# Cubesat-rev1.net
KiCad netlist of a schematic drawn in EAGLE
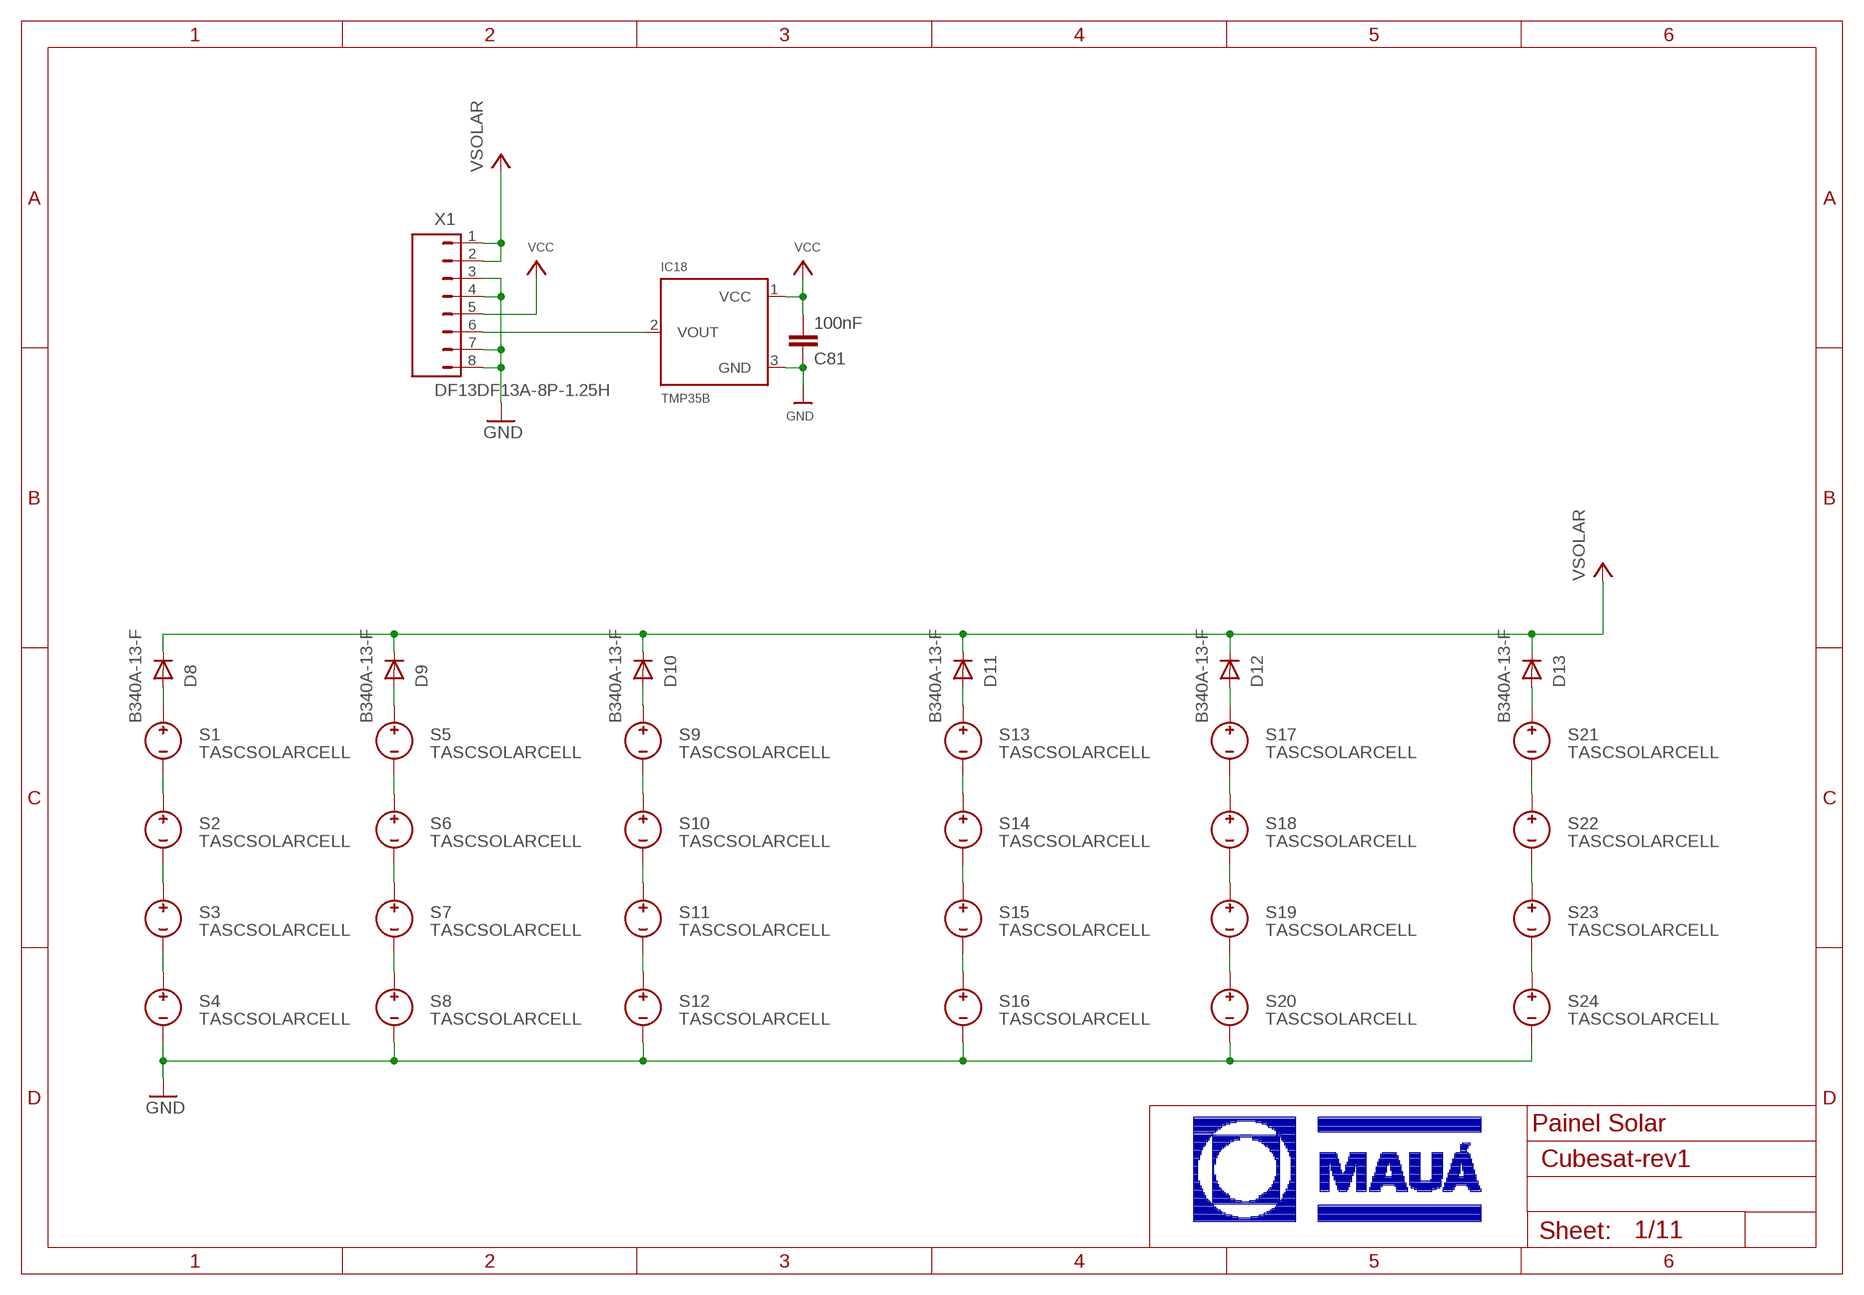
[diagram p0: schematic, sheet 1]
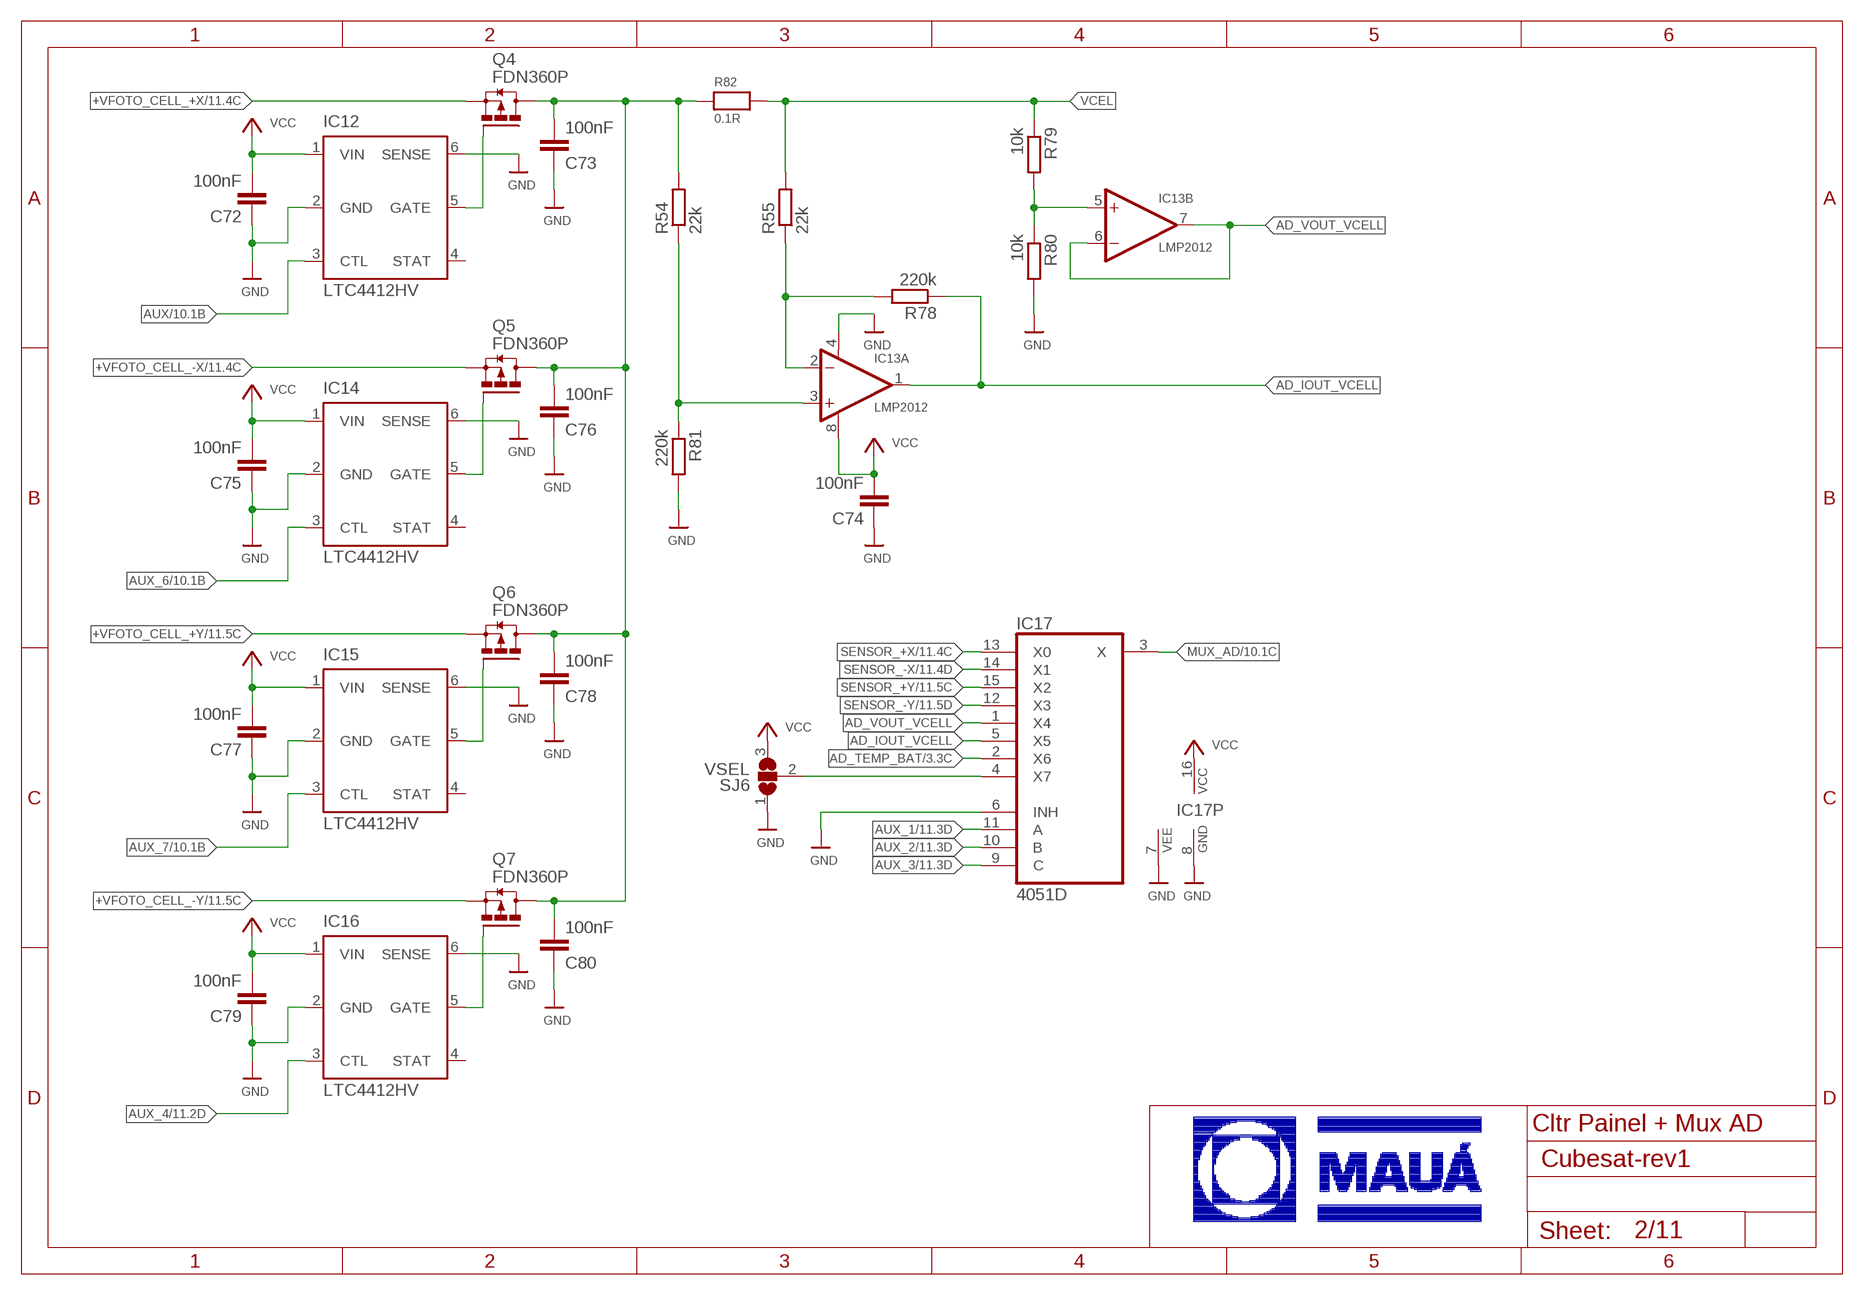
[diagram p1: schematic, sheet 2]
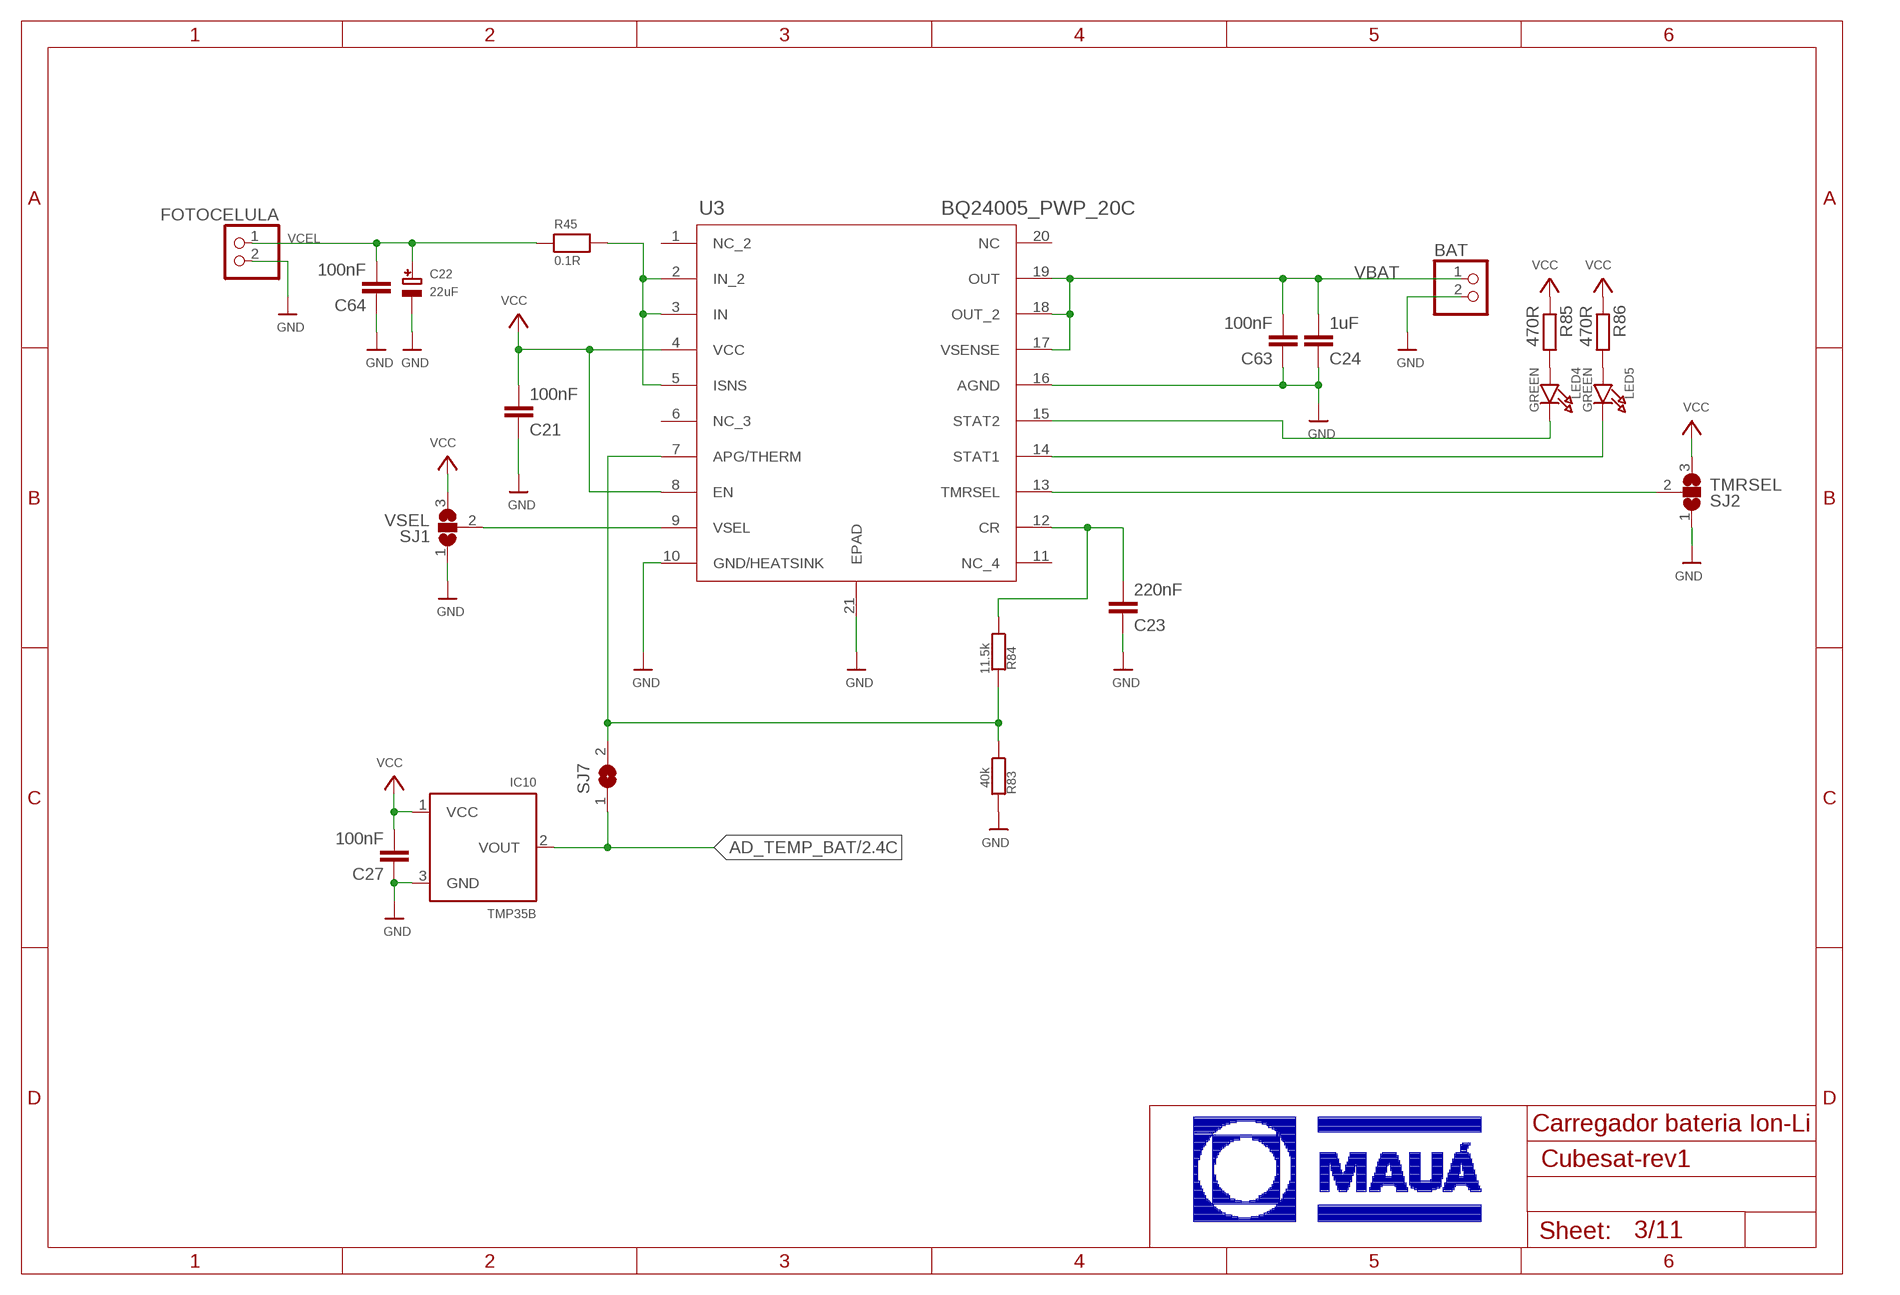
[diagram p2: schematic, sheet 3]
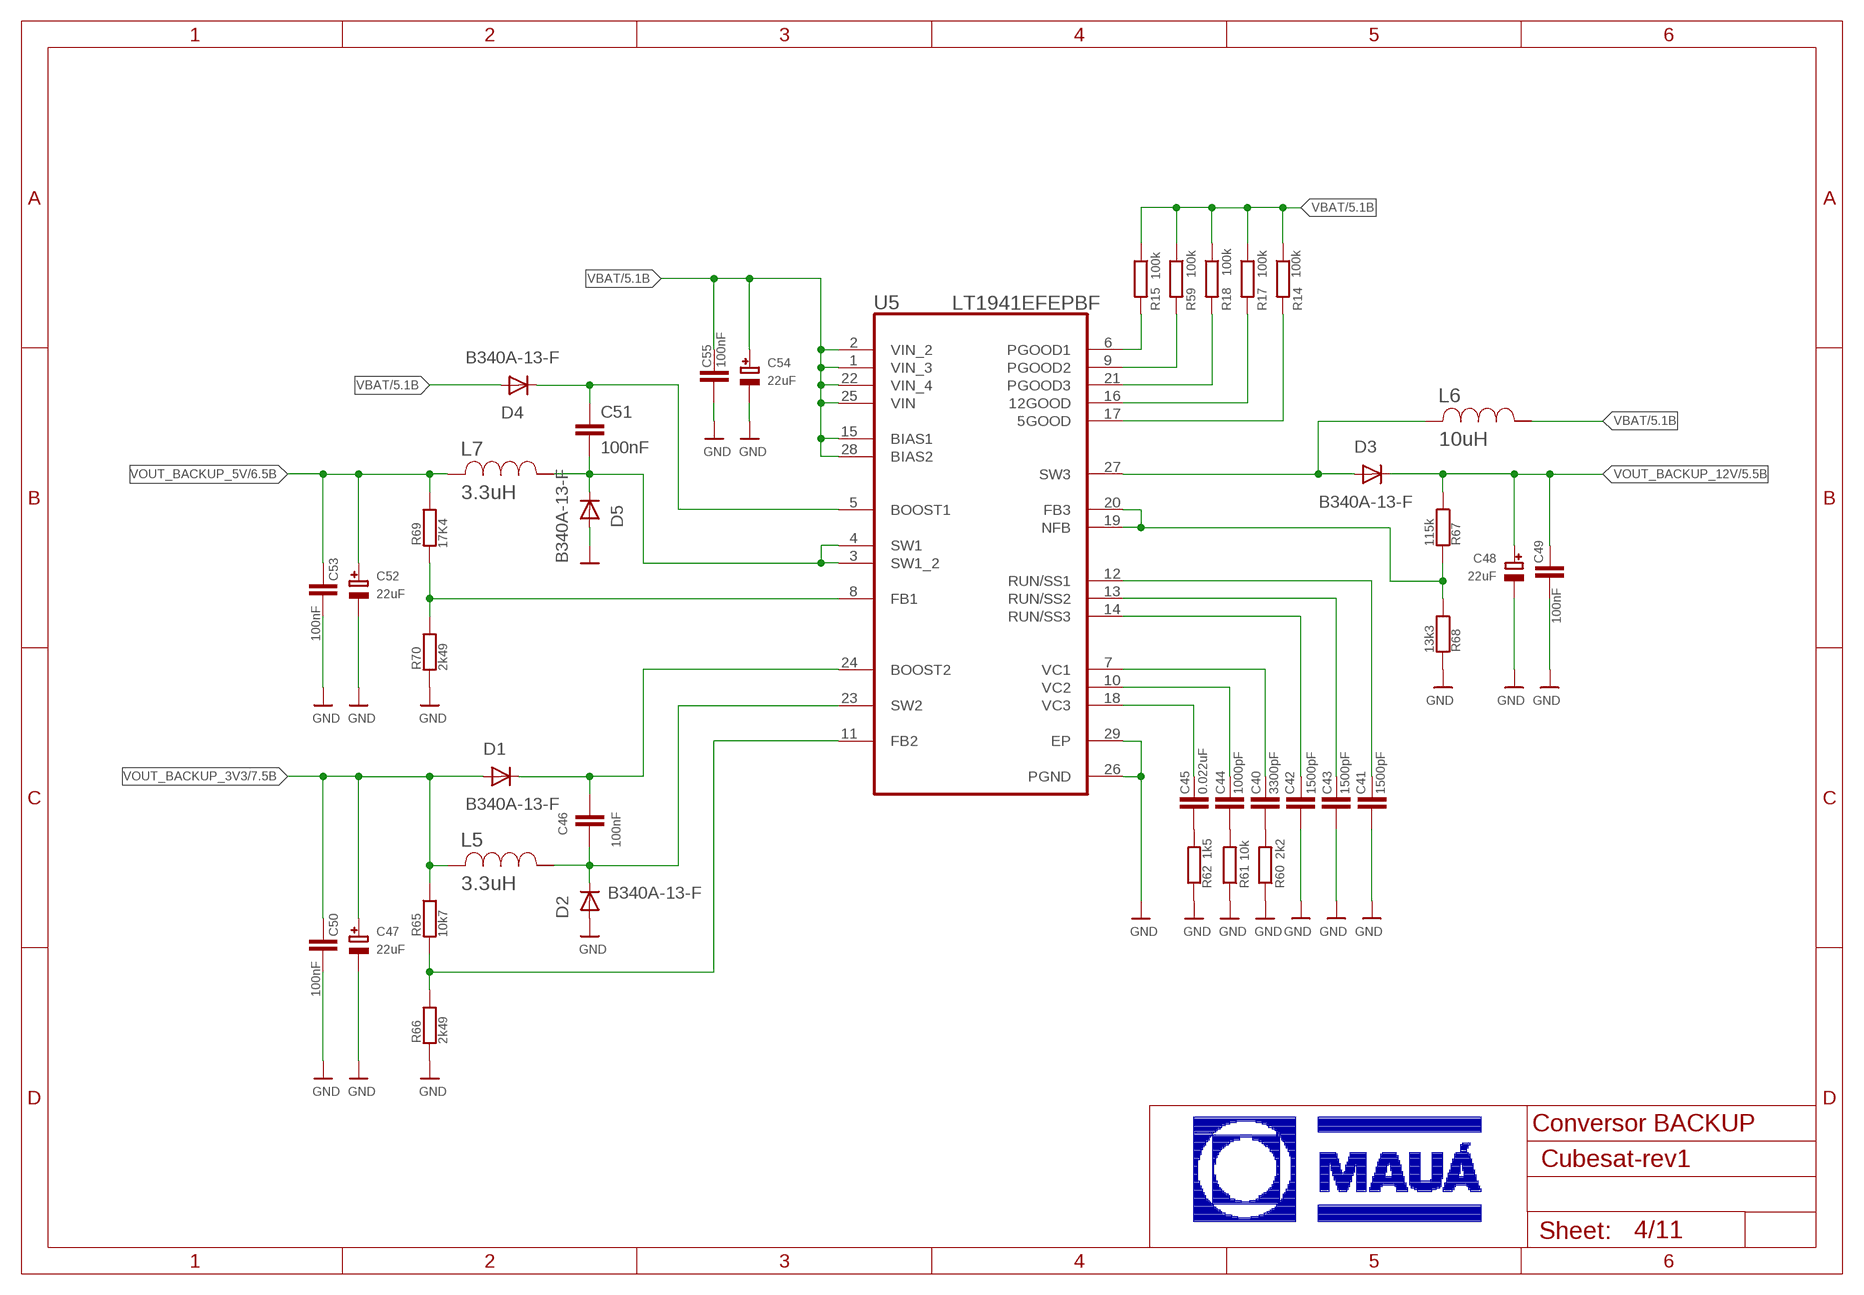
[diagram p3: schematic, sheet 4]
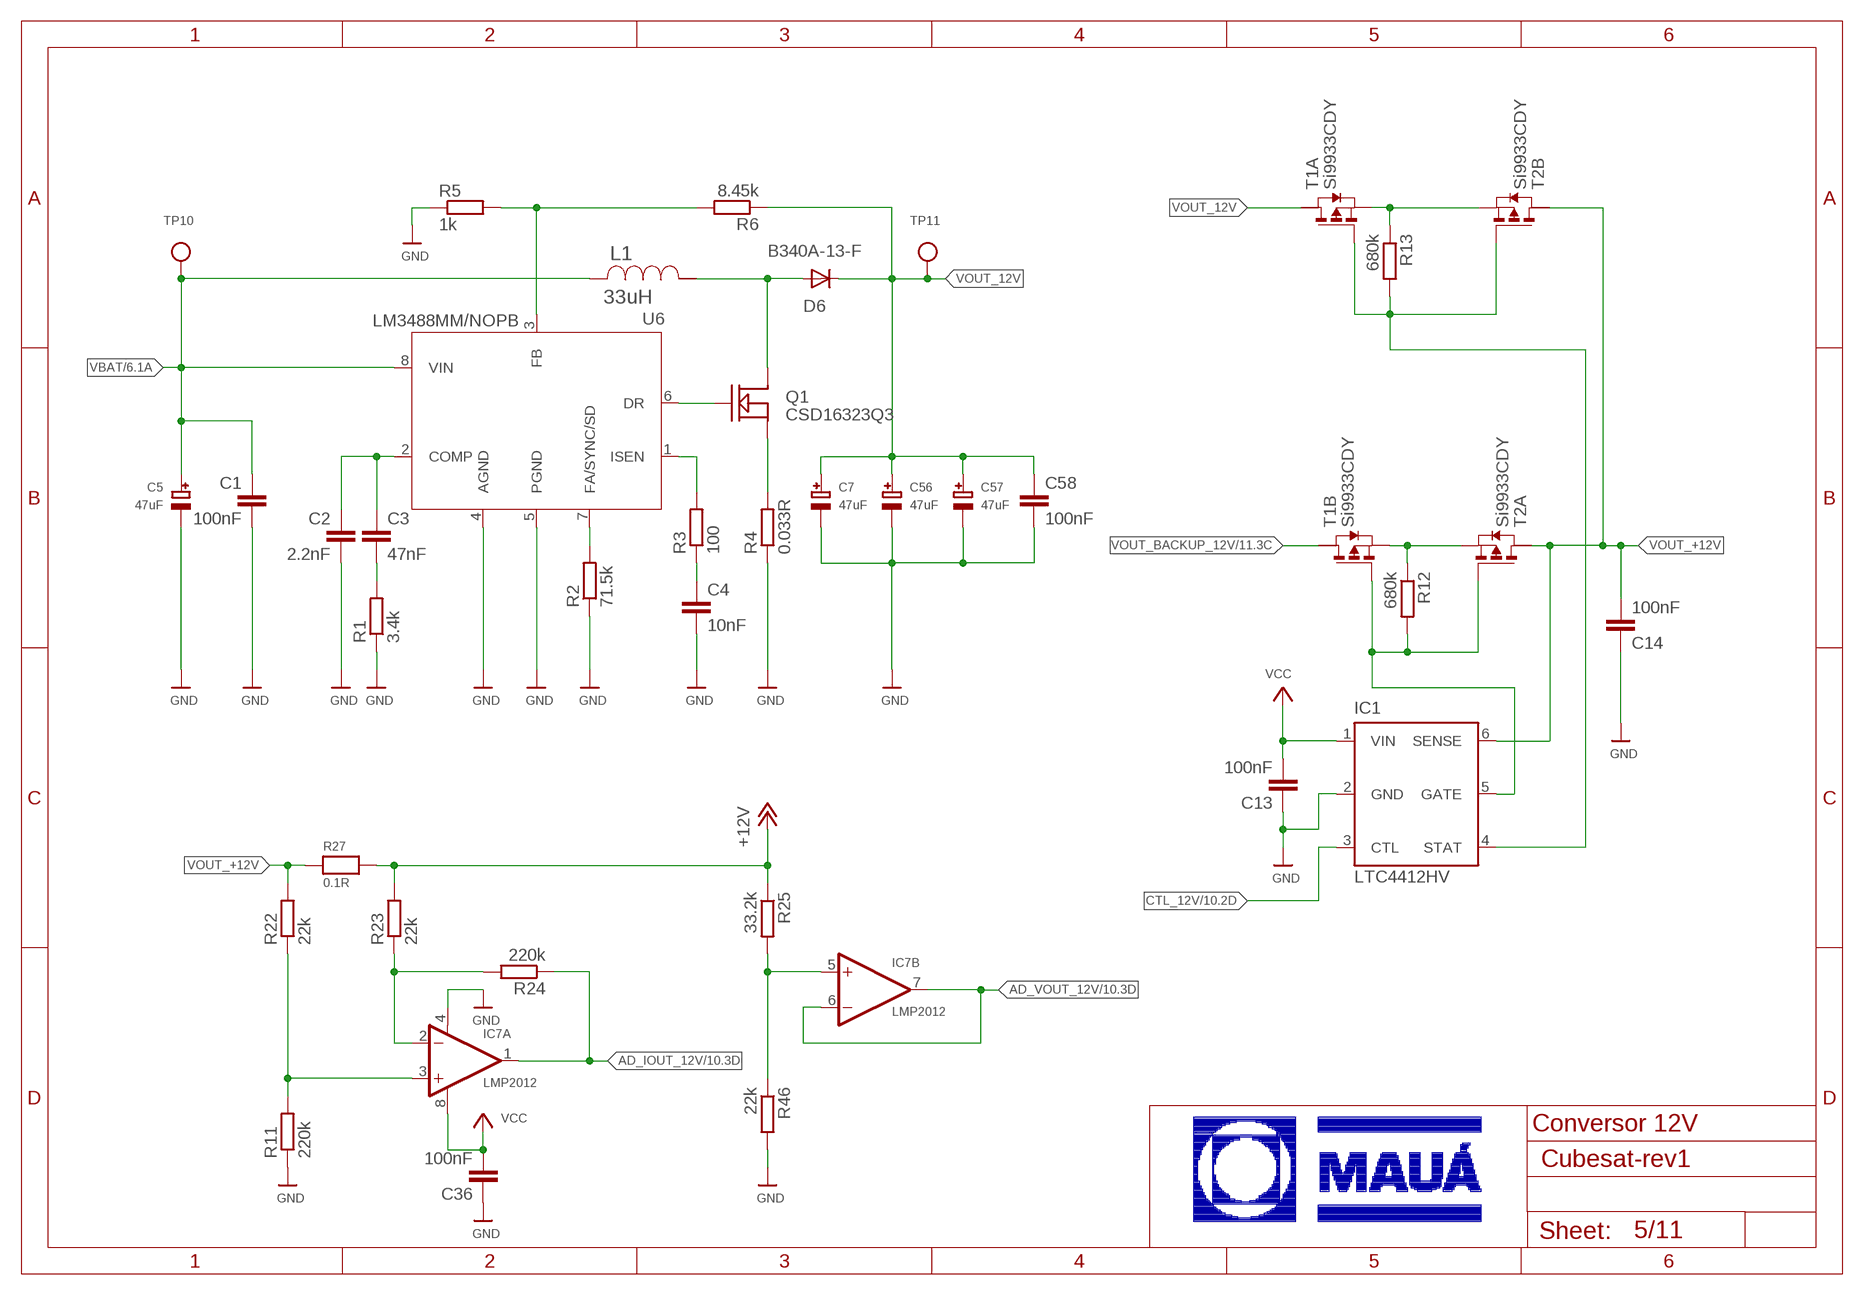
[diagram p4: schematic, sheet 5]
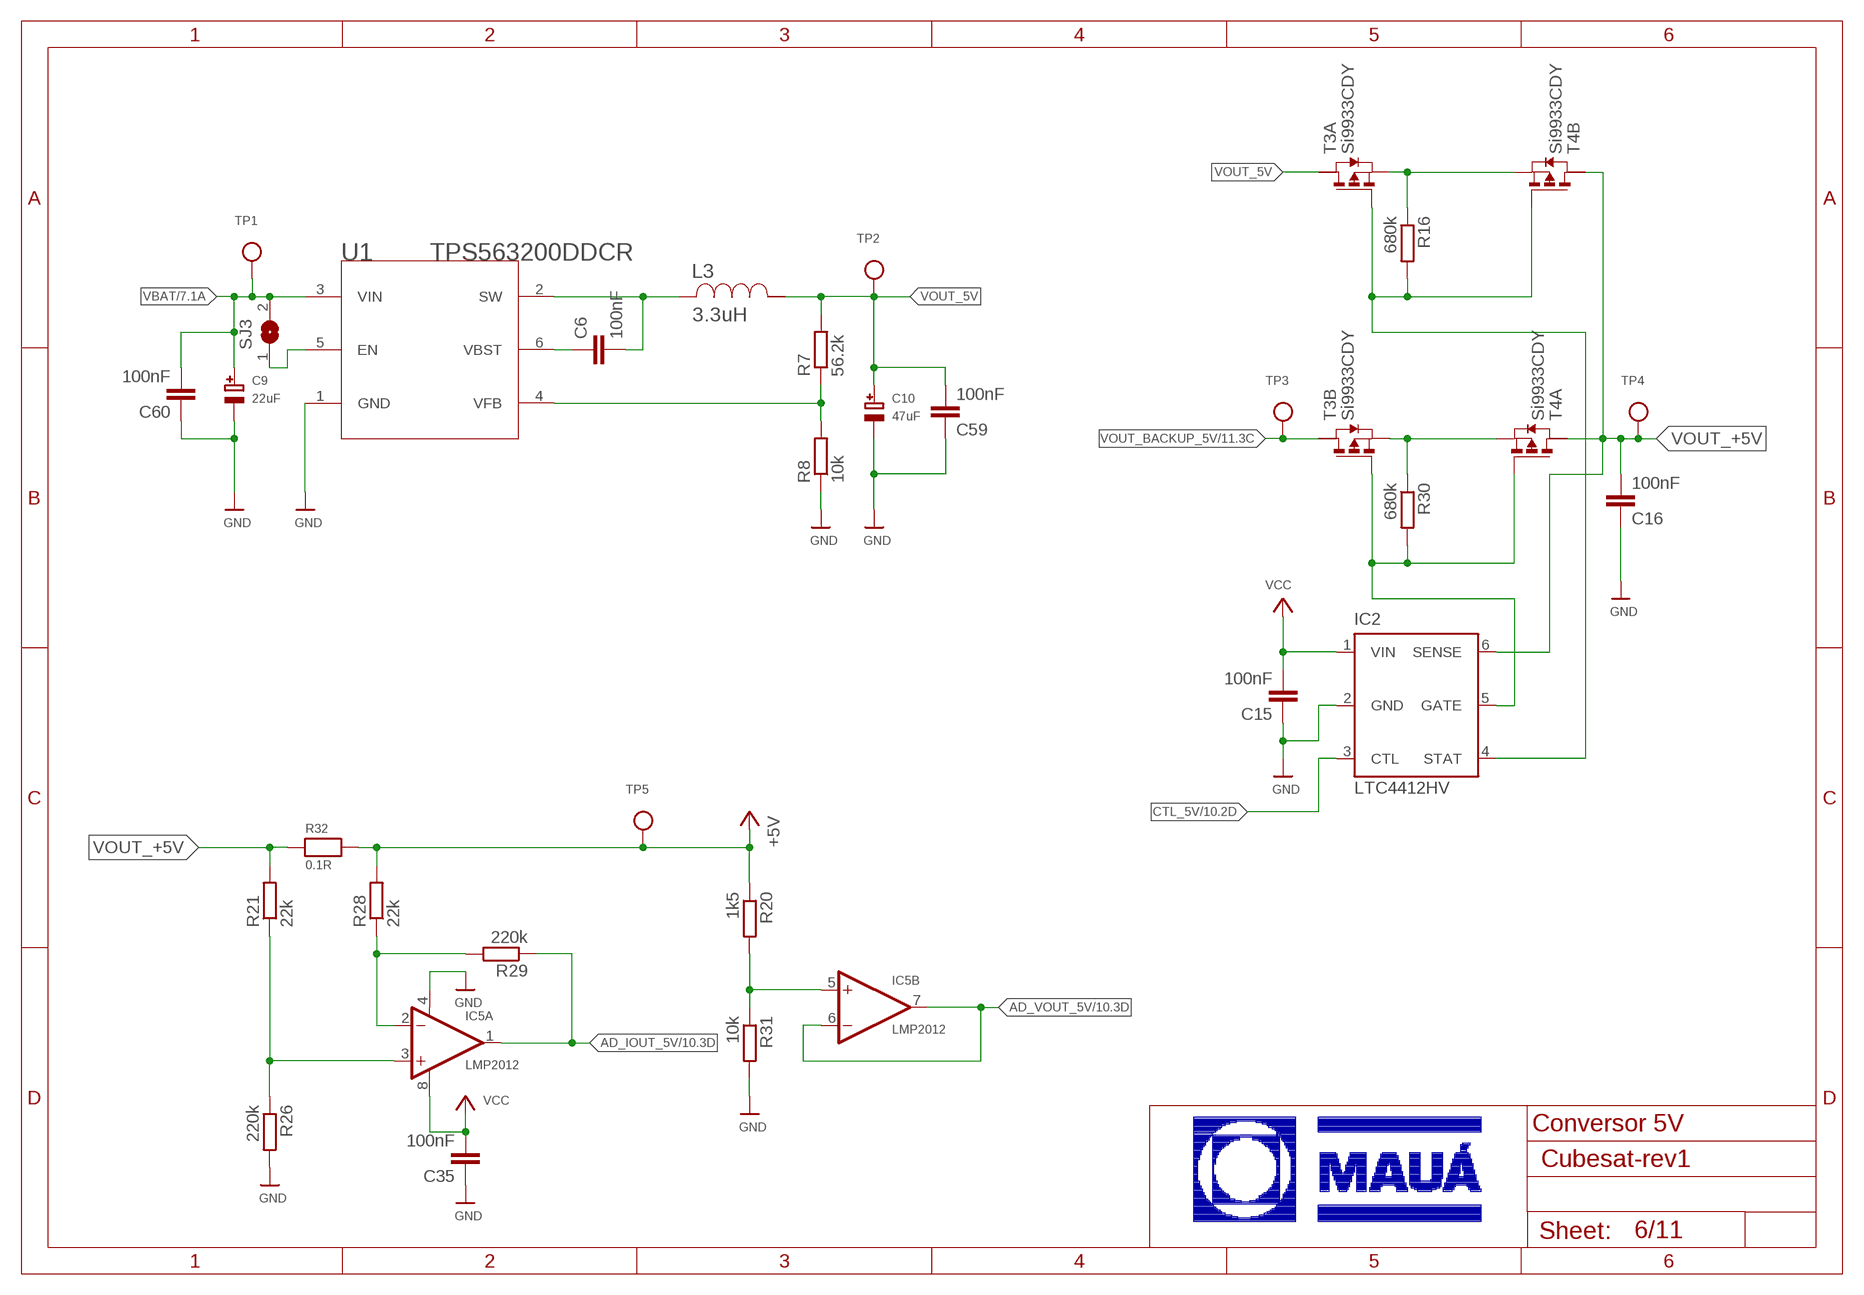
[diagram p5: schematic, sheet 6]
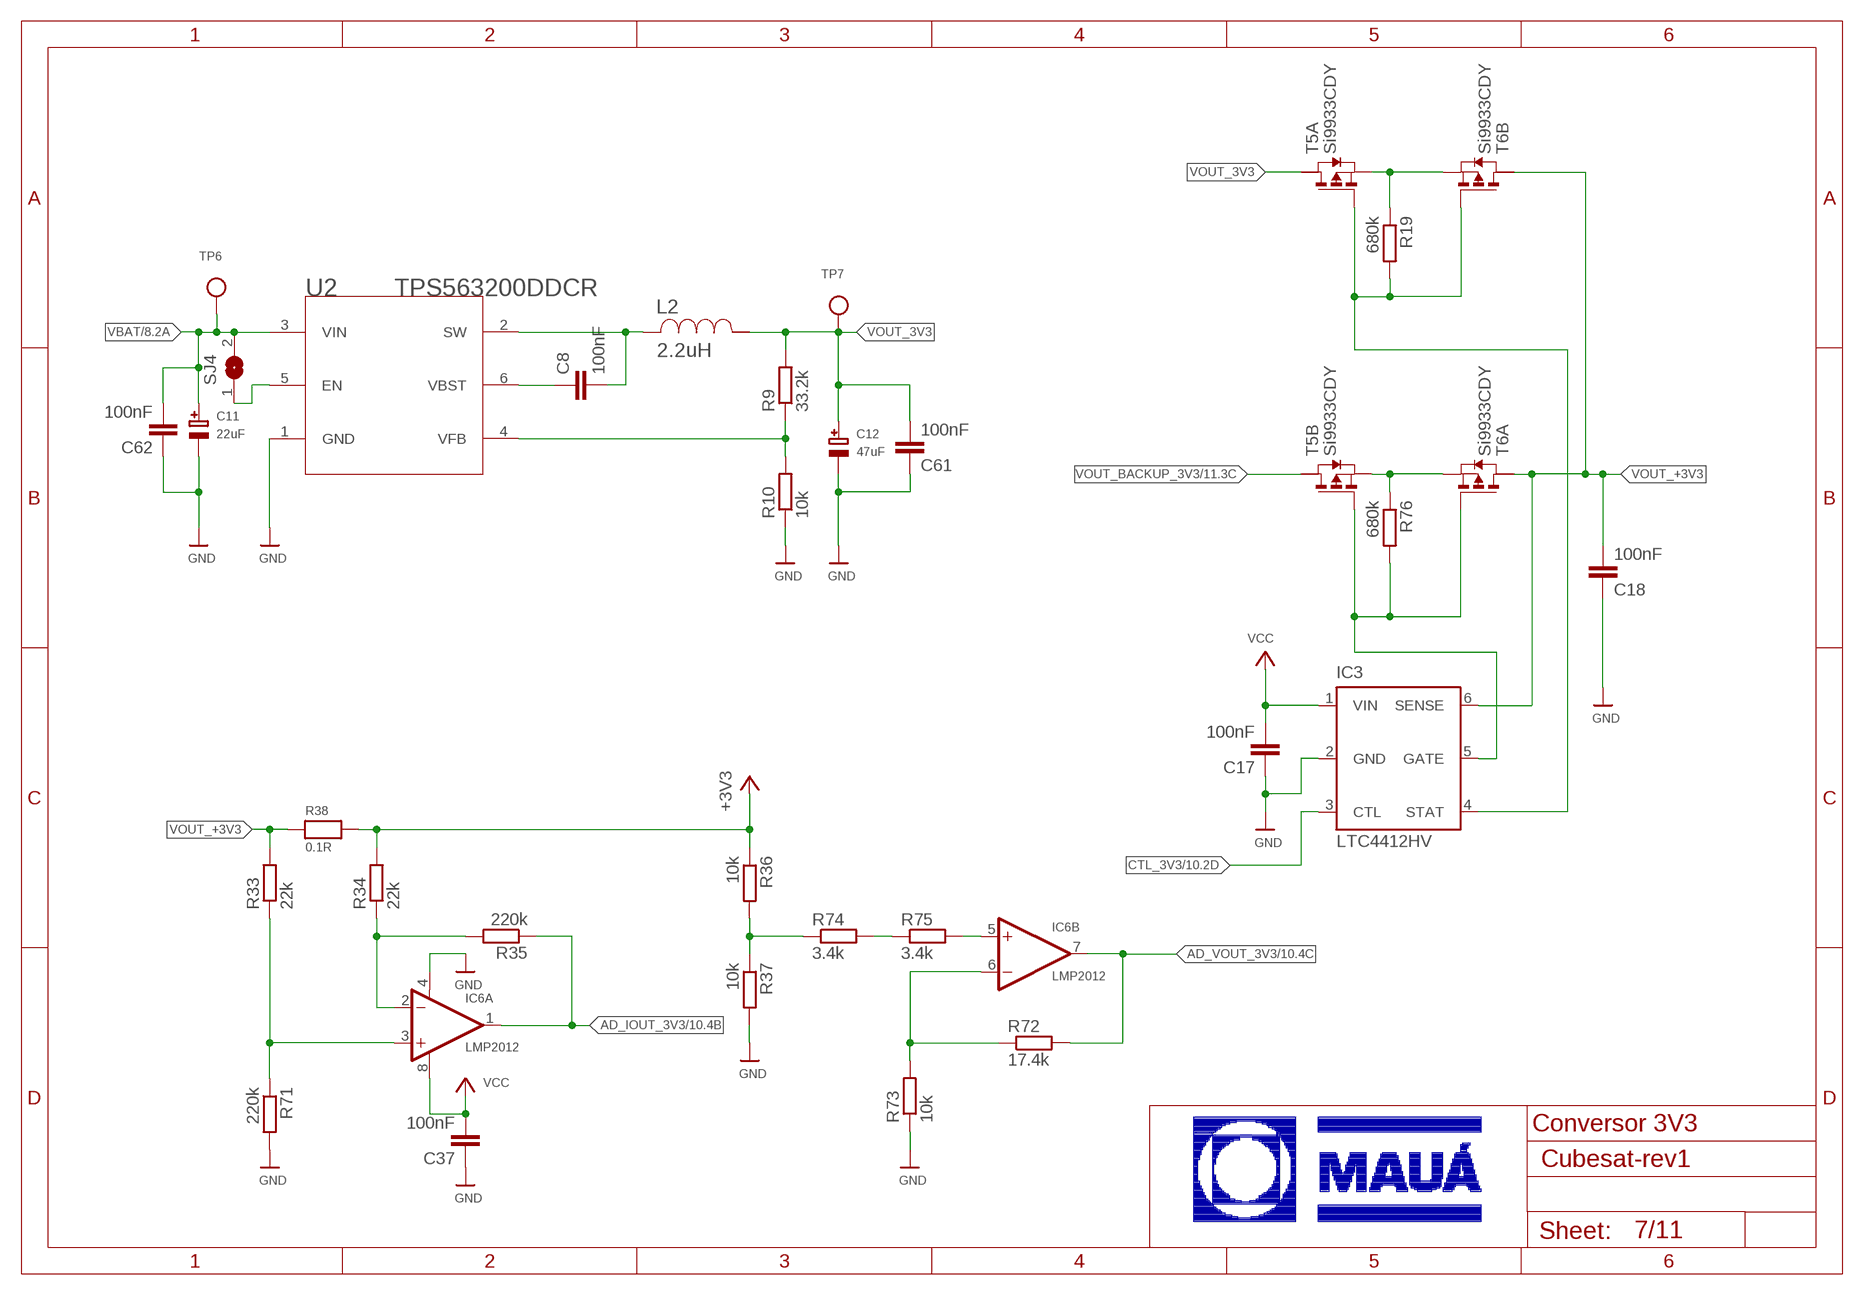
[diagram p6: schematic, sheet 7]
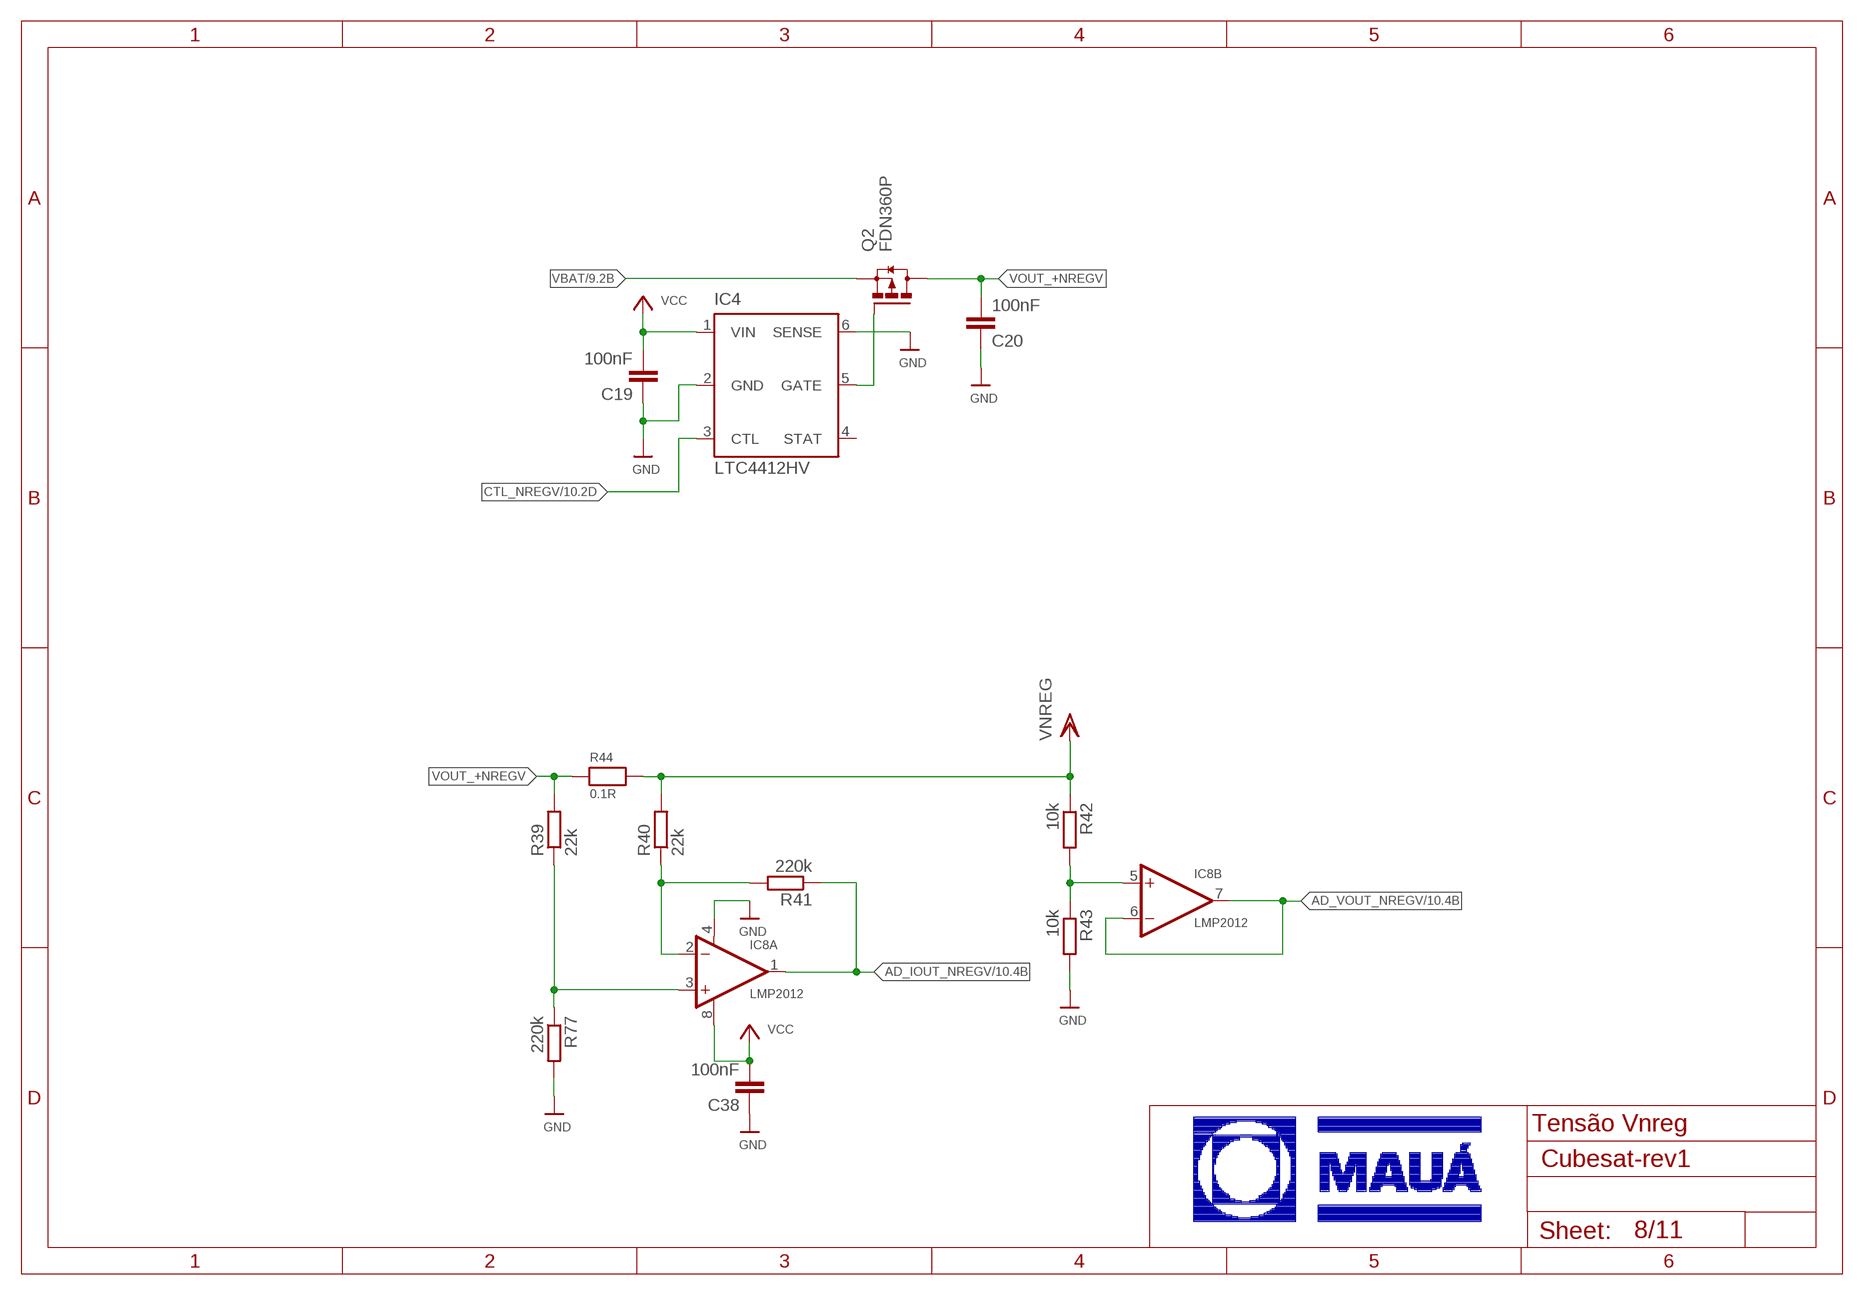
[diagram p7: schematic, sheet 8]
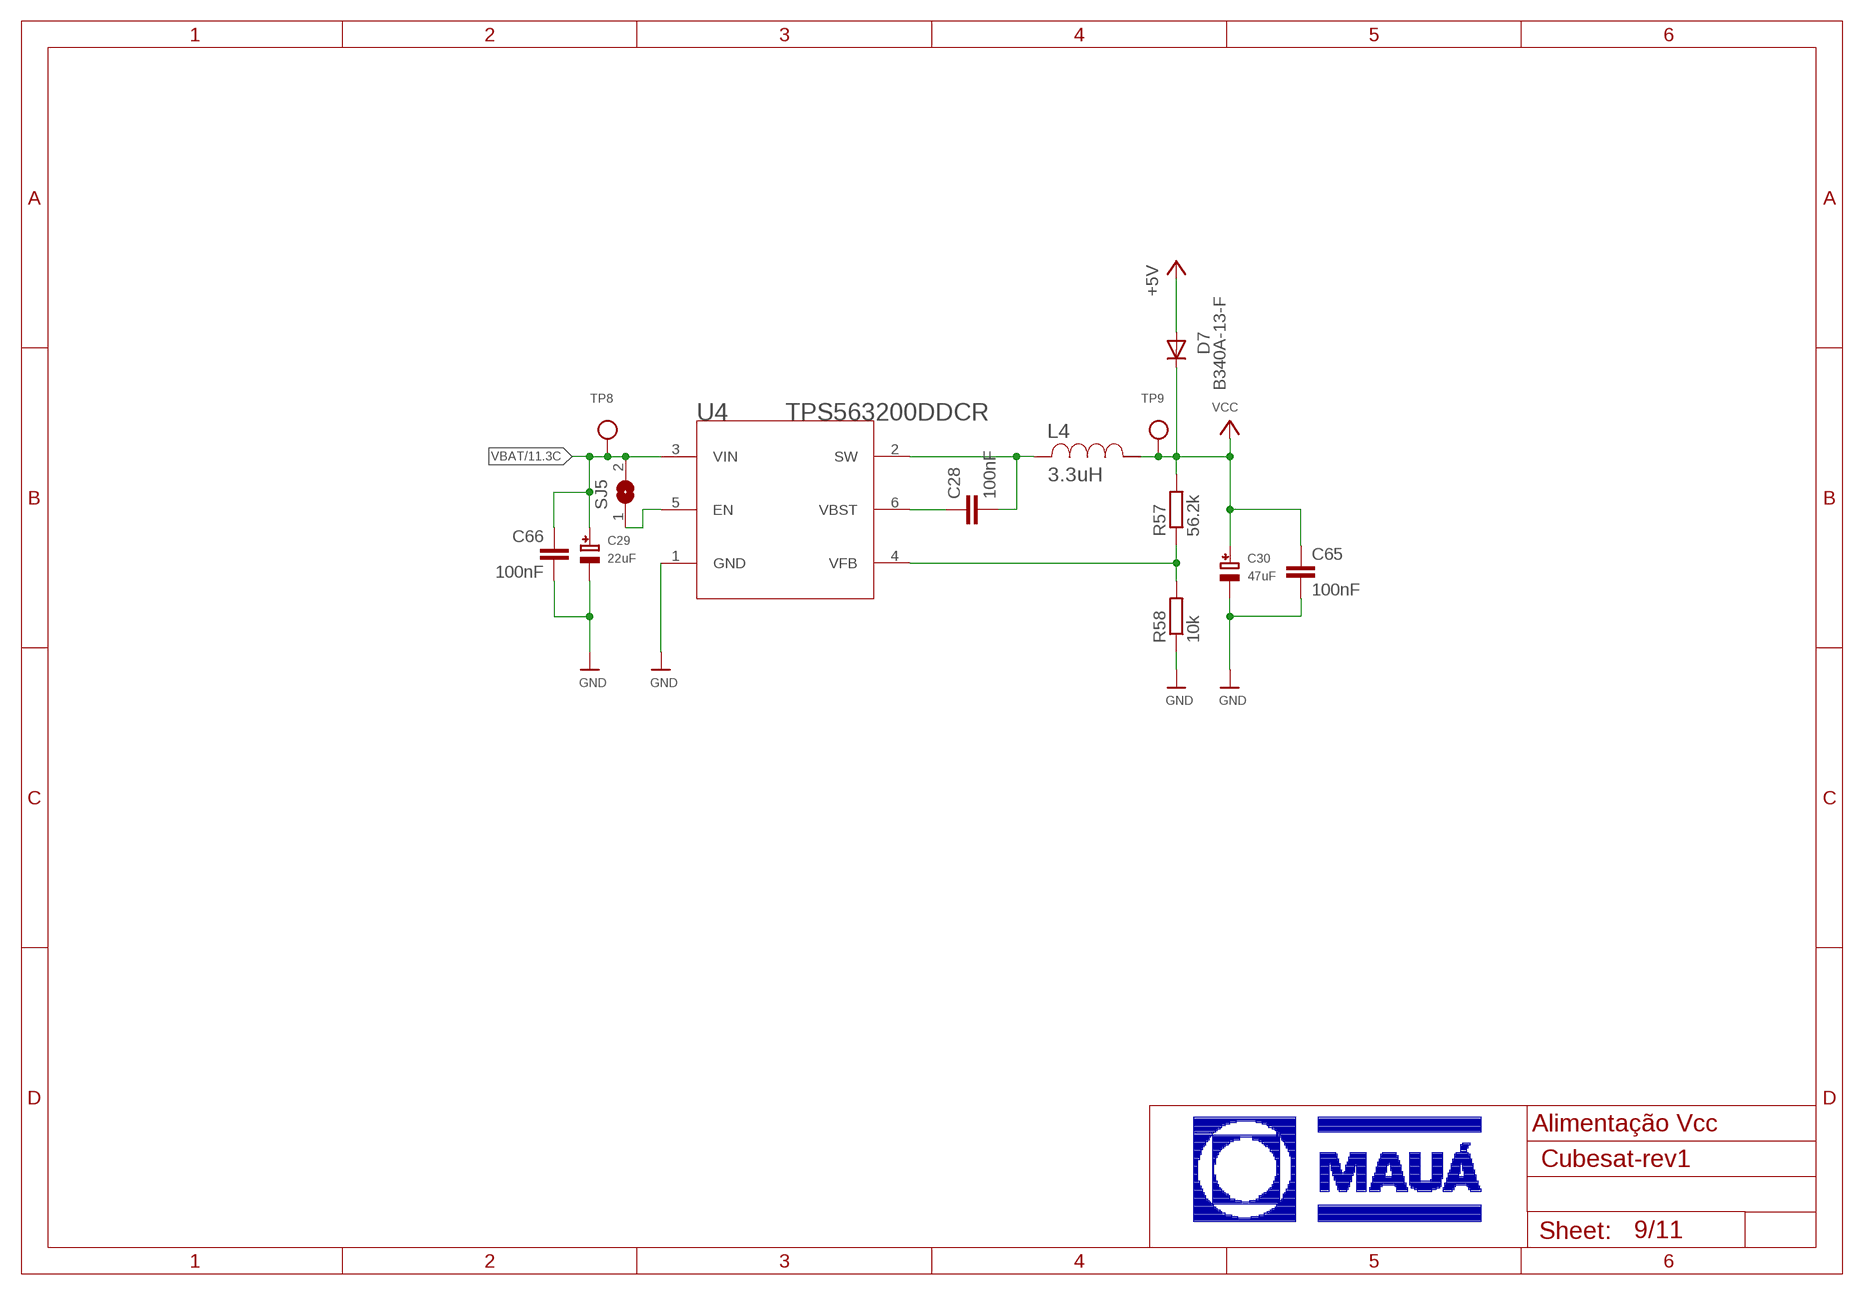
[diagram p8: schematic, sheet 9]
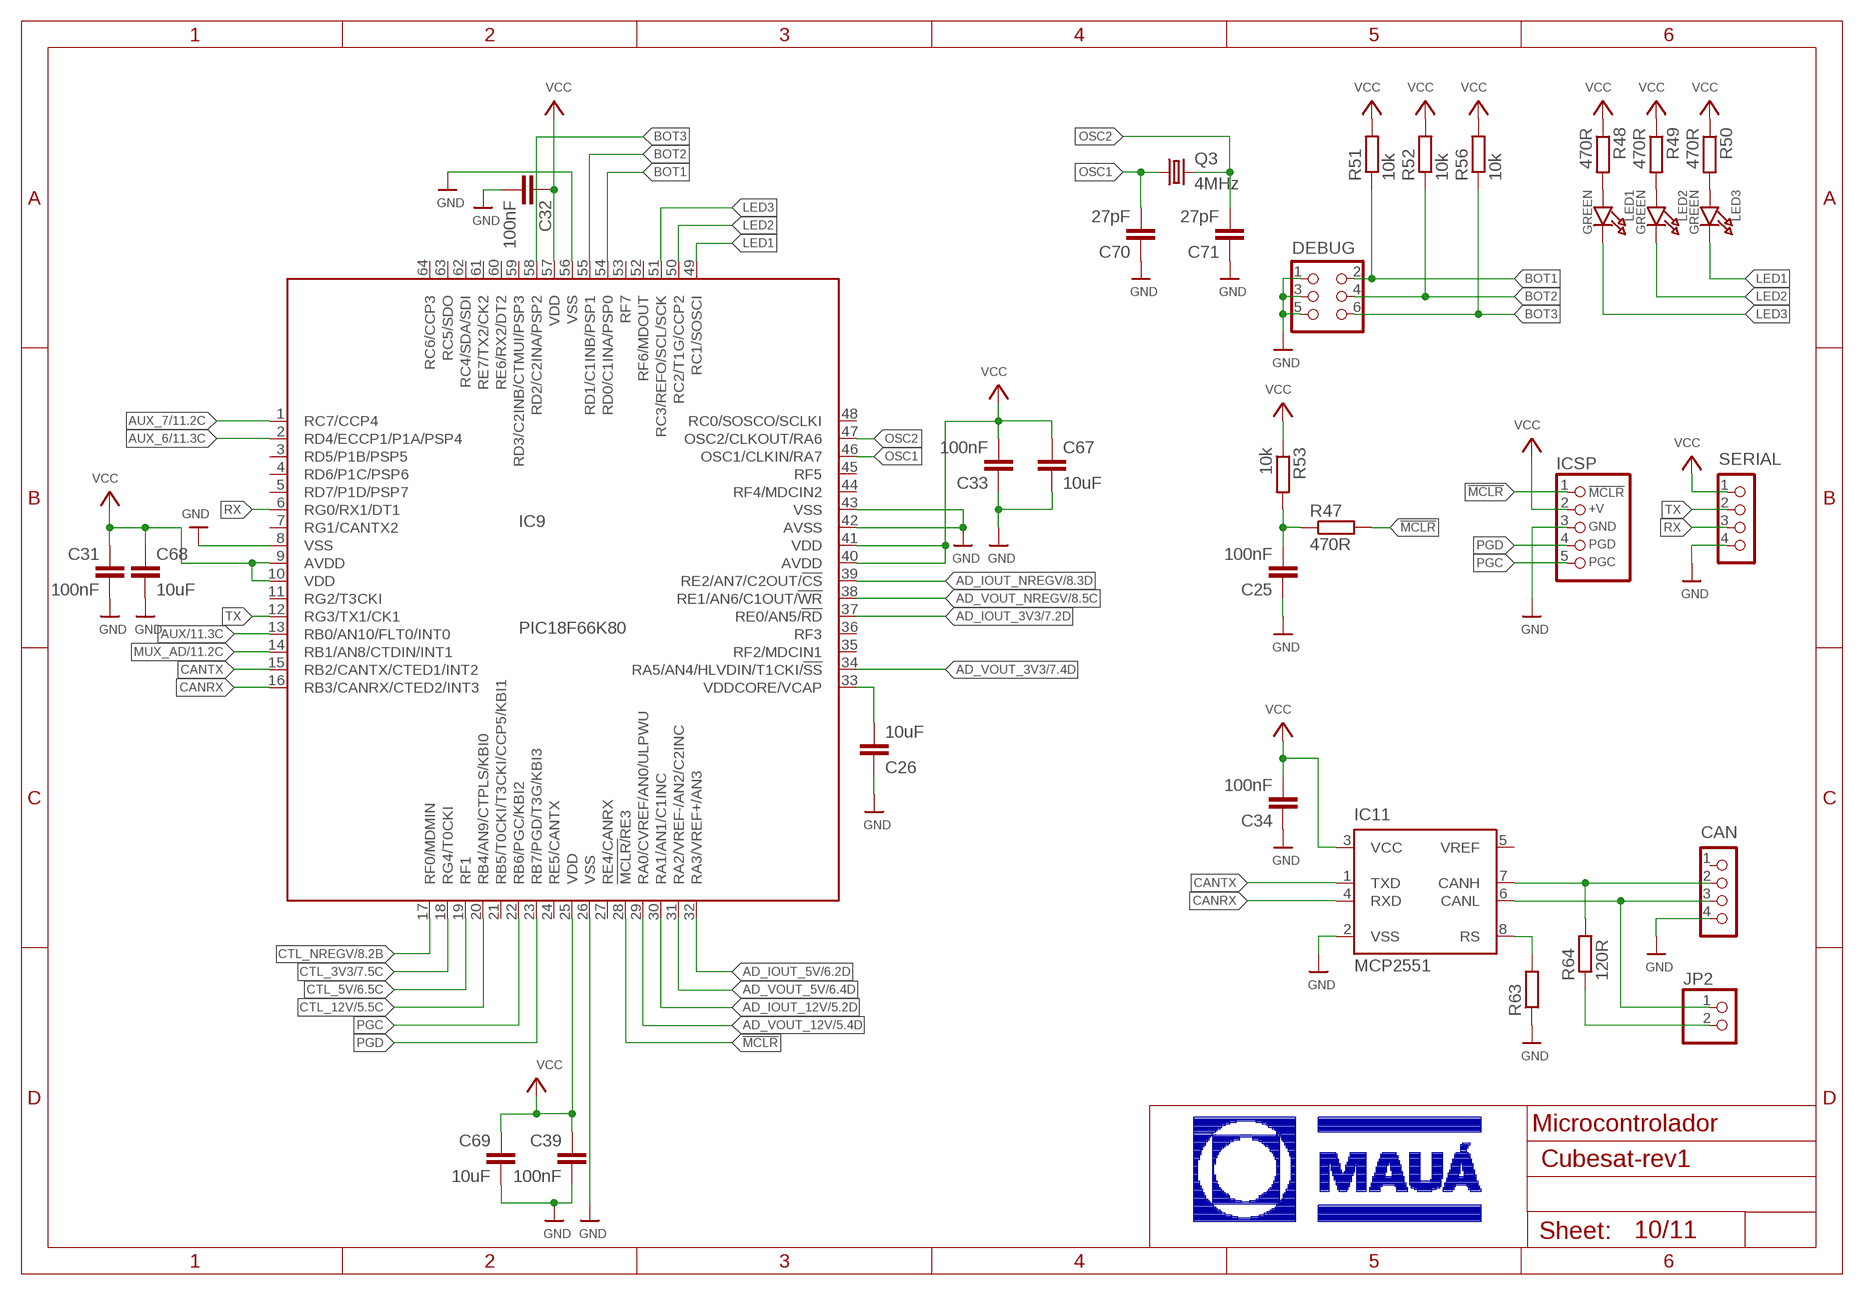
[diagram p9: schematic, sheet 10]
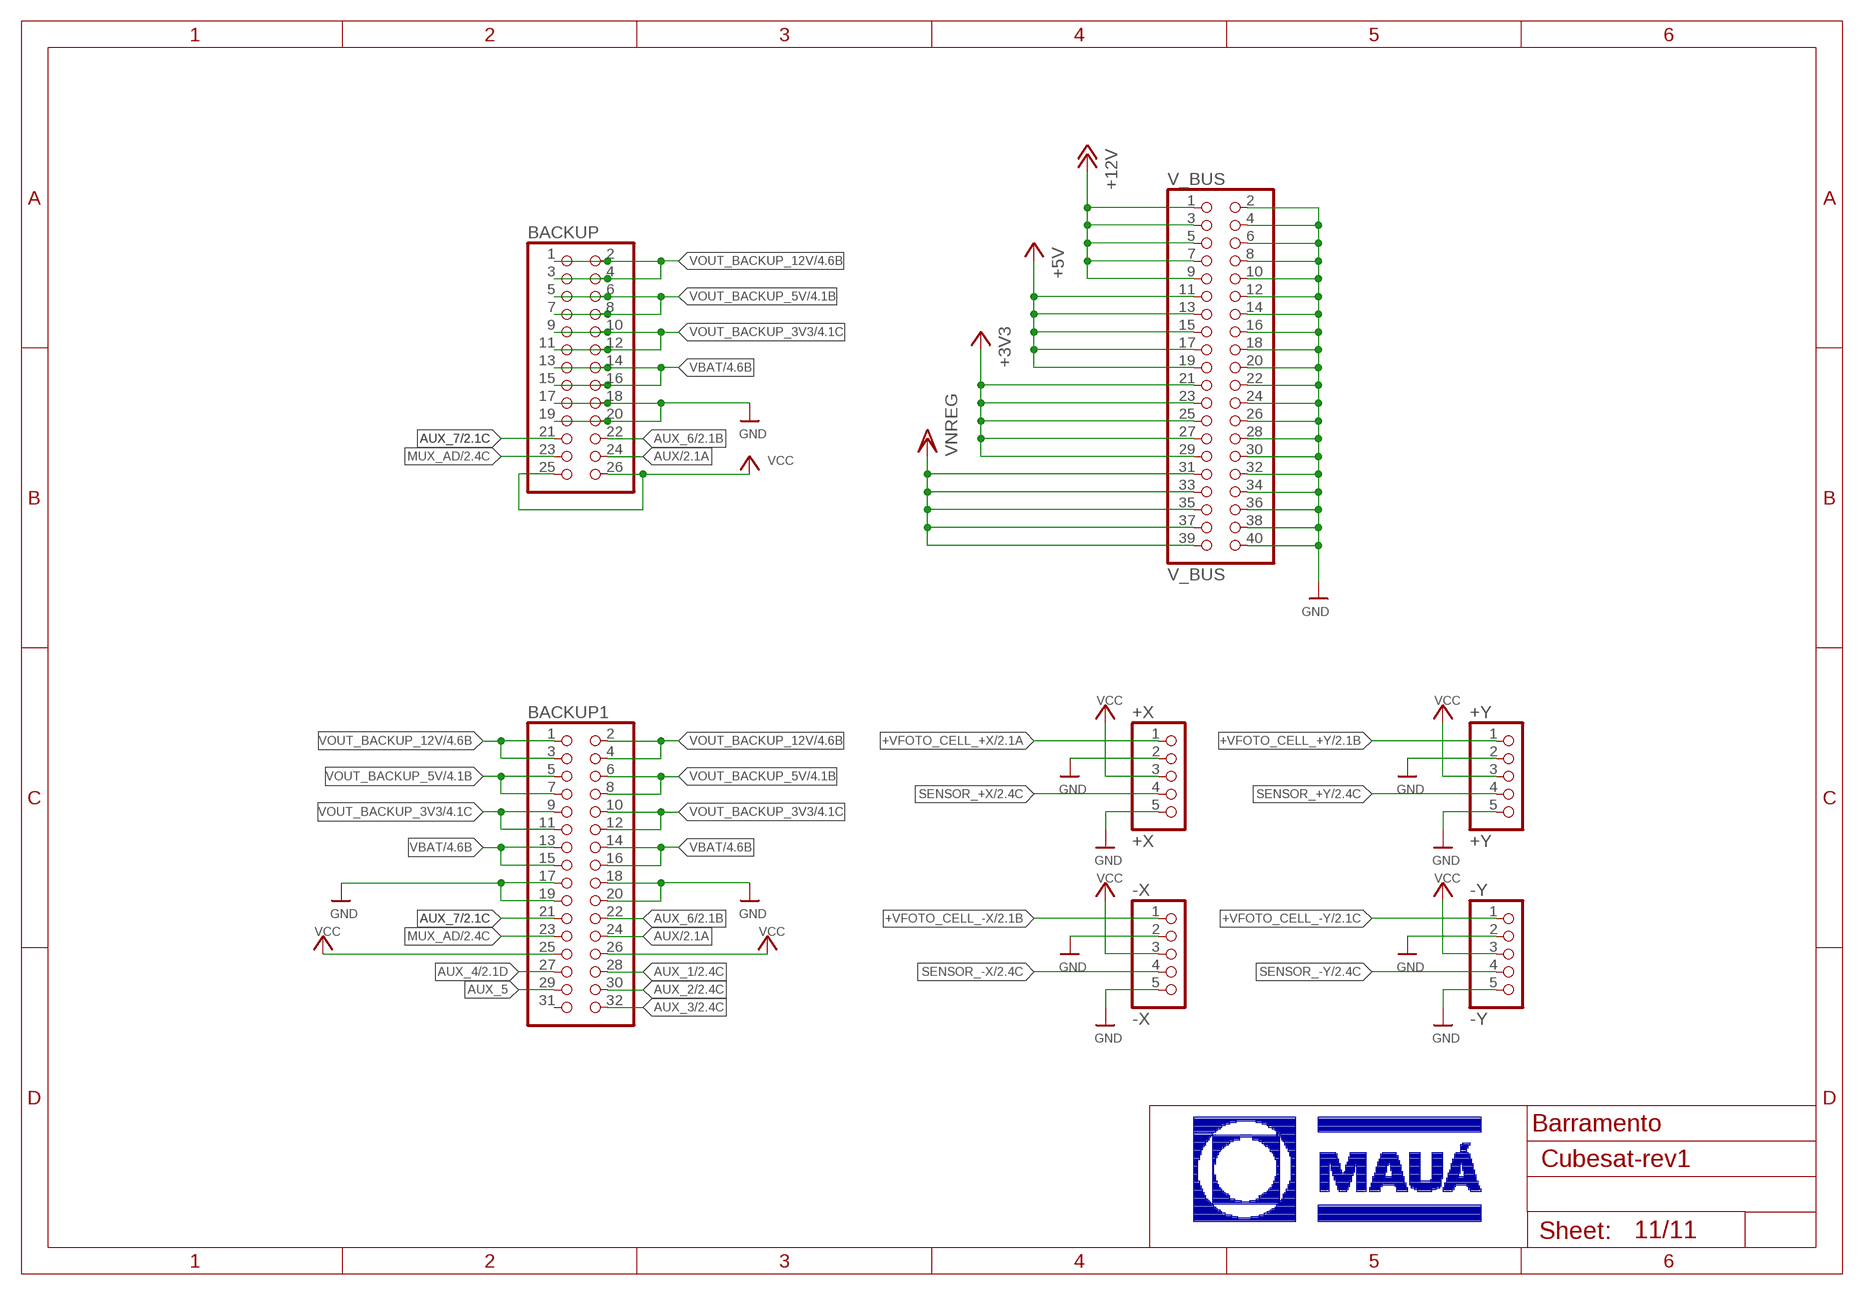
[diagram p10: schematic, sheet 11]

(export (version "E")
  (design (tool "Eeschema 10.0.6"))
  (components
    (comp (ref "C28")
      (value "100nF")
      (footprint "eagle-import:C0805")
      (libsource (lib "eagle-import") (part "C-EUC0805"))
    )
    (comp (ref "C29")
      (value "22uF")
      (footprint "eagle-import:EIA6032-28_C-R")
      (libsource (lib "eagle-import") (part "CAP_TANTALUMC/6032_REFLOW"))
    )
    (comp (ref "C30")
      (value "47uF")
      (footprint "eagle-import:EIA6032-28_C-R")
      (libsource (lib "eagle-import") (part "CAP_TANTALUMC/6032_REFLOW"))
    )
    (comp (ref "C65")
      (value "100nF")
      (footprint "eagle-import:C0805")
      (libsource (lib "eagle-import") (part "C-EUC0805"))
    )
    (comp (ref "C66")
      (value "100nF")
      (footprint "eagle-import:C0805")
      (libsource (lib "eagle-import") (part "C-EUC0805"))
    )
    (comp (ref "D7")
      (value "B340A-13-F")
      (footprint "eagle-import:DO214AC")
      (libsource (lib "eagle-import") (part "DIODE-DO214AC"))
    )
    (comp (ref "L4")
      (value "3.3uH")
      (footprint "eagle-import:SRR6038")
      (fields (field (name "MANUFACTURER_PART_NUMBER") "SRR6038-3R3Y"))
      (libsource (lib "eagle-import") (part "SRR6038-3R3Y"))
    )
    (comp (ref "R57")
      (value "56.2k")
      (footprint "eagle-import:M0805")
      (libsource (lib "eagle-import") (part "R-EU_M0805"))
    )
    (comp (ref "R58")
      (value "10k")
      (footprint "eagle-import:M0805")
      (libsource (lib "eagle-import") (part "R-EU_M0805"))
    )
    (comp (ref "SJ5")
      (value "SOLDERJUMPER")
      (footprint "eagle-import:SOLDERJUMPER_ARROW_NOPASTE")
      (libsource (lib "eagle-import") (part "SOLDERJUMPER"))
    )
    (comp (ref "TP8")
      (value "TESTPOINT0.1\"")
      (footprint "eagle-import:1X01_ROUND")
      (libsource (lib "eagle-import") (part "TESTPOINT0.1{dblquote}"))
    )
    (comp (ref "TP9")
      (value "TESTPOINT0.1\"")
      (footprint "eagle-import:1X01_ROUND")
      (fields (field (name "BOM") "EXCLUDE"))
      (libsource (lib "eagle-import") (part "TESTPOINT0.1{dblquote}"))
    )
    (comp (ref "U4")
      (value "TPS563200DDCR")
      (footprint "eagle-import:DDC0006A")
      (fields
        (field (name "MANUFACTURER") "Texas Instruments")
        (field (name "PARTNUMBER") "TPS563200DDC")
        (field (name "APPROVEDBY") "Not shown in title block")
        (field (name "AUTHOR") "Not shown in title block")
        (field (name "CHECKEDBY") "Not shown in title block")
        (field (name "ENGINEER") "Not shown in title block")
        (field (name "MODIFIEDDATE") "Not shown in title block")
        (field (name "PUBLISHER") "Texas Instruments")
        (field (name "SYMBOLCREATOR") "a0411947")
      )
      (libsource (lib "eagle-import") (part "TPS563200DDCR"))
    )
    (comp (ref "C81")
      (value "100nF")
      (footprint "eagle-import:C0805")
      (libsource (lib "eagle-import") (part "C-EUC0805"))
    )
    (comp (ref "D8")
      (value "B340A-13-F")
      (footprint "eagle-import:DO214AC")
      (libsource (lib "eagle-import") (part "DIODE-DO214AC"))
    )
    (comp (ref "D9")
      (value "B340A-13-F")
      (footprint "eagle-import:DO214AC")
      (libsource (lib "eagle-import") (part "DIODE-DO214AC"))
    )
    (comp (ref "D10")
      (value "B340A-13-F")
      (footprint "eagle-import:DO214AC")
      (libsource (lib "eagle-import") (part "DIODE-DO214AC"))
    )
    (comp (ref "D11")
      (value "B340A-13-F")
      (footprint "eagle-import:DO214AC")
      (libsource (lib "eagle-import") (part "DIODE-DO214AC"))
    )
    (comp (ref "D12")
      (value "B340A-13-F")
      (footprint "eagle-import:DO214AC")
      (libsource (lib "eagle-import") (part "DIODE-DO214AC"))
    )
    (comp (ref "D13")
      (value "B340A-13-F")
      (footprint "eagle-import:DO214AC")
      (libsource (lib "eagle-import") (part "DIODE-DO214AC"))
    )
    (comp (ref "IC18")
      (value "TMP35B")
      (footprint "eagle-import:TO92-LINE")
      (libsource (lib "eagle-import") (part "TMP35B"))
    )
    (comp (ref "S1")
      (value "TASCSOLARCELL")
      (footprint "eagle-import:TASCSOLARCELL")
      (libsource (lib "eagle-import") (part "TASCSOLARCELL"))
    )
    (comp (ref "S2")
      (value "TASCSOLARCELL")
      (footprint "eagle-import:TASCSOLARCELL")
      (libsource (lib "eagle-import") (part "TASCSOLARCELL"))
    )
    (comp (ref "S3")
      (value "TASCSOLARCELL")
      (footprint "eagle-import:TASCSOLARCELL")
      (libsource (lib "eagle-import") (part "TASCSOLARCELL"))
    )
    (comp (ref "S4")
      (value "TASCSOLARCELL")
      (footprint "eagle-import:TASCSOLARCELL")
      (libsource (lib "eagle-import") (part "TASCSOLARCELL"))
    )
    (comp (ref "S5")
      (value "TASCSOLARCELL")
      (footprint "eagle-import:TASCSOLARCELL")
      (libsource (lib "eagle-import") (part "TASCSOLARCELL"))
    )
    (comp (ref "S6")
      (value "TASCSOLARCELL")
      (footprint "eagle-import:TASCSOLARCELL")
      (libsource (lib "eagle-import") (part "TASCSOLARCELL"))
    )
    (comp (ref "S7")
      (value "TASCSOLARCELL")
      (footprint "eagle-import:TASCSOLARCELL")
      (libsource (lib "eagle-import") (part "TASCSOLARCELL"))
    )
    (comp (ref "S8")
      (value "TASCSOLARCELL")
      (footprint "eagle-import:TASCSOLARCELL")
      (libsource (lib "eagle-import") (part "TASCSOLARCELL"))
    )
    (comp (ref "S9")
      (value "TASCSOLARCELL")
      (footprint "eagle-import:TASCSOLARCELL")
      (libsource (lib "eagle-import") (part "TASCSOLARCELL"))
    )
    (comp (ref "S10")
      (value "TASCSOLARCELL")
      (footprint "eagle-import:TASCSOLARCELL")
      (libsource (lib "eagle-import") (part "TASCSOLARCELL"))
    )
    (comp (ref "S11")
      (value "TASCSOLARCELL")
      (footprint "eagle-import:TASCSOLARCELL")
      (libsource (lib "eagle-import") (part "TASCSOLARCELL"))
    )
    (comp (ref "S12")
      (value "TASCSOLARCELL")
      (footprint "eagle-import:TASCSOLARCELL")
      (libsource (lib "eagle-import") (part "TASCSOLARCELL"))
    )
    (comp (ref "S13")
      (value "TASCSOLARCELL")
      (footprint "eagle-import:TASCSOLARCELL")
      (libsource (lib "eagle-import") (part "TASCSOLARCELL"))
    )
    (comp (ref "S14")
      (value "TASCSOLARCELL")
      (footprint "eagle-import:TASCSOLARCELL")
      (libsource (lib "eagle-import") (part "TASCSOLARCELL"))
    )
    (comp (ref "S15")
      (value "TASCSOLARCELL")
      (footprint "eagle-import:TASCSOLARCELL")
      (libsource (lib "eagle-import") (part "TASCSOLARCELL"))
    )
    (comp (ref "S16")
      (value "TASCSOLARCELL")
      (footprint "eagle-import:TASCSOLARCELL")
      (libsource (lib "eagle-import") (part "TASCSOLARCELL"))
    )
    (comp (ref "S17")
      (value "TASCSOLARCELL")
      (footprint "eagle-import:TASCSOLARCELL")
      (libsource (lib "eagle-import") (part "TASCSOLARCELL"))
    )
    (comp (ref "S18")
      (value "TASCSOLARCELL")
      (footprint "eagle-import:TASCSOLARCELL")
      (libsource (lib "eagle-import") (part "TASCSOLARCELL"))
    )
    (comp (ref "S19")
      (value "TASCSOLARCELL")
      (footprint "eagle-import:TASCSOLARCELL")
      (libsource (lib "eagle-import") (part "TASCSOLARCELL"))
    )
    (comp (ref "S20")
      (value "TASCSOLARCELL")
      (footprint "eagle-import:TASCSOLARCELL")
      (libsource (lib "eagle-import") (part "TASCSOLARCELL"))
    )
    (comp (ref "S21")
      (value "TASCSOLARCELL")
      (footprint "eagle-import:TASCSOLARCELL")
      (libsource (lib "eagle-import") (part "TASCSOLARCELL"))
    )
    (comp (ref "S22")
      (value "TASCSOLARCELL")
      (footprint "eagle-import:TASCSOLARCELL")
      (libsource (lib "eagle-import") (part "TASCSOLARCELL"))
    )
    (comp (ref "S23")
      (value "TASCSOLARCELL")
      (footprint "eagle-import:TASCSOLARCELL")
      (libsource (lib "eagle-import") (part "TASCSOLARCELL"))
    )
    (comp (ref "S24")
      (value "TASCSOLARCELL")
      (footprint "eagle-import:TASCSOLARCELL")
      (libsource (lib "eagle-import") (part "TASCSOLARCELL"))
    )
    (comp (ref "X1")
      (value "DF13DF13A-8P-1.25H")
      (footprint "eagle-import:DF13A-8P")
      (libsource (lib "eagle-import") (part "DF13DF13A-8P-1.25H"))
    )
    (comp (ref "C72")
      (value "100nF")
      (footprint "eagle-import:C0805")
      (libsource (lib "eagle-import") (part "C-EUC0805"))
    )
    (comp (ref "C73")
      (value "100nF")
      (footprint "eagle-import:C0805")
      (libsource (lib "eagle-import") (part "C-EUC0805"))
    )
    (comp (ref "C74")
      (value "100nF")
      (footprint "eagle-import:C0805")
      (libsource (lib "eagle-import") (part "C-EUC0805"))
    )
    (comp (ref "C75")
      (value "100nF")
      (footprint "eagle-import:C0805")
      (libsource (lib "eagle-import") (part "C-EUC0805"))
    )
    (comp (ref "C76")
      (value "100nF")
      (footprint "eagle-import:C0805")
      (libsource (lib "eagle-import") (part "C-EUC0805"))
    )
    (comp (ref "C77")
      (value "100nF")
      (footprint "eagle-import:C0805")
      (libsource (lib "eagle-import") (part "C-EUC0805"))
    )
    (comp (ref "C78")
      (value "100nF")
      (footprint "eagle-import:C0805")
      (libsource (lib "eagle-import") (part "C-EUC0805"))
    )
    (comp (ref "C79")
      (value "100nF")
      (footprint "eagle-import:C0805")
      (libsource (lib "eagle-import") (part "C-EUC0805"))
    )
    (comp (ref "C80")
      (value "100nF")
      (footprint "eagle-import:C0805")
      (libsource (lib "eagle-import") (part "C-EUC0805"))
    )
    (comp (ref "IC12")
      (value "LTC4412HV")
      (footprint "eagle-import:TSOT23-6")
      (libsource (lib "eagle-import") (part "LTC4412HV"))
    )
    (comp (ref "IC13")
      (value "LMP2012")
      (footprint "eagle-import:MSOP08")
      (fields
        (field (name "MF") "TEXAS INSTRUMENTS")
        (field (name "MPN") "OPA2237EA/250")
        (field (name "MPN_1") "OPA2237EA/250")
        (field (name "OC_FARNELL") "1470365")
        (field (name "OC_NEWARK") "35C1853")
      )
      (libsource (lib "eagle-import") (part "OPA2237E"))
    )
    (comp (ref "IC14")
      (value "LTC4412HV")
      (footprint "eagle-import:TSOT23-6")
      (libsource (lib "eagle-import") (part "LTC4412HV"))
    )
    (comp (ref "IC15")
      (value "LTC4412HV")
      (footprint "eagle-import:TSOT23-6")
      (libsource (lib "eagle-import") (part "LTC4412HV"))
    )
    (comp (ref "IC16")
      (value "LTC4412HV")
      (footprint "eagle-import:TSOT23-6")
      (libsource (lib "eagle-import") (part "LTC4412HV"))
    )
    (comp (ref "IC17")
      (value "4051D")
      (footprint "eagle-import:SO16")
      (libsource (lib "eagle-import") (part "4051D"))
    )
    (comp (ref "Q4")
      (value "FDN360P")
      (footprint "eagle-import:SUPER-SOT3")
      (libsource (lib "eagle-import") (part "FDN360P"))
    )
    (comp (ref "Q5")
      (value "FDN360P")
      (footprint "eagle-import:SUPER-SOT3")
      (libsource (lib "eagle-import") (part "FDN360P"))
    )
    (comp (ref "Q6")
      (value "FDN360P")
      (footprint "eagle-import:SUPER-SOT3")
      (libsource (lib "eagle-import") (part "FDN360P"))
    )
    (comp (ref "Q7")
      (value "FDN360P")
      (footprint "eagle-import:SUPER-SOT3")
      (libsource (lib "eagle-import") (part "FDN360P"))
    )
    (comp (ref "R54")
      (value "22k")
      (footprint "eagle-import:M0805")
      (libsource (lib "eagle-import") (part "R-EU_M0805"))
    )
    (comp (ref "R55")
      (value "22k")
      (footprint "eagle-import:M0805")
      (libsource (lib "eagle-import") (part "R-EU_M0805"))
    )
    (comp (ref "R78")
      (value "220k")
      (footprint "eagle-import:M0805")
      (libsource (lib "eagle-import") (part "R-EU_M0805"))
    )
    (comp (ref "R79")
      (value "10k")
      (footprint "eagle-import:M0805")
      (libsource (lib "eagle-import") (part "R-EU_M0805"))
    )
    (comp (ref "R80")
      (value "10k")
      (footprint "eagle-import:M0805")
      (libsource (lib "eagle-import") (part "R-EU_M0805"))
    )
    (comp (ref "R81")
      (value "220k")
      (footprint "eagle-import:M0805")
      (libsource (lib "eagle-import") (part "R-EU_M0805"))
    )
    (comp (ref "R82")
      (value "0.1R")
      (footprint "eagle-import:_2818")
      (libsource (lib "eagle-import") (part "RESISTOR2818"))
    )
    (comp (ref "SJ6")
      (value "VSEL")
      (footprint "eagle-import:SJ_2")
      (libsource (lib "eagle-import") (part "SJ2W"))
    )
    (comp (ref "C25")
      (value "100nF")
      (footprint "eagle-import:C0805")
      (libsource (lib "eagle-import") (part "C-EUC0805"))
    )
    (comp (ref "C26")
      (value "10uF")
      (footprint "eagle-import:C0805")
      (libsource (lib "eagle-import") (part "C-EUC0805"))
    )
    (comp (ref "C31")
      (value "100nF")
      (footprint "eagle-import:C0805")
      (libsource (lib "eagle-import") (part "C-EUC0805"))
    )
    (comp (ref "C32")
      (value "100nF")
      (footprint "eagle-import:C0805")
      (libsource (lib "eagle-import") (part "C-EUC0805"))
    )
    (comp (ref "C33")
      (value "100nF")
      (footprint "eagle-import:C0805")
      (libsource (lib "eagle-import") (part "C-EUC0805"))
    )
    (comp (ref "C34")
      (value "100nF")
      (footprint "eagle-import:C0805")
      (libsource (lib "eagle-import") (part "C-EUC0805"))
    )
    (comp (ref "C39")
      (value "100nF")
      (footprint "eagle-import:C0805")
      (libsource (lib "eagle-import") (part "C-EUC0805"))
    )
    (comp (ref "C67")
      (value "10uF")
      (footprint "eagle-import:C0805")
      (libsource (lib "eagle-import") (part "C-EUC0805"))
    )
    (comp (ref "C68")
      (value "10uF")
      (footprint "eagle-import:C0805")
      (libsource (lib "eagle-import") (part "C-EUC0805"))
    )
    (comp (ref "C69")
      (value "10uF")
      (footprint "eagle-import:C0805")
      (libsource (lib "eagle-import") (part "C-EUC0805"))
    )
    (comp (ref "C70")
      (value "27pF")
      (footprint "eagle-import:C0805")
      (libsource (lib "eagle-import") (part "C-EUC0805"))
    )
    (comp (ref "C71")
      (value "27pF")
      (footprint "eagle-import:C0805")
      (libsource (lib "eagle-import") (part "C-EUC0805"))
    )
    (comp (ref "CAN")
      (value "CON_HEADER_1X04")
      (footprint "eagle-import:M1X4")
      (libsource (lib "eagle-import") (part "CON_HEADER_1X04"))
    )
    (comp (ref "DEBUG")
      (value "CON_HEADER_2X03-PTH")
      (footprint "eagle-import:M2X3")
      (libsource (lib "eagle-import") (part "CON_HEADER_2X03-PTH"))
    )
    (comp (ref "IC9")
      (value "PIC18F66K80")
      (footprint "eagle-import:TQFP64-10X10X1MM")
      (libsource (lib "eagle-import") (part "PIC18F66K80"))
    )
    (comp (ref "IC11")
      (value "MCP2551")
      (footprint "eagle-import:SO-08")
      (libsource (lib "eagle-import") (part "MCP2551"))
    )
    (comp (ref "ICSP")
      (value "CON_HEADER_PRG_PIC_ICSP0.1INCH_B")
      (footprint "eagle-import:HEADER_PRG_1X05_ICSP_B")
      (libsource (lib "eagle-import") (part "CON_HEADER_PRG_PIC_ICSP0.1INCH_B"))
    )
    (comp (ref "JP2")
      (value "HEADER-1X2ROUND")
      (footprint "eagle-import:1X02_ROUND")
      (libsource (lib "eagle-import") (part "HEADER-1X2ROUND"))
    )
    (comp (ref "LED1")
      (value "GREEN")
      (footprint "eagle-import:CHIPLED_0805")
      (libsource (lib "eagle-import") (part "LED0805"))
    )
    (comp (ref "LED2")
      (value "GREEN")
      (footprint "eagle-import:CHIPLED_0805")
      (libsource (lib "eagle-import") (part "LED0805"))
    )
    (comp (ref "LED3")
      (value "GREEN")
      (footprint "eagle-import:CHIPLED_0805")
      (libsource (lib "eagle-import") (part "LED0805"))
    )
    (comp (ref "Q3")
      (value "4MHz")
      (footprint "eagle-import:HC49_S")
      (libsource (lib "eagle-import") (part "CRYSTALHC49S"))
    )
    (comp (ref "R47")
      (value "470R")
      (footprint "eagle-import:M0805")
      (libsource (lib "eagle-import") (part "R-EU_M0805"))
    )
    (comp (ref "R48")
      (value "470R")
      (footprint "eagle-import:M0805")
      (libsource (lib "eagle-import") (part "R-EU_M0805"))
    )
    (comp (ref "R49")
      (value "470R")
      (footprint "eagle-import:M0805")
      (libsource (lib "eagle-import") (part "R-EU_M0805"))
    )
    (comp (ref "R50")
      (value "470R")
      (footprint "eagle-import:M0805")
      (libsource (lib "eagle-import") (part "R-EU_M0805"))
    )
    (comp (ref "R51")
      (value "10k")
      (footprint "eagle-import:M0805")
      (libsource (lib "eagle-import") (part "R-EU_M0805"))
    )
    (comp (ref "R52")
      (value "10k")
      (footprint "eagle-import:M0805")
      (libsource (lib "eagle-import") (part "R-EU_M0805"))
    )
    (comp (ref "R53")
      (value "10k")
      (footprint "eagle-import:M0805")
      (libsource (lib "eagle-import") (part "R-EU_M0805"))
    )
    (comp (ref "R56")
      (value "10k")
      (footprint "eagle-import:M0805")
      (libsource (lib "eagle-import") (part "R-EU_M0805"))
    )
    (comp (ref "R63")
      (value "R-EU_M0805")
      (footprint "eagle-import:M0805")
      (libsource (lib "eagle-import") (part "R-EU_M0805"))
    )
    (comp (ref "R64")
      (value "120R")
      (footprint "eagle-import:M0805")
      (libsource (lib "eagle-import") (part "R-EU_M0805"))
    )
    (comp (ref "SERIAL")
      (value "CON_HEADER_1X04")
      (footprint "eagle-import:M1X4")
      (libsource (lib "eagle-import") (part "CON_HEADER_1X04"))
    )
    (comp (ref "C19")
      (value "100nF")
      (footprint "eagle-import:C0805")
      (libsource (lib "eagle-import") (part "C-EUC0805"))
    )
    (comp (ref "C20")
      (value "100nF")
      (footprint "eagle-import:C0805")
      (libsource (lib "eagle-import") (part "C-EUC0805"))
    )
    (comp (ref "C38")
      (value "100nF")
      (footprint "eagle-import:C0805")
      (libsource (lib "eagle-import") (part "C-EUC0805"))
    )
    (comp (ref "IC4")
      (value "LTC4412HV")
      (footprint "eagle-import:TSOT23-6")
      (libsource (lib "eagle-import") (part "LTC4412HV"))
    )
    (comp (ref "IC8")
      (value "LMP2012")
      (footprint "eagle-import:MSOP08")
      (fields
        (field (name "MF") "TEXAS INSTRUMENTS")
        (field (name "MPN") "OPA2237EA/250")
        (field (name "MPN_1") "OPA2237EA/250")
        (field (name "OC_FARNELL") "1470365")
        (field (name "OC_NEWARK") "35C1853")
      )
      (libsource (lib "eagle-import") (part "OPA2237E"))
    )
    (comp (ref "Q2")
      (value "FDN360P")
      (footprint "eagle-import:SUPER-SOT3")
      (libsource (lib "eagle-import") (part "FDN360P"))
    )
    (comp (ref "R39")
      (value "22k")
      (footprint "eagle-import:M0805")
      (libsource (lib "eagle-import") (part "R-EU_M0805"))
    )
    (comp (ref "R40")
      (value "22k")
      (footprint "eagle-import:M0805")
      (libsource (lib "eagle-import") (part "R-EU_M0805"))
    )
    (comp (ref "R41")
      (value "220k")
      (footprint "eagle-import:M0805")
      (libsource (lib "eagle-import") (part "R-EU_M0805"))
    )
    (comp (ref "R42")
      (value "10k")
      (footprint "eagle-import:M0805")
      (libsource (lib "eagle-import") (part "R-EU_M0805"))
    )
    (comp (ref "R43")
      (value "10k")
      (footprint "eagle-import:M0805")
      (libsource (lib "eagle-import") (part "R-EU_M0805"))
    )
    (comp (ref "R44")
      (value "0.1R")
      (footprint "eagle-import:_2818")
      (libsource (lib "eagle-import") (part "RESISTOR2818"))
    )
    (comp (ref "R77")
      (value "220k")
      (footprint "eagle-import:M0805")
      (libsource (lib "eagle-import") (part "R-EU_M0805"))
    )
    (comp (ref "C8")
      (value "100nF")
      (footprint "eagle-import:C0805")
      (libsource (lib "eagle-import") (part "C-EUC0805"))
    )
    (comp (ref "C11")
      (value "22uF")
      (footprint "eagle-import:EIA6032-28_C-R")
      (libsource (lib "eagle-import") (part "CAP_TANTALUMC/6032_REFLOW"))
    )
    (comp (ref "C12")
      (value "47uF")
      (footprint "eagle-import:EIA6032-28_C-R")
      (libsource (lib "eagle-import") (part "CAP_TANTALUMC/6032_REFLOW"))
    )
    (comp (ref "C17")
      (value "100nF")
      (footprint "eagle-import:C0805")
      (libsource (lib "eagle-import") (part "C-EUC0805"))
    )
    (comp (ref "C18")
      (value "100nF")
      (footprint "eagle-import:C0805")
      (libsource (lib "eagle-import") (part "C-EUC0805"))
    )
    (comp (ref "C37")
      (value "100nF")
      (footprint "eagle-import:C0805")
      (libsource (lib "eagle-import") (part "C-EUC0805"))
    )
    (comp (ref "C61")
      (value "100nF")
      (footprint "eagle-import:C0805")
      (libsource (lib "eagle-import") (part "C-EUC0805"))
    )
    (comp (ref "C62")
      (value "100nF")
      (footprint "eagle-import:C0805")
      (libsource (lib "eagle-import") (part "C-EUC0805"))
    )
    (comp (ref "IC3")
      (value "LTC4412HV")
      (footprint "eagle-import:TSOT23-6")
      (libsource (lib "eagle-import") (part "LTC4412HV"))
    )
    (comp (ref "IC6")
      (value "LMP2012")
      (footprint "eagle-import:MSOP08")
      (fields
        (field (name "MF") "TEXAS INSTRUMENTS")
        (field (name "MPN") "OPA2237EA/250")
        (field (name "MPN_1") "OPA2237EA/250")
        (field (name "OC_FARNELL") "1470365")
        (field (name "OC_NEWARK") "35C1853")
      )
      (libsource (lib "eagle-import") (part "OPA2237E"))
    )
    (comp (ref "L2")
      (value "2.2uH")
      (footprint "eagle-import:SRR6038")
      (fields (field (name "MANUFACTURER_PART_NUMBER") "SRR6038-3R3Y"))
      (libsource (lib "eagle-import") (part "SRR6038-3R3Y"))
    )
    (comp (ref "R9")
      (value "33.2k")
      (footprint "eagle-import:M0805")
      (libsource (lib "eagle-import") (part "R-EU_M0805"))
    )
    (comp (ref "R10")
      (value "10k")
      (footprint "eagle-import:M0805")
      (libsource (lib "eagle-import") (part "R-EU_M0805"))
    )
    (comp (ref "R19")
      (value "680k")
      (footprint "eagle-import:M0805")
      (libsource (lib "eagle-import") (part "R-EU_M0805"))
    )
    (comp (ref "R33")
      (value "22k")
      (footprint "eagle-import:M0805")
      (libsource (lib "eagle-import") (part "R-EU_M0805"))
    )
    (comp (ref "R34")
      (value "22k")
      (footprint "eagle-import:M0805")
      (libsource (lib "eagle-import") (part "R-EU_M0805"))
    )
    (comp (ref "R35")
      (value "220k")
      (footprint "eagle-import:M0805")
      (libsource (lib "eagle-import") (part "R-EU_M0805"))
    )
    (comp (ref "R36")
      (value "10k")
      (footprint "eagle-import:M0805")
      (libsource (lib "eagle-import") (part "R-EU_M0805"))
    )
    (comp (ref "R37")
      (value "10k")
      (footprint "eagle-import:M0805")
      (libsource (lib "eagle-import") (part "R-EU_M0805"))
    )
    (comp (ref "R38")
      (value "0.1R")
      (footprint "eagle-import:_2818")
      (libsource (lib "eagle-import") (part "RESISTOR2818"))
    )
    (comp (ref "R71")
      (value "220k")
      (footprint "eagle-import:M0805")
      (libsource (lib "eagle-import") (part "R-EU_M0805"))
    )
    (comp (ref "R72")
      (value "17.4k")
      (footprint "eagle-import:M0805")
      (libsource (lib "eagle-import") (part "R-EU_M0805"))
    )
    (comp (ref "R73")
      (value "10k")
      (footprint "eagle-import:M0805")
      (libsource (lib "eagle-import") (part "R-EU_M0805"))
    )
    (comp (ref "R74")
      (value "3.4k")
      (footprint "eagle-import:M0805")
      (libsource (lib "eagle-import") (part "R-EU_M0805"))
    )
    (comp (ref "R75")
      (value "3.4k")
      (footprint "eagle-import:M0805")
      (libsource (lib "eagle-import") (part "R-EU_M0805"))
    )
    (comp (ref "R76")
      (value "680k")
      (footprint "eagle-import:M0805")
      (libsource (lib "eagle-import") (part "R-EU_M0805"))
    )
    (comp (ref "SJ4")
      (value "SOLDERJUMPER")
      (footprint "eagle-import:SOLDERJUMPER_ARROW_NOPASTE")
      (libsource (lib "eagle-import") (part "SOLDERJUMPER"))
    )
    (comp (ref "T5")
      (value "Si9933CDY")
      (footprint "eagle-import:SO8")
      (libsource (lib "eagle-import") (part "PMOS2SO8"))
    )
    (comp (ref "T6")
      (value "Si9933CDY")
      (footprint "eagle-import:SO8")
      (libsource (lib "eagle-import") (part "PMOS2SO8"))
    )
    (comp (ref "TP6")
      (value "TESTPOINT0.1\"")
      (footprint "eagle-import:1X01_ROUND")
      (libsource (lib "eagle-import") (part "TESTPOINT0.1{dblquote}"))
    )
    (comp (ref "TP7")
      (value "TESTPOINT0.1\"")
      (footprint "eagle-import:1X01_ROUND")
      (fields (field (name "BOM") "EXCLUDE"))
      (libsource (lib "eagle-import") (part "TESTPOINT0.1{dblquote}"))
    )
    (comp (ref "U2")
      (value "TPS563200DDCR")
      (footprint "eagle-import:DDC0006A")
      (fields
        (field (name "MANUFACTURER") "Texas Instruments")
        (field (name "PARTNUMBER") "TPS563200DDC")
        (field (name "APPROVEDBY") "Not shown in title block")
        (field (name "AUTHOR") "Not shown in title block")
        (field (name "CHECKEDBY") "Not shown in title block")
        (field (name "ENGINEER") "Not shown in title block")
        (field (name "MODIFIEDDATE") "Not shown in title block")
        (field (name "PUBLISHER") "Texas Instruments")
        (field (name "SYMBOLCREATOR") "a0411947")
      )
      (libsource (lib "eagle-import") (part "TPS563200DDCR"))
    )
    (comp (ref "C40")
      (value "3300pF")
      (footprint "eagle-import:C0805")
      (libsource (lib "eagle-import") (part "C-EUC0805"))
    )
    (comp (ref "C41")
      (value "1500pF")
      (footprint "eagle-import:C0805")
      (libsource (lib "eagle-import") (part "C-EUC0805"))
    )
    (comp (ref "C42")
      (value "1500pF")
      (footprint "eagle-import:C0805")
      (libsource (lib "eagle-import") (part "C-EUC0805"))
    )
    (comp (ref "C43")
      (value "1500pF")
      (footprint "eagle-import:C0805")
      (libsource (lib "eagle-import") (part "C-EUC0805"))
    )
    (comp (ref "C44")
      (value "1000pF")
      (footprint "eagle-import:C0805")
      (libsource (lib "eagle-import") (part "C-EUC0805"))
    )
    (comp (ref "C45")
      (value "0.022uF")
      (footprint "eagle-import:C0805")
      (libsource (lib "eagle-import") (part "C-EUC0805"))
    )
    (comp (ref "C46")
      (value "100nF")
      (footprint "eagle-import:C0805")
      (libsource (lib "eagle-import") (part "C-EUC0805"))
    )
    (comp (ref "C47")
      (value "22uF")
      (footprint "eagle-import:EIA6032-28_C-R")
      (libsource (lib "eagle-import") (part "CAP_TANTALUMC/6032_REFLOW"))
    )
    (comp (ref "C48")
      (value "22uF")
      (footprint "eagle-import:EIA6032-28_C-R")
      (libsource (lib "eagle-import") (part "CAP_TANTALUMC/6032_REFLOW"))
    )
    (comp (ref "C49")
      (value "100nF")
      (footprint "eagle-import:C0805")
      (libsource (lib "eagle-import") (part "C-EUC0805"))
    )
    (comp (ref "C50")
      (value "100nF")
      (footprint "eagle-import:C0805")
      (libsource (lib "eagle-import") (part "C-EUC0805"))
    )
    (comp (ref "C51")
      (value "100nF")
      (footprint "eagle-import:C1210")
      (libsource (lib "eagle-import") (part "C-EUC1210"))
    )
    (comp (ref "C52")
      (value "22uF")
      (footprint "eagle-import:EIA6032-28_C-R")
      (libsource (lib "eagle-import") (part "CAP_TANTALUMC/6032_REFLOW"))
    )
    (comp (ref "C53")
      (value "100nF")
      (footprint "eagle-import:C0805")
      (libsource (lib "eagle-import") (part "C-EUC0805"))
    )
    (comp (ref "C54")
      (value "22uF")
      (footprint "eagle-import:EIA6032-28_C-R")
      (libsource (lib "eagle-import") (part "CAP_TANTALUMC/6032_REFLOW"))
    )
    (comp (ref "C55")
      (value "100nF")
      (footprint "eagle-import:C0805")
      (libsource (lib "eagle-import") (part "C-EUC0805"))
    )
    (comp (ref "D1")
      (value "B340A-13-F")
      (footprint "eagle-import:DO214AC")
      (libsource (lib "eagle-import") (part "DIODE-DO214AC"))
    )
    (comp (ref "D2")
      (value "B340A-13-F")
      (footprint "eagle-import:DO214AC")
      (libsource (lib "eagle-import") (part "DIODE-DO214AC"))
    )
    (comp (ref "D3")
      (value "B340A-13-F")
      (footprint "eagle-import:DO214AC")
      (libsource (lib "eagle-import") (part "DIODE-DO214AC"))
    )
    (comp (ref "D4")
      (value "B340A-13-F")
      (footprint "eagle-import:DO214AC")
      (libsource (lib "eagle-import") (part "DIODE-DO214AC"))
    )
    (comp (ref "D5")
      (value "B340A-13-F")
      (footprint "eagle-import:DO214AC")
      (libsource (lib "eagle-import") (part "DIODE-DO214AC"))
    )
    (comp (ref "L5")
      (value "3.3uH")
      (footprint "eagle-import:SRR6038")
      (fields (field (name "MANUFACTURER_PART_NUMBER") "SRR6038-3R3Y"))
      (libsource (lib "eagle-import") (part "SRR6038-3R3Y"))
    )
    (comp (ref "L6")
      (value "10uH")
      (footprint "eagle-import:SRR6038")
      (fields (field (name "MANUFACTURER_PART_NUMBER") "SRR6038-3R3Y"))
      (libsource (lib "eagle-import") (part "SRR6038-3R3Y"))
    )
    (comp (ref "L7")
      (value "3.3uH")
      (footprint "eagle-import:SRR6038")
      (fields (field (name "MANUFACTURER_PART_NUMBER") "SRR6038-3R3Y"))
      (libsource (lib "eagle-import") (part "SRR6038-3R3Y"))
    )
    (comp (ref "R14")
      (value "100k")
      (footprint "eagle-import:M0805")
      (libsource (lib "eagle-import") (part "R-EU_M0805"))
    )
    (comp (ref "R15")
      (value "100k")
      (footprint "eagle-import:M0805")
      (libsource (lib "eagle-import") (part "R-EU_M0805"))
    )
    (comp (ref "R17")
      (value "100k")
      (footprint "eagle-import:M0805")
      (libsource (lib "eagle-import") (part "R-EU_M0805"))
    )
    (comp (ref "R18")
      (value "100k")
      (footprint "eagle-import:M0805")
      (libsource (lib "eagle-import") (part "R-EU_M0805"))
    )
    (comp (ref "R59")
      (value "100k")
      (footprint "eagle-import:M0805")
      (libsource (lib "eagle-import") (part "R-EU_M0805"))
    )
    (comp (ref "R60")
      (value "2k2")
      (footprint "eagle-import:M0805")
      (libsource (lib "eagle-import") (part "R-EU_M0805"))
    )
    (comp (ref "R61")
      (value "10k")
      (footprint "eagle-import:M0805")
      (libsource (lib "eagle-import") (part "R-EU_M0805"))
    )
    (comp (ref "R62")
      (value "1k5")
      (footprint "eagle-import:M0805")
      (libsource (lib "eagle-import") (part "R-EU_M0805"))
    )
    (comp (ref "R65")
      (value "10k7")
      (footprint "eagle-import:M0805")
      (libsource (lib "eagle-import") (part "R-EU_M0805"))
    )
    (comp (ref "R66")
      (value "2k49")
      (footprint "eagle-import:M0805")
      (libsource (lib "eagle-import") (part "R-EU_M0805"))
    )
    (comp (ref "R67")
      (value "115k")
      (footprint "eagle-import:M0805")
      (libsource (lib "eagle-import") (part "R-EU_M0805"))
    )
    (comp (ref "R68")
      (value "13k3")
      (footprint "eagle-import:M0805")
      (libsource (lib "eagle-import") (part "R-EU_M0805"))
    )
    (comp (ref "R69")
      (value "17K4")
      (footprint "eagle-import:M0805")
      (libsource (lib "eagle-import") (part "R-EU_M0805"))
    )
    (comp (ref "R70")
      (value "2k49")
      (footprint "eagle-import:M0805")
      (libsource (lib "eagle-import") (part "R-EU_M0805"))
    )
    (comp (ref "U5")
      (value "LT1941EFEPBF")
      (footprint "eagle-import:SOP65P640X120-29N")
      (fields (field (name "MPN") "LT1941EFE#PBF"))
      (libsource (lib "eagle-import") (part "LT1941EFEPBF"))
    )
    (comp (ref "BAT")
      (value "HEADER-1X2")
      (footprint "eagle-import:1X02_OVAL")
      (libsource (lib "eagle-import") (part "HEADER-1X2"))
    )
    (comp (ref "C21")
      (value "100nF")
      (footprint "eagle-import:C0805")
      (libsource (lib "eagle-import") (part "C-EUC0805"))
    )
    (comp (ref "C22")
      (value "22uF")
      (footprint "eagle-import:EIA6032-28_C-R")
      (libsource (lib "eagle-import") (part "CAP_TANTALUMC/6032_REFLOW"))
    )
    (comp (ref "C23")
      (value "220nF")
      (footprint "eagle-import:C0805")
      (libsource (lib "eagle-import") (part "C-EUC0805"))
    )
    (comp (ref "C24")
      (value "1uF")
      (footprint "eagle-import:C0805")
      (libsource (lib "eagle-import") (part "C-EUC0805"))
    )
    (comp (ref "C27")
      (value "100nF")
      (footprint "eagle-import:C0805")
      (libsource (lib "eagle-import") (part "C-EUC0805"))
    )
    (comp (ref "C63")
      (value "100nF")
      (footprint "eagle-import:C0805")
      (libsource (lib "eagle-import") (part "C-EUC0805"))
    )
    (comp (ref "C64")
      (value "100nF")
      (footprint "eagle-import:C0805")
      (libsource (lib "eagle-import") (part "C-EUC0805"))
    )
    (comp (ref "FOTOCELULA")
      (value "HEADER-1X2")
      (footprint "eagle-import:1X02_OVAL")
      (libsource (lib "eagle-import") (part "HEADER-1X2"))
    )
    (comp (ref "IC10")
      (value "TMP35B")
      (footprint "eagle-import:TO92-LINE")
      (libsource (lib "eagle-import") (part "TMP35B"))
    )
    (comp (ref "LED4")
      (value "GREEN")
      (footprint "eagle-import:CHIPLED_0805")
      (libsource (lib "eagle-import") (part "LED0805"))
    )
    (comp (ref "LED5")
      (value "GREEN")
      (footprint "eagle-import:CHIPLED_0805")
      (libsource (lib "eagle-import") (part "LED0805"))
    )
    (comp (ref "R45")
      (value "0.1R")
      (footprint "eagle-import:_2818")
      (libsource (lib "eagle-import") (part "RESISTOR2818"))
    )
    (comp (ref "R83")
      (value "40k")
      (footprint "eagle-import:M0805")
      (libsource (lib "eagle-import") (part "R-EU_M0805"))
    )
    (comp (ref "R84")
      (value "11.5k")
      (footprint "eagle-import:M0805")
      (libsource (lib "eagle-import") (part "R-EU_M0805"))
    )
    (comp (ref "R85")
      (value "470R")
      (footprint "eagle-import:M0805")
      (libsource (lib "eagle-import") (part "R-EU_M0805"))
    )
    (comp (ref "R86")
      (value "470R")
      (footprint "eagle-import:M0805")
      (libsource (lib "eagle-import") (part "R-EU_M0805"))
    )
    (comp (ref "SJ1")
      (value "VSEL")
      (footprint "eagle-import:SJ_2")
      (libsource (lib "eagle-import") (part "SJ2W"))
    )
    (comp (ref "SJ2")
      (value "TMRSEL")
      (footprint "eagle-import:SJ_2")
      (libsource (lib "eagle-import") (part "SJ2W"))
    )
    (comp (ref "SJ7")
      (value "SOLDERJUMPER")
      (footprint "eagle-import:SOLDERJUMPER_ARROW_NOPASTE")
      (libsource (lib "eagle-import") (part "SOLDERJUMPER"))
    )
    (comp (ref "U3")
      (value "BQ24005_PWP_20C")
      (footprint "eagle-import:PWP20_2P4X3P4-M")
      (libsource (lib "eagle-import") (part "BQ24005_PWP_20C"))
    )
    (comp (ref "C6")
      (value "100nF")
      (footprint "eagle-import:C0805")
      (libsource (lib "eagle-import") (part "C-EUC0805"))
    )
    (comp (ref "C9")
      (value "22uF")
      (footprint "eagle-import:EIA6032-28_C-R")
      (libsource (lib "eagle-import") (part "CAP_TANTALUMC/6032_REFLOW"))
    )
    (comp (ref "C10")
      (value "47uF")
      (footprint "eagle-import:EIA6032-28_C-R")
      (libsource (lib "eagle-import") (part "CAP_TANTALUMC/6032_REFLOW"))
    )
    (comp (ref "C15")
      (value "100nF")
      (footprint "eagle-import:C0805")
      (libsource (lib "eagle-import") (part "C-EUC0805"))
    )
    (comp (ref "C16")
      (value "100nF")
      (footprint "eagle-import:C0805")
      (libsource (lib "eagle-import") (part "C-EUC0805"))
    )
    (comp (ref "C35")
      (value "100nF")
      (footprint "eagle-import:C0805")
      (libsource (lib "eagle-import") (part "C-EUC0805"))
    )
    (comp (ref "C59")
      (value "100nF")
      (footprint "eagle-import:C0805")
      (libsource (lib "eagle-import") (part "C-EUC0805"))
    )
    (comp (ref "C60")
      (value "100nF")
      (footprint "eagle-import:C0805")
      (libsource (lib "eagle-import") (part "C-EUC0805"))
    )
    (comp (ref "IC2")
      (value "LTC4412HV")
      (footprint "eagle-import:TSOT23-6")
      (libsource (lib "eagle-import") (part "LTC4412HV"))
    )
    (comp (ref "IC5")
      (value "LMP2012")
      (footprint "eagle-import:MSOP08")
      (fields
        (field (name "MF") "TEXAS INSTRUMENTS")
        (field (name "MPN") "OPA2237EA/250")
        (field (name "MPN_1") "OPA2237EA/250")
        (field (name "OC_FARNELL") "1470365")
        (field (name "OC_NEWARK") "35C1853")
      )
      (libsource (lib "eagle-import") (part "OPA2237E"))
    )
    (comp (ref "L3")
      (value "3.3uH")
      (footprint "eagle-import:SRR6038")
      (fields (field (name "MANUFACTURER_PART_NUMBER") "SRR6038-3R3Y"))
      (libsource (lib "eagle-import") (part "SRR6038-3R3Y"))
    )
    (comp (ref "R7")
      (value "56.2k")
      (footprint "eagle-import:M0805")
      (libsource (lib "eagle-import") (part "R-EU_M0805"))
    )
    (comp (ref "R8")
      (value "10k")
      (footprint "eagle-import:M0805")
      (libsource (lib "eagle-import") (part "R-EU_M0805"))
    )
    (comp (ref "R16")
      (value "680k")
      (footprint "eagle-import:M0805")
      (libsource (lib "eagle-import") (part "R-EU_M0805"))
    )
    (comp (ref "R20")
      (value "1k5")
      (footprint "eagle-import:M0805")
      (libsource (lib "eagle-import") (part "R-EU_M0805"))
    )
    (comp (ref "R21")
      (value "22k")
      (footprint "eagle-import:M0805")
      (libsource (lib "eagle-import") (part "R-EU_M0805"))
    )
    (comp (ref "R26")
      (value "220k")
      (footprint "eagle-import:M0805")
      (libsource (lib "eagle-import") (part "R-EU_M0805"))
    )
    (comp (ref "R28")
      (value "22k")
      (footprint "eagle-import:M0805")
      (libsource (lib "eagle-import") (part "R-EU_M0805"))
    )
    (comp (ref "R29")
      (value "220k")
      (footprint "eagle-import:M0805")
      (libsource (lib "eagle-import") (part "R-EU_M0805"))
    )
    (comp (ref "R30")
      (value "680k")
      (footprint "eagle-import:M0805")
      (libsource (lib "eagle-import") (part "R-EU_M0805"))
    )
    (comp (ref "R31")
      (value "10k")
      (footprint "eagle-import:M0805")
      (libsource (lib "eagle-import") (part "R-EU_M0805"))
    )
    (comp (ref "R32")
      (value "0.1R")
      (footprint "eagle-import:_2818")
      (libsource (lib "eagle-import") (part "RESISTOR2818"))
    )
    (comp (ref "SJ3")
      (value "SOLDERJUMPER")
      (footprint "eagle-import:SOLDERJUMPER_ARROW_NOPASTE")
      (libsource (lib "eagle-import") (part "SOLDERJUMPER"))
    )
    (comp (ref "T3")
      (value "Si9933CDY")
      (footprint "eagle-import:SO8")
      (libsource (lib "eagle-import") (part "PMOS2SO8"))
    )
    (comp (ref "T4")
      (value "Si9933CDY")
      (footprint "eagle-import:SO8")
      (libsource (lib "eagle-import") (part "PMOS2SO8"))
    )
    (comp (ref "TP1")
      (value "TESTPOINT0.1\"")
      (footprint "eagle-import:1X01_ROUND")
      (libsource (lib "eagle-import") (part "TESTPOINT0.1{dblquote}"))
    )
    (comp (ref "TP2")
      (value "TESTPOINT0.1\"")
      (footprint "eagle-import:1X01_ROUND")
      (fields (field (name "BOM") "EXCLUDE"))
      (libsource (lib "eagle-import") (part "TESTPOINT0.1{dblquote}"))
    )
    (comp (ref "TP3")
      (value "TESTPOINT0.1\"")
      (footprint "eagle-import:1X01_ROUND")
      (fields (field (name "BOM") "EXCLUDE"))
      (libsource (lib "eagle-import") (part "TESTPOINT0.1{dblquote}"))
    )
    (comp (ref "TP4")
      (value "TESTPOINT0.1\"")
      (footprint "eagle-import:1X01_ROUND")
      (fields (field (name "BOM") "EXCLUDE"))
      (libsource (lib "eagle-import") (part "TESTPOINT0.1{dblquote}"))
    )
    (comp (ref "TP5")
      (value "TESTPOINT0.1\"")
      (footprint "eagle-import:1X01_ROUND")
      (fields (field (name "BOM") "EXCLUDE"))
      (libsource (lib "eagle-import") (part "TESTPOINT0.1{dblquote}"))
    )
    (comp (ref "U1")
      (value "TPS563200DDCR")
      (footprint "eagle-import:DDC0006A")
      (fields
        (field (name "MANUFACTURER") "Texas Instruments")
        (field (name "PARTNUMBER") "TPS563200DDC")
        (field (name "APPROVEDBY") "Not shown in title block")
        (field (name "AUTHOR") "Not shown in title block")
        (field (name "CHECKEDBY") "Not shown in title block")
        (field (name "ENGINEER") "Not shown in title block")
        (field (name "MODIFIEDDATE") "Not shown in title block")
        (field (name "PUBLISHER") "Texas Instruments")
        (field (name "SYMBOLCREATOR") "a0411947")
      )
      (libsource (lib "eagle-import") (part "TPS563200DDCR"))
    )
    (comp (ref "+X")
      (value "+X")
      (footprint "eagle-import:1X05")
      (libsource (lib "eagle-import") (part "PINHD-1X5"))
    )
    (comp (ref "+Y")
      (value "+Y")
      (footprint "eagle-import:1X05")
      (libsource (lib "eagle-import") (part "PINHD-1X5"))
    )
    (comp (ref "-X")
      (value "-X")
      (footprint "eagle-import:1X05")
      (libsource (lib "eagle-import") (part "PINHD-1X5"))
    )
    (comp (ref "-Y")
      (value "-Y")
      (footprint "eagle-import:1X05")
      (libsource (lib "eagle-import") (part "PINHD-1X5"))
    )
    (comp (ref "BACKUP")
      (value "HEADER-2X13")
      (footprint "eagle-import:2X13")
      (libsource (lib "eagle-import") (part "HEADER-2X13"))
    )
    (comp (ref "BACKUP1")
      (value "PINHD-2X16")
      (footprint "eagle-import:2X16")
      (libsource (lib "eagle-import") (part "PINHD-2X16"))
    )
    (comp (ref "V_BUS")
      (value "V_BUS")
      (footprint "eagle-import:2X20")
      (libsource (lib "eagle-import") (part "PINHD-2X20"))
    )
    (comp (ref "C1")
      (value "100nF")
      (footprint "eagle-import:C0805")
      (libsource (lib "eagle-import") (part "C-EUC0805"))
    )
    (comp (ref "C2")
      (value "2.2nF")
      (footprint "eagle-import:C0805")
      (libsource (lib "eagle-import") (part "C-EUC0805"))
    )
    (comp (ref "C3")
      (value "47nF")
      (footprint "eagle-import:C0805")
      (libsource (lib "eagle-import") (part "C-EUC0805"))
    )
    (comp (ref "C4")
      (value "10nF")
      (footprint "eagle-import:C0805")
      (libsource (lib "eagle-import") (part "C-EUC0805"))
    )
    (comp (ref "C5")
      (value "47uF")
      (footprint "eagle-import:EIA6032-28_C-R")
      (libsource (lib "eagle-import") (part "CAP_TANTALUMC/6032_REFLOW"))
    )
    (comp (ref "C7")
      (value "47uF")
      (footprint "eagle-import:EIA6032-28_C-R")
      (libsource (lib "eagle-import") (part "CAP_TANTALUMC/6032_REFLOW"))
    )
    (comp (ref "C13")
      (value "100nF")
      (footprint "eagle-import:C0805")
      (libsource (lib "eagle-import") (part "C-EUC0805"))
    )
    (comp (ref "C14")
      (value "100nF")
      (footprint "eagle-import:C0805")
      (libsource (lib "eagle-import") (part "C-EUC0805"))
    )
    (comp (ref "C36")
      (value "100nF")
      (footprint "eagle-import:C0805")
      (libsource (lib "eagle-import") (part "C-EUC0805"))
    )
    (comp (ref "C56")
      (value "47uF")
      (footprint "eagle-import:EIA6032-28_C-R")
      (libsource (lib "eagle-import") (part "CAP_TANTALUMC/6032_REFLOW"))
    )
    (comp (ref "C57")
      (value "47uF")
      (footprint "eagle-import:EIA6032-28_C-R")
      (libsource (lib "eagle-import") (part "CAP_TANTALUMC/6032_REFLOW"))
    )
    (comp (ref "C58")
      (value "100nF")
      (footprint "eagle-import:C0805")
      (libsource (lib "eagle-import") (part "C-EUC0805"))
    )
    (comp (ref "D6")
      (value "B340A-13-F")
      (footprint "eagle-import:DO214AC")
      (libsource (lib "eagle-import") (part "DIODE-DO214AC"))
    )
    (comp (ref "IC1")
      (value "LTC4412HV")
      (footprint "eagle-import:TSOT23-6")
      (libsource (lib "eagle-import") (part "LTC4412HV"))
    )
    (comp (ref "IC7")
      (value "LMP2012")
      (footprint "eagle-import:MSOP08")
      (fields
        (field (name "MF") "TEXAS INSTRUMENTS")
        (field (name "MPN") "OPA2237EA/250")
        (field (name "MPN_1") "OPA2237EA/250")
        (field (name "OC_FARNELL") "1470365")
        (field (name "OC_NEWARK") "35C1853")
      )
      (libsource (lib "eagle-import") (part "OPA2237E"))
    )
    (comp (ref "L1")
      (value "33uH")
      (footprint "eagle-import:SDR1307")
      (fields (field (name "MANUFACTURER_PART_NUMBER") "SDR1307-330KL"))
      (libsource (lib "eagle-import") (part "SDR1307-330KL"))
    )
    (comp (ref "Q1")
      (value "CSD16323Q3")
      (footprint "eagle-import:TRANS_NEXFET_Q3")
      (libsource (lib "eagle-import") (part "CSD16323Q3"))
    )
    (comp (ref "R1")
      (value "3.4k")
      (footprint "eagle-import:M0805")
      (libsource (lib "eagle-import") (part "R-EU_M0805"))
    )
    (comp (ref "R2")
      (value "71.5k")
      (footprint "eagle-import:M0805")
      (libsource (lib "eagle-import") (part "R-EU_M0805"))
    )
    (comp (ref "R3")
      (value "100")
      (footprint "eagle-import:M0805")
      (libsource (lib "eagle-import") (part "R-EU_M0805"))
    )
    (comp (ref "R4")
      (value "0.033R")
      (footprint "eagle-import:M1206")
      (libsource (lib "eagle-import") (part "R-EU_M1206"))
    )
    (comp (ref "R5")
      (value "1k")
      (footprint "eagle-import:M0805")
      (libsource (lib "eagle-import") (part "R-EU_M0805"))
    )
    (comp (ref "R6")
      (value "8.45k")
      (footprint "eagle-import:M0805")
      (libsource (lib "eagle-import") (part "R-EU_M0805"))
    )
    (comp (ref "R11")
      (value "220k")
      (footprint "eagle-import:M0805")
      (libsource (lib "eagle-import") (part "R-EU_M0805"))
    )
    (comp (ref "R12")
      (value "680k")
      (footprint "eagle-import:M0805")
      (libsource (lib "eagle-import") (part "R-EU_M0805"))
    )
    (comp (ref "R13")
      (value "680k")
      (footprint "eagle-import:M0805")
      (libsource (lib "eagle-import") (part "R-EU_M0805"))
    )
    (comp (ref "R22")
      (value "22k")
      (footprint "eagle-import:M0805")
      (libsource (lib "eagle-import") (part "R-EU_M0805"))
    )
    (comp (ref "R23")
      (value "22k")
      (footprint "eagle-import:M0805")
      (libsource (lib "eagle-import") (part "R-EU_M0805"))
    )
    (comp (ref "R24")
      (value "220k")
      (footprint "eagle-import:M0805")
      (libsource (lib "eagle-import") (part "R-EU_M0805"))
    )
    (comp (ref "R25")
      (value "33.2k")
      (footprint "eagle-import:M0805")
      (libsource (lib "eagle-import") (part "R-EU_M0805"))
    )
    (comp (ref "R27")
      (value "0.1R")
      (footprint "eagle-import:_2818")
      (libsource (lib "eagle-import") (part "RESISTOR2818"))
    )
    (comp (ref "R46")
      (value "22k")
      (footprint "eagle-import:M0805")
      (libsource (lib "eagle-import") (part "R-EU_M0805"))
    )
    (comp (ref "T1")
      (value "Si9933CDY")
      (footprint "eagle-import:SO8")
      (libsource (lib "eagle-import") (part "PMOS2SO8"))
    )
    (comp (ref "T2")
      (value "Si9933CDY")
      (footprint "eagle-import:SO8")
      (libsource (lib "eagle-import") (part "PMOS2SO8"))
    )
    (comp (ref "TP10")
      (value "TESTPOINT0.1\"")
      (footprint "eagle-import:1X01_ROUND")
      (libsource (lib "eagle-import") (part "TESTPOINT0.1{dblquote}"))
    )
    (comp (ref "TP11")
      (value "TESTPOINT0.1\"")
      (footprint "eagle-import:1X01_ROUND")
      (fields (field (name "BOM") "EXCLUDE"))
      (libsource (lib "eagle-import") (part "TESTPOINT0.1{dblquote}"))
    )
    (comp (ref "U6")
      (value "LM3488MM/NOPB")
      (footprint "eagle-import:MUA08A")
      (libsource (lib "eagle-import") (part "LM3488MM/NOPB"))
    )
  )
  (nets
    (net (code "1") (name "+3V3") (class "Default")
      (node (ref "R34") (pin "2") (pinfunction "2_2") (pintype "passive"))
      (node (ref "R36") (pin "1") (pinfunction "1_1") (pintype "passive"))
      (node (ref "R38") (pin "2") (pinfunction "2_2") (pintype "passive"))
      (node (ref "V_BUS") (pin "21") (pinfunction "21_21") (pintype "passive"))
      (node (ref "V_BUS") (pin "23") (pinfunction "23_23") (pintype "passive"))
      (node (ref "V_BUS") (pin "25") (pinfunction "25_25") (pintype "passive"))
      (node (ref "V_BUS") (pin "27") (pinfunction "27_27") (pintype "passive"))
      (node (ref "V_BUS") (pin "29") (pinfunction "29_29") (pintype "passive"))
    )
    (net (code "2") (name "+5V") (class "Default")
      (node (ref "D7") (pin "A") (pinfunction "A_A") (pintype "passive"))
      (node (ref "R20") (pin "1") (pinfunction "1_1") (pintype "passive"))
      (node (ref "R28") (pin "2") (pinfunction "2_2") (pintype "passive"))
      (node (ref "R32") (pin "2") (pinfunction "2_2") (pintype "passive"))
      (node (ref "TP5") (pin "1") (pinfunction "P$1_1") (pintype "bidirectional"))
      (node (ref "V_BUS") (pin "11") (pinfunction "11_11") (pintype "passive"))
      (node (ref "V_BUS") (pin "13") (pinfunction "13_13") (pintype "passive"))
      (node (ref "V_BUS") (pin "15") (pinfunction "15_15") (pintype "passive"))
      (node (ref "V_BUS") (pin "17") (pinfunction "17_17") (pintype "passive"))
      (node (ref "V_BUS") (pin "19") (pinfunction "19_19") (pintype "passive"))
    )
    (net (code "3") (name "+12V") (class "Default")
      (node (ref "R23") (pin "2") (pinfunction "2_2") (pintype "passive"))
      (node (ref "R25") (pin "1") (pinfunction "1_1") (pintype "passive"))
      (node (ref "R27") (pin "2") (pinfunction "2_2") (pintype "passive"))
      (node (ref "V_BUS") (pin "1") (pinfunction "1_1") (pintype "passive"))
      (node (ref "V_BUS") (pin "3") (pinfunction "3_3") (pintype "passive"))
      (node (ref "V_BUS") (pin "5") (pinfunction "5_5") (pintype "passive"))
      (node (ref "V_BUS") (pin "7") (pinfunction "7_7") (pintype "passive"))
      (node (ref "V_BUS") (pin "9") (pinfunction "9_9") (pintype "passive"))
    )
    (net (code "4") (name "+VFOTO_CELL_+X") (class "Default")
      (node (ref "+X") (pin "1") (pinfunction "1_1") (pintype "passive"))
      (node (ref "Q4") (pin "2") (pinfunction "S_2") (pintype "passive"))
    )
    (net (code "5") (name "+VFOTO_CELL_+Y") (class "Default")
      (node (ref "+Y") (pin "1") (pinfunction "1_1") (pintype "passive"))
      (node (ref "Q6") (pin "2") (pinfunction "S_2") (pintype "passive"))
    )
    (net (code "6") (name "+VFOTO_CELL_-X") (class "Default")
      (node (ref "-X") (pin "1") (pinfunction "1_1") (pintype "passive"))
      (node (ref "Q5") (pin "2") (pinfunction "S_2") (pintype "passive"))
    )
    (net (code "7") (name "+VFOTO_CELL_-Y") (class "Default")
      (node (ref "-Y") (pin "1") (pinfunction "1_1") (pintype "passive"))
      (node (ref "Q7") (pin "2") (pinfunction "S_2") (pintype "passive"))
    )
    (net (code "8") (name "AD_IOUT_3V3") (class "Default")
      (node (ref "IC6") (pin "1") (pinfunction "OUT_1") (pintype "output"))
      (node (ref "IC9") (pin "37") (pinfunction "RE0/AN5/~{RD}_37") (pintype "input"))
      (node (ref "R35") (pin "1") (pinfunction "1_1") (pintype "passive"))
    )
    (net (code "9") (name "AD_IOUT_5V") (class "Default")
      (node (ref "IC5") (pin "1") (pinfunction "OUT_1") (pintype "output"))
      (node (ref "IC9") (pin "32") (pinfunction "RA3/VREF+/AN3_32") (pintype "bidirectional"))
      (node (ref "R29") (pin "1") (pinfunction "1_1") (pintype "passive"))
    )
    (net (code "10") (name "AD_IOUT_12V") (class "Default")
      (node (ref "IC7") (pin "1") (pinfunction "OUT_1") (pintype "output"))
      (node (ref "IC9") (pin "30") (pinfunction "RA1/AN1/C1INC_30") (pintype "bidirectional"))
      (node (ref "R24") (pin "1") (pinfunction "1_1") (pintype "passive"))
    )
    (net (code "11") (name "AD_IOUT_NREGV") (class "Default")
      (node (ref "IC8") (pin "1") (pinfunction "OUT_1") (pintype "output"))
      (node (ref "IC9") (pin "39") (pinfunction "RE2/AN7/C2OUT/~{CS}_39") (pintype "bidirectional"))
      (node (ref "R41") (pin "1") (pinfunction "1_1") (pintype "passive"))
    )
    (net (code "12") (name "AD_IOUT_VCELL") (class "Default")
      (node (ref "IC13") (pin "1") (pinfunction "OUT_1") (pintype "output"))
      (node (ref "IC17") (pin "5") (pinfunction "X5_5") (pintype "bidirectional"))
      (node (ref "R78") (pin "1") (pinfunction "1_1") (pintype "passive"))
    )
    (net (code "13") (name "AD_TEMP_BAT") (class "Default")
      (node (ref "IC10") (pin "2") (pinfunction "VOUT_2") (pintype "bidirectional"))
      (node (ref "IC17") (pin "2") (pinfunction "X6_2") (pintype "bidirectional"))
      (node (ref "SJ7") (pin "1") (pinfunction "1_1") (pintype "passive"))
    )
    (net (code "14") (name "AD_VOUT_3V3") (class "Default")
      (node (ref "IC6") (pin "7") (pinfunction "OUT_7") (pintype "output"))
      (node (ref "IC9") (pin "34") (pinfunction "RA5/AN4/HLVDIN/T1CKI/~{SS}_34") (pintype "bidirectional"))
      (node (ref "R72") (pin "2") (pinfunction "2_2") (pintype "passive"))
    )
    (net (code "15") (name "AD_VOUT_5V") (class "Default")
      (node (ref "IC5") (pin "6") (pinfunction "-IN_6") (pintype "input"))
      (node (ref "IC5") (pin "7") (pinfunction "OUT_7") (pintype "output"))
      (node (ref "IC9") (pin "31") (pinfunction "RA2/VREF-/AN2/C2INC_31") (pintype "bidirectional"))
    )
    (net (code "16") (name "AD_VOUT_12V") (class "Default")
      (node (ref "IC7") (pin "6") (pinfunction "-IN_6") (pintype "input"))
      (node (ref "IC7") (pin "7") (pinfunction "OUT_7") (pintype "output"))
      (node (ref "IC9") (pin "29") (pinfunction "RA0/CVREF/AN0/ULPWU_29") (pintype "bidirectional"))
    )
    (net (code "17") (name "AD_VOUT_NREGV") (class "Default")
      (node (ref "IC8") (pin "6") (pinfunction "-IN_6") (pintype "input"))
      (node (ref "IC8") (pin "7") (pinfunction "OUT_7") (pintype "output"))
      (node (ref "IC9") (pin "38") (pinfunction "RE1/AN6/C1OUT/~{WR}_38") (pintype "bidirectional"))
    )
    (net (code "18") (name "AD_VOUT_VCELL") (class "Default")
      (node (ref "IC13") (pin "6") (pinfunction "-IN_6") (pintype "input"))
      (node (ref "IC13") (pin "7") (pinfunction "OUT_7") (pintype "output"))
      (node (ref "IC17") (pin "1") (pinfunction "X4_1") (pintype "bidirectional"))
    )
    (net (code "19") (name "AUX") (class "Default")
      (node (ref "BACKUP") (pin "24") (pinfunction "24_24") (pintype "passive"))
      (node (ref "BACKUP1") (pin "24") (pinfunction "24_24") (pintype "passive"))
      (node (ref "IC12") (pin "3") (pinfunction "CTL_3") (pintype "passive"))
      (node (ref "IC9") (pin "13") (pinfunction "RB0/AN10/FLT0/INT0_13") (pintype "bidirectional"))
    )
    (net (code "20") (name "AUX_1") (class "Default")
      (node (ref "BACKUP1") (pin "28") (pinfunction "28_28") (pintype "passive"))
      (node (ref "IC17") (pin "11") (pinfunction "A_11") (pintype "input"))
    )
    (net (code "21") (name "AUX_2") (class "Default")
      (node (ref "BACKUP1") (pin "30") (pinfunction "30_30") (pintype "passive"))
      (node (ref "IC17") (pin "10") (pinfunction "B_10") (pintype "input"))
    )
    (net (code "22") (name "AUX_3") (class "Default")
      (node (ref "BACKUP1") (pin "32") (pinfunction "32_32") (pintype "passive"))
      (node (ref "IC17") (pin "9") (pinfunction "C_9") (pintype "input"))
    )
    (net (code "23") (name "AUX_4") (class "Default")
      (node (ref "BACKUP1") (pin "27") (pinfunction "27_27") (pintype "passive"))
      (node (ref "IC16") (pin "3") (pinfunction "CTL_3") (pintype "passive"))
    )
    (net (code "24") (name "AUX_5") (class "Default")
      (node (ref "BACKUP1") (pin "29") (pinfunction "29_29") (pintype "passive"))
    )
    (net (code "25") (name "AUX_6") (class "Default")
      (node (ref "BACKUP") (pin "22") (pinfunction "22_22") (pintype "passive"))
      (node (ref "BACKUP1") (pin "22") (pinfunction "22_22") (pintype "passive"))
      (node (ref "IC14") (pin "3") (pinfunction "CTL_3") (pintype "passive"))
      (node (ref "IC9") (pin "2") (pinfunction "RD4/ECCP1/P1A/PSP4_2") (pintype "bidirectional"))
    )
    (net (code "26") (name "AUX_7") (class "Default")
      (node (ref "BACKUP") (pin "21") (pinfunction "21_21") (pintype "passive"))
      (node (ref "BACKUP1") (pin "21") (pinfunction "21_21") (pintype "passive"))
      (node (ref "IC15") (pin "3") (pinfunction "CTL_3") (pintype "passive"))
      (node (ref "IC9") (pin "1") (pinfunction "RC7/CCP4_1") (pintype "bidirectional"))
    )
    (net (code "27") (name "BOT1") (class "Default")
      (node (ref "DEBUG") (pin "2") (pinfunction "2_2") (pintype "passive"))
      (node (ref "IC9") (pin "54") (pinfunction "RD0/C1INA/PSP0_54") (pintype "bidirectional"))
      (node (ref "R51") (pin "1") (pinfunction "1_1") (pintype "passive"))
    )
    (net (code "28") (name "BOT2") (class "Default")
      (node (ref "DEBUG") (pin "4") (pinfunction "4_4") (pintype "passive"))
      (node (ref "IC9") (pin "55") (pinfunction "RD1/C1INB/PSP1_55") (pintype "bidirectional"))
      (node (ref "R52") (pin "1") (pinfunction "1_1") (pintype "passive"))
    )
    (net (code "29") (name "BOT3") (class "Default")
      (node (ref "DEBUG") (pin "6") (pinfunction "6_6") (pintype "passive"))
      (node (ref "IC9") (pin "58") (pinfunction "RD2/C2INA/PSP2_58") (pintype "bidirectional"))
      (node (ref "R56") (pin "1") (pinfunction "1_1") (pintype "passive"))
    )
    (net (code "30") (name "CANRX") (class "Default")
      (node (ref "IC11") (pin "4") (pinfunction "RXD_4") (pintype "bidirectional"))
      (node (ref "IC9") (pin "16") (pinfunction "RB3/CANRX/CTED2/INT3_16") (pintype "bidirectional"))
    )
    (net (code "31") (name "CANTX") (class "Default")
      (node (ref "IC11") (pin "1") (pinfunction "TXD_1") (pintype "bidirectional"))
      (node (ref "IC9") (pin "15") (pinfunction "RB2/CANTX/CTED1/INT2_15") (pintype "bidirectional"))
    )
    (net (code "32") (name "CTL_3V3") (class "Default")
      (node (ref "IC3") (pin "3") (pinfunction "CTL_3") (pintype "passive"))
      (node (ref "IC9") (pin "18") (pinfunction "RG4/T0CKI_18") (pintype "bidirectional"))
    )
    (net (code "33") (name "CTL_5V") (class "Default")
      (node (ref "IC2") (pin "3") (pinfunction "CTL_3") (pintype "passive"))
      (node (ref "IC9") (pin "19") (pinfunction "RF1_19") (pintype "bidirectional"))
    )
    (net (code "34") (name "CTL_12V") (class "Default")
      (node (ref "IC1") (pin "3") (pinfunction "CTL_3") (pintype "passive"))
      (node (ref "IC9") (pin "20") (pinfunction "RB4/AN9/CTPLS/KBI0_20") (pintype "input"))
    )
    (net (code "35") (name "CTL_NREGV") (class "Default")
      (node (ref "IC4") (pin "3") (pinfunction "CTL_3") (pintype "passive"))
      (node (ref "IC9") (pin "17") (pinfunction "RF0/MDMIN_17") (pintype "bidirectional"))
    )
    (net (code "36") (name "GND") (class "Default")
      (node (ref "+X") (pin "2") (pinfunction "2_2") (pintype "passive"))
      (node (ref "+X") (pin "5") (pinfunction "5_5") (pintype "passive"))
      (node (ref "+Y") (pin "2") (pinfunction "2_2") (pintype "passive"))
      (node (ref "+Y") (pin "5") (pinfunction "5_5") (pintype "passive"))
      (node (ref "-X") (pin "2") (pinfunction "2_2") (pintype "passive"))
      (node (ref "-X") (pin "5") (pinfunction "5_5") (pintype "passive"))
      (node (ref "-Y") (pin "2") (pinfunction "2_2") (pintype "passive"))
      (node (ref "-Y") (pin "5") (pinfunction "5_5") (pintype "passive"))
      (node (ref "BACKUP") (pin "17") (pinfunction "17_17") (pintype "passive"))
      (node (ref "BACKUP") (pin "18") (pinfunction "18_18") (pintype "passive"))
      (node (ref "BACKUP") (pin "19") (pinfunction "19_19") (pintype "passive"))
      (node (ref "BACKUP") (pin "20") (pinfunction "20_20") (pintype "passive"))
      (node (ref "BACKUP1") (pin "17") (pinfunction "17_17") (pintype "passive"))
      (node (ref "BACKUP1") (pin "18") (pinfunction "18_18") (pintype "passive"))
      (node (ref "BACKUP1") (pin "19") (pinfunction "19_19") (pintype "passive"))
      (node (ref "BACKUP1") (pin "20") (pinfunction "20_20") (pintype "passive"))
      (node (ref "BAT") (pin "2") (pinfunction "2_2") (pintype "passive"))
      (node (ref "C1") (pin "2") (pinfunction "2_2") (pintype "passive"))
      (node (ref "C10") (pin "-") (pinfunction "-_-") (pintype "passive"))
      (node (ref "C11") (pin "-") (pinfunction "-_-") (pintype "passive"))
      (node (ref "C12") (pin "-") (pinfunction "-_-") (pintype "passive"))
      (node (ref "C13") (pin "1") (pinfunction "1_1") (pintype "passive"))
      (node (ref "C14") (pin "1") (pinfunction "1_1") (pintype "passive"))
      (node (ref "C15") (pin "1") (pinfunction "1_1") (pintype "passive"))
      (node (ref "C16") (pin "1") (pinfunction "1_1") (pintype "passive"))
      (node (ref "C17") (pin "1") (pinfunction "1_1") (pintype "passive"))
      (node (ref "C18") (pin "1") (pinfunction "1_1") (pintype "passive"))
      (node (ref "C19") (pin "1") (pinfunction "1_1") (pintype "passive"))
      (node (ref "C2") (pin "2") (pinfunction "2_2") (pintype "passive"))
      (node (ref "C20") (pin "1") (pinfunction "1_1") (pintype "passive"))
      (node (ref "C21") (pin "1") (pinfunction "1_1") (pintype "passive"))
      (node (ref "C22") (pin "-") (pinfunction "-_-") (pintype "passive"))
      (node (ref "C23") (pin "1") (pinfunction "1_1") (pintype "passive"))
      (node (ref "C24") (pin "1") (pinfunction "1_1") (pintype "passive"))
      (node (ref "C25") (pin "1") (pinfunction "1_1") (pintype "passive"))
      (node (ref "C26") (pin "1") (pinfunction "1_1") (pintype "passive"))
      (node (ref "C27") (pin "1") (pinfunction "1_1") (pintype "passive"))
      (node (ref "C29") (pin "-") (pinfunction "-_-") (pintype "passive"))
      (node (ref "C30") (pin "-") (pinfunction "-_-") (pintype "passive"))
      (node (ref "C31") (pin "2") (pinfunction "2_2") (pintype "passive"))
      (node (ref "C32") (pin "2") (pinfunction "2_2") (pintype "passive"))
      (node (ref "C33") (pin "1") (pinfunction "1_1") (pintype "passive"))
      (node (ref "C34") (pin "1") (pinfunction "1_1") (pintype "passive"))
      (node (ref "C35") (pin "1") (pinfunction "1_1") (pintype "passive"))
      (node (ref "C36") (pin "1") (pinfunction "1_1") (pintype "passive"))
      (node (ref "C37") (pin "1") (pinfunction "1_1") (pintype "passive"))
      (node (ref "C38") (pin "1") (pinfunction "1_1") (pintype "passive"))
      (node (ref "C39") (pin "2") (pinfunction "2_2") (pintype "passive"))
      (node (ref "C4") (pin "2") (pinfunction "2_2") (pintype "passive"))
      (node (ref "C41") (pin "2") (pinfunction "2_2") (pintype "passive"))
      (node (ref "C42") (pin "2") (pinfunction "2_2") (pintype "passive"))
      (node (ref "C43") (pin "2") (pinfunction "2_2") (pintype "passive"))
      (node (ref "C47") (pin "-") (pinfunction "-_-") (pintype "passive"))
      (node (ref "C48") (pin "-") (pinfunction "-_-") (pintype "passive"))
      (node (ref "C49") (pin "2") (pinfunction "2_2") (pintype "passive"))
      (node (ref "C5") (pin "-") (pinfunction "-_-") (pintype "passive"))
      (node (ref "C50") (pin "2") (pinfunction "2_2") (pintype "passive"))
      (node (ref "C52") (pin "-") (pinfunction "-_-") (pintype "passive"))
      (node (ref "C53") (pin "2") (pinfunction "2_2") (pintype "passive"))
      (node (ref "C54") (pin "-") (pinfunction "-_-") (pintype "passive"))
      (node (ref "C55") (pin "2") (pinfunction "2_2") (pintype "passive"))
      (node (ref "C56") (pin "-") (pinfunction "-_-") (pintype "passive"))
      (node (ref "C57") (pin "-") (pinfunction "-_-") (pintype "passive"))
      (node (ref "C58") (pin "2") (pinfunction "2_2") (pintype "passive"))
      (node (ref "C59") (pin "1") (pinfunction "1_1") (pintype "passive"))
      (node (ref "C60") (pin "1") (pinfunction "1_1") (pintype "passive"))
      (node (ref "C61") (pin "1") (pinfunction "1_1") (pintype "passive"))
      (node (ref "C62") (pin "1") (pinfunction "1_1") (pintype "passive"))
      (node (ref "C63") (pin "1") (pinfunction "1_1") (pintype "passive"))
      (node (ref "C64") (pin "1") (pinfunction "1_1") (pintype "passive"))
      (node (ref "C65") (pin "2") (pinfunction "2_2") (pintype "passive"))
      (node (ref "C66") (pin "2") (pinfunction "2_2") (pintype "passive"))
      (node (ref "C67") (pin "2") (pinfunction "2_2") (pintype "passive"))
      (node (ref "C68") (pin "2") (pinfunction "2_2") (pintype "passive"))
      (node (ref "C69") (pin "2") (pinfunction "2_2") (pintype "passive"))
      (node (ref "C7") (pin "-") (pinfunction "-_-") (pintype "passive"))
      (node (ref "C70") (pin "1") (pinfunction "1_1") (pintype "passive"))
      (node (ref "C71") (pin "1") (pinfunction "1_1") (pintype "passive"))
      (node (ref "C72") (pin "1") (pinfunction "1_1") (pintype "passive"))
      (node (ref "C73") (pin "1") (pinfunction "1_1") (pintype "passive"))
      (node (ref "C74") (pin "1") (pinfunction "1_1") (pintype "passive"))
      (node (ref "C75") (pin "1") (pinfunction "1_1") (pintype "passive"))
      (node (ref "C76") (pin "1") (pinfunction "1_1") (pintype "passive"))
      (node (ref "C77") (pin "1") (pinfunction "1_1") (pintype "passive"))
      (node (ref "C78") (pin "1") (pinfunction "1_1") (pintype "passive"))
      (node (ref "C79") (pin "1") (pinfunction "1_1") (pintype "passive"))
      (node (ref "C80") (pin "1") (pinfunction "1_1") (pintype "passive"))
      (node (ref "C81") (pin "1") (pinfunction "1_1") (pintype "passive"))
      (node (ref "C9") (pin "-") (pinfunction "-_-") (pintype "passive"))
      (node (ref "CAN") (pin "4") (pinfunction "4_4") (pintype "bidirectional"))
      (node (ref "D2") (pin "A") (pinfunction "A_A") (pintype "passive"))
      (node (ref "D5") (pin "A") (pinfunction "A_A") (pintype "passive"))
      (node (ref "DEBUG") (pin "1") (pinfunction "1_1") (pintype "passive"))
      (node (ref "DEBUG") (pin "3") (pinfunction "3_3") (pintype "passive"))
      (node (ref "DEBUG") (pin "5") (pinfunction "5_5") (pintype "passive"))
      (node (ref "FOTOCELULA") (pin "2") (pinfunction "2_2") (pintype "passive"))
      (node (ref "IC1") (pin "2") (pinfunction "GND_2") (pintype "power_in"))
      (node (ref "IC10") (pin "3") (pinfunction "GND_3") (pintype "bidirectional"))
      (node (ref "IC11") (pin "2") (pinfunction "VSS_2") (pintype "power_in"))
      (node (ref "IC12") (pin "2") (pinfunction "GND_2") (pintype "power_in"))
      (node (ref "IC12") (pin "6") (pinfunction "SENSE_6") (pintype "passive"))
      (node (ref "IC13") (pin "4") (pinfunction "V-_4") (pintype "power_in"))
      (node (ref "IC14") (pin "2") (pinfunction "GND_2") (pintype "power_in"))
      (node (ref "IC14") (pin "6") (pinfunction "SENSE_6") (pintype "passive"))
      (node (ref "IC15") (pin "2") (pinfunction "GND_2") (pintype "power_in"))
      (node (ref "IC15") (pin "6") (pinfunction "SENSE_6") (pintype "passive"))
      (node (ref "IC16") (pin "2") (pinfunction "GND_2") (pintype "power_in"))
      (node (ref "IC16") (pin "6") (pinfunction "SENSE_6") (pintype "passive"))
      (node (ref "IC17") (pin "6") (pinfunction "INH_6") (pintype "input"))
      (node (ref "IC17") (pin "7") (pinfunction "VEE_7") (pintype "power_in"))
      (node (ref "IC17") (pin "8") (pinfunction "GND_8") (pintype "power_in"))
      (node (ref "IC18") (pin "3") (pinfunction "GND_3") (pintype "bidirectional"))
      (node (ref "IC2") (pin "2") (pinfunction "GND_2") (pintype "power_in"))
      (node (ref "IC3") (pin "2") (pinfunction "GND_2") (pintype "power_in"))
      (node (ref "IC4") (pin "2") (pinfunction "GND_2") (pintype "power_in"))
      (node (ref "IC4") (pin "6") (pinfunction "SENSE_6") (pintype "passive"))
      (node (ref "IC5") (pin "4") (pinfunction "V-_4") (pintype "power_in"))
      (node (ref "IC6") (pin "4") (pinfunction "V-_4") (pintype "power_in"))
      (node (ref "IC7") (pin "4") (pinfunction "V-_4") (pintype "power_in"))
      (node (ref "IC8") (pin "4") (pinfunction "V-_4") (pintype "power_in"))
      (node (ref "IC9") (pin "26") (pinfunction "VSS_26") (pintype "power_in"))
      (node (ref "IC9") (pin "42") (pinfunction "AVSS_42") (pintype "power_in"))
      (node (ref "IC9") (pin "43") (pinfunction "VSS_43") (pintype "power_in"))
      (node (ref "IC9") (pin "56") (pinfunction "VSS_56") (pintype "power_in"))
      (node (ref "IC9") (pin "8") (pinfunction "VSS_8") (pintype "power_in"))
      (node (ref "ICSP") (pin "3") (pinfunction "GND_3") (pintype "passive"))
      (node (ref "R1") (pin "1") (pinfunction "1_1") (pintype "passive"))
      (node (ref "R10") (pin "1") (pinfunction "1_1") (pintype "passive"))
      (node (ref "R11") (pin "1") (pinfunction "1_1") (pintype "passive"))
      (node (ref "R2") (pin "1") (pinfunction "1_1") (pintype "passive"))
      (node (ref "R26") (pin "2") (pinfunction "2_2") (pintype "passive"))
      (node (ref "R31") (pin "2") (pinfunction "2_2") (pintype "passive"))
      (node (ref "R37") (pin "2") (pinfunction "2_2") (pintype "passive"))
      (node (ref "R4") (pin "1") (pinfunction "1_1") (pintype "passive"))
      (node (ref "R43") (pin "2") (pinfunction "2_2") (pintype "passive"))
      (node (ref "R46") (pin "2") (pinfunction "2_2") (pintype "passive"))
      (node (ref "R5") (pin "1") (pinfunction "1_1") (pintype "passive"))
      (node (ref "R58") (pin "1") (pinfunction "1_1") (pintype "passive"))
      (node (ref "R60") (pin "1") (pinfunction "1_1") (pintype "passive"))
      (node (ref "R61") (pin "1") (pinfunction "1_1") (pintype "passive"))
      (node (ref "R62") (pin "1") (pinfunction "1_1") (pintype "passive"))
      (node (ref "R63") (pin "1") (pinfunction "1_1") (pintype "passive"))
      (node (ref "R66") (pin "2") (pinfunction "2_2") (pintype "passive"))
      (node (ref "R68") (pin "2") (pinfunction "2_2") (pintype "passive"))
      (node (ref "R70") (pin "2") (pinfunction "2_2") (pintype "passive"))
      (node (ref "R71") (pin "2") (pinfunction "2_2") (pintype "passive"))
      (node (ref "R73") (pin "1") (pinfunction "1_1") (pintype "passive"))
      (node (ref "R77") (pin "2") (pinfunction "2_2") (pintype "passive"))
      (node (ref "R8") (pin "1") (pinfunction "1_1") (pintype "passive"))
      (node (ref "R80") (pin "2") (pinfunction "2_2") (pintype "passive"))
      (node (ref "R81") (pin "2") (pinfunction "2_2") (pintype "passive"))
      (node (ref "R83") (pin "2") (pinfunction "2_2") (pintype "passive"))
      (node (ref "S12") (pin "N") (pinfunction "N_N") (pintype "power_in"))
      (node (ref "S16") (pin "N") (pinfunction "N_N") (pintype "power_in"))
      (node (ref "S20") (pin "N") (pinfunction "N_N") (pintype "power_in"))
      (node (ref "S24") (pin "N") (pinfunction "N_N") (pintype "power_in"))
      (node (ref "S4") (pin "N") (pinfunction "N_N") (pintype "power_in"))
      (node (ref "S8") (pin "N") (pinfunction "N_N") (pintype "power_in"))
      (node (ref "SERIAL") (pin "4") (pinfunction "4_4") (pintype "bidirectional"))
      (node (ref "SJ1") (pin "1") (pinfunction "1_1") (pintype "passive"))
      (node (ref "SJ2") (pin "1") (pinfunction "1_1") (pintype "passive"))
      (node (ref "SJ6") (pin "1") (pinfunction "1_1") (pintype "passive"))
      (node (ref "U1") (pin "1") (pinfunction "GND_1") (pintype "power_in"))
      (node (ref "U2") (pin "1") (pinfunction "GND_1") (pintype "power_in"))
      (node (ref "U3") (pin "10") (pinfunction "GND/HEATSINK_10") (pintype "power_in"))
      (node (ref "U3") (pin "16") (pinfunction "AGND_16") (pintype "power_in"))
      (node (ref "U3") (pin "21") (pinfunction "EPAD_21") (pintype "power_in"))
      (node (ref "U4") (pin "1") (pinfunction "GND_1") (pintype "power_in"))
      (node (ref "U5") (pin "26") (pinfunction "PGND_26") (pintype "passive"))
      (node (ref "U5") (pin "29") (pinfunction "EP_29") (pintype "passive"))
      (node (ref "U6") (pin "4") (pinfunction "AGND_4") (pintype "passive"))
      (node (ref "U6") (pin "5") (pinfunction "PGND_5") (pintype "passive"))
      (node (ref "V_BUS") (pin "10") (pinfunction "10_10") (pintype "passive"))
      (node (ref "V_BUS") (pin "12") (pinfunction "12_12") (pintype "passive"))
      (node (ref "V_BUS") (pin "14") (pinfunction "14_14") (pintype "passive"))
      (node (ref "V_BUS") (pin "16") (pinfunction "16_16") (pintype "passive"))
      (node (ref "V_BUS") (pin "18") (pinfunction "18_18") (pintype "passive"))
      (node (ref "V_BUS") (pin "2") (pinfunction "2_2") (pintype "passive"))
      (node (ref "V_BUS") (pin "20") (pinfunction "20_20") (pintype "passive"))
      (node (ref "V_BUS") (pin "22") (pinfunction "22_22") (pintype "passive"))
      (node (ref "V_BUS") (pin "24") (pinfunction "24_24") (pintype "passive"))
      (node (ref "V_BUS") (pin "26") (pinfunction "26_26") (pintype "passive"))
      (node (ref "V_BUS") (pin "28") (pinfunction "28_28") (pintype "passive"))
      (node (ref "V_BUS") (pin "30") (pinfunction "30_30") (pintype "passive"))
      (node (ref "V_BUS") (pin "32") (pinfunction "32_32") (pintype "passive"))
      (node (ref "V_BUS") (pin "34") (pinfunction "34_34") (pintype "passive"))
      (node (ref "V_BUS") (pin "36") (pinfunction "36_36") (pintype "passive"))
      (node (ref "V_BUS") (pin "38") (pinfunction "38_38") (pintype "passive"))
      (node (ref "V_BUS") (pin "4") (pinfunction "4_4") (pintype "passive"))
      (node (ref "V_BUS") (pin "40") (pinfunction "40_40") (pintype "passive"))
      (node (ref "V_BUS") (pin "6") (pinfunction "6_6") (pintype "passive"))
      (node (ref "V_BUS") (pin "8") (pinfunction "8_8") (pintype "passive"))
      (node (ref "X1") (pin "3") (pinfunction "3_3") (pintype "passive"))
      (node (ref "X1") (pin "4") (pinfunction "4_4") (pintype "passive"))
      (node (ref "X1") (pin "7") (pinfunction "7_7") (pintype "passive"))
      (node (ref "X1") (pin "8") (pinfunction "8_8") (pintype "passive"))
    )
    (net (code "37") (name "LED1") (class "Default")
      (node (ref "IC9") (pin "49") (pinfunction "RC1/SOSCI_49") (pintype "bidirectional"))
      (node (ref "LED3") (pin "C") (pinfunction "C_C") (pintype "passive"))
    )
    (net (code "38") (name "LED2") (class "Default")
      (node (ref "IC9") (pin "50") (pinfunction "RC2/T1G/CCP2_50") (pintype "bidirectional"))
      (node (ref "LED2") (pin "C") (pinfunction "C_C") (pintype "passive"))
    )
    (net (code "39") (name "LED3") (class "Default")
      (node (ref "IC9") (pin "51") (pinfunction "RC3/REFO/SCL/SCK_51") (pintype "bidirectional"))
      (node (ref "LED1") (pin "C") (pinfunction "C_C") (pintype "passive"))
    )
    (net (code "40") (name "MUX_AD") (class "Default")
      (node (ref "BACKUP") (pin "23") (pinfunction "23_23") (pintype "passive"))
      (node (ref "BACKUP1") (pin "23") (pinfunction "23_23") (pintype "passive"))
      (node (ref "IC17") (pin "3") (pinfunction "X_3") (pintype "bidirectional"))
      (node (ref "IC9") (pin "14") (pinfunction "RB1/AN8/CTDIN/INT1_14") (pintype "bidirectional"))
    )
    (net (code "41") (name "Net-(C3-Pad2)") (class "Default")
      (node (ref "C3") (pin "2") (pinfunction "2_2") (pintype "passive"))
      (node (ref "R1") (pin "2") (pinfunction "2_2") (pintype "passive"))
    )
    (net (code "42") (name "Net-(C4-Pad1)") (class "Default")
      (node (ref "C4") (pin "1") (pinfunction "1_1") (pintype "passive"))
      (node (ref "R3") (pin "1") (pinfunction "1_1") (pintype "passive"))
    )
    (net (code "43") (name "Net-(C25-Pad2)") (class "Default")
      (node (ref "C25") (pin "2") (pinfunction "2_2") (pintype "passive"))
      (node (ref "R47") (pin "1") (pinfunction "1_1") (pintype "passive"))
      (node (ref "R53") (pin "2") (pinfunction "2_2") (pintype "passive"))
    )
    (net (code "44") (name "Net-(C40-Pad1)") (class "Default")
      (node (ref "C40") (pin "1") (pinfunction "1_1") (pintype "passive"))
      (node (ref "R60") (pin "2") (pinfunction "2_2") (pintype "passive"))
    )
    (net (code "45") (name "Net-(C44-Pad1)") (class "Default")
      (node (ref "C44") (pin "1") (pinfunction "1_1") (pintype "passive"))
      (node (ref "R61") (pin "2") (pinfunction "2_2") (pintype "passive"))
    )
    (net (code "46") (name "Net-(C45-Pad1)") (class "Default")
      (node (ref "C45") (pin "1") (pinfunction "1_1") (pintype "passive"))
      (node (ref "R62") (pin "2") (pinfunction "2_2") (pintype "passive"))
    )
    (net (code "47") (name "Net-(D8-PadA)") (class "Default")
      (node (ref "D8") (pin "A") (pinfunction "A_A") (pintype "passive"))
      (node (ref "S1") (pin "P") (pinfunction "P_P") (pintype "power_in"))
    )
    (net (code "48") (name "Net-(D9-PadA)") (class "Default")
      (node (ref "D9") (pin "A") (pinfunction "A_A") (pintype "passive"))
      (node (ref "S5") (pin "P") (pinfunction "P_P") (pintype "power_in"))
    )
    (net (code "49") (name "Net-(D10-PadA)") (class "Default")
      (node (ref "D10") (pin "A") (pinfunction "A_A") (pintype "passive"))
      (node (ref "S9") (pin "P") (pinfunction "P_P") (pintype "power_in"))
    )
    (net (code "50") (name "Net-(D11-PadA)") (class "Default")
      (node (ref "D11") (pin "A") (pinfunction "A_A") (pintype "passive"))
      (node (ref "S13") (pin "P") (pinfunction "P_P") (pintype "power_in"))
    )
    (net (code "51") (name "Net-(D12-PadA)") (class "Default")
      (node (ref "D12") (pin "A") (pinfunction "A_A") (pintype "passive"))
      (node (ref "S17") (pin "P") (pinfunction "P_P") (pintype "power_in"))
    )
    (net (code "52") (name "Net-(D13-PadA)") (class "Default")
      (node (ref "D13") (pin "A") (pinfunction "A_A") (pintype "passive"))
      (node (ref "S21") (pin "P") (pinfunction "P_P") (pintype "power_in"))
    )
    (net (code "53") (name "Net-(IC1-GATE)") (class "Default")
      (node (ref "IC1") (pin "5") (pinfunction "GATE_5") (pintype "passive"))
      (node (ref "R12") (pin "2") (pinfunction "2_2") (pintype "passive"))
      (node (ref "T1") (pin "4") (pinfunction "G_4") (pintype "passive"))
      (node (ref "T2") (pin "2") (pinfunction "G_2") (pintype "passive"))
    )
    (net (code "54") (name "Net-(IC1-STAT)") (class "Default")
      (node (ref "IC1") (pin "4") (pinfunction "STAT_4") (pintype "passive"))
      (node (ref "R13") (pin "2") (pinfunction "2_2") (pintype "passive"))
      (node (ref "T1") (pin "2") (pinfunction "G_2") (pintype "passive"))
      (node (ref "T2") (pin "4") (pinfunction "G_4") (pintype "passive"))
    )
    (net (code "55") (name "Net-(IC2-GATE)") (class "Default")
      (node (ref "IC2") (pin "5") (pinfunction "GATE_5") (pintype "passive"))
      (node (ref "R30") (pin "2") (pinfunction "2_2") (pintype "passive"))
      (node (ref "T3") (pin "4") (pinfunction "G_4") (pintype "passive"))
      (node (ref "T4") (pin "2") (pinfunction "G_2") (pintype "passive"))
    )
    (net (code "56") (name "Net-(IC2-STAT)") (class "Default")
      (node (ref "IC2") (pin "4") (pinfunction "STAT_4") (pintype "passive"))
      (node (ref "R16") (pin "2") (pinfunction "2_2") (pintype "passive"))
      (node (ref "T3") (pin "2") (pinfunction "G_2") (pintype "passive"))
      (node (ref "T4") (pin "4") (pinfunction "G_4") (pintype "passive"))
    )
    (net (code "57") (name "Net-(IC3-GATE)") (class "Default")
      (node (ref "IC3") (pin "5") (pinfunction "GATE_5") (pintype "passive"))
      (node (ref "R76") (pin "2") (pinfunction "2_2") (pintype "passive"))
      (node (ref "T5") (pin "4") (pinfunction "G_4") (pintype "passive"))
      (node (ref "T6") (pin "2") (pinfunction "G_2") (pintype "passive"))
    )
    (net (code "58") (name "Net-(IC3-STAT)") (class "Default")
      (node (ref "IC3") (pin "4") (pinfunction "STAT_4") (pintype "passive"))
      (node (ref "R19") (pin "2") (pinfunction "2_2") (pintype "passive"))
      (node (ref "T5") (pin "2") (pinfunction "G_2") (pintype "passive"))
      (node (ref "T6") (pin "4") (pinfunction "G_4") (pintype "passive"))
    )
    (net (code "59") (name "Net-(IC4-GATE)") (class "Default")
      (node (ref "IC4") (pin "5") (pinfunction "GATE_5") (pintype "passive"))
      (node (ref "Q2") (pin "1") (pinfunction "G_1") (pintype "passive"))
    )
    (net (code "60") (name "Net-(IC5A-+IN)") (class "Default")
      (node (ref "IC5") (pin "3") (pinfunction "+IN_3") (pintype "input"))
      (node (ref "R21") (pin "1") (pinfunction "1_1") (pintype "passive"))
      (node (ref "R26") (pin "1") (pinfunction "1_1") (pintype "passive"))
    )
    (net (code "61") (name "Net-(IC5A--IN)") (class "Default")
      (node (ref "IC5") (pin "2") (pinfunction "-IN_2") (pintype "input"))
      (node (ref "R28") (pin "1") (pinfunction "1_1") (pintype "passive"))
      (node (ref "R29") (pin "2") (pinfunction "2_2") (pintype "passive"))
    )
    (net (code "62") (name "Net-(IC5B-+IN)") (class "Default")
      (node (ref "IC5") (pin "5") (pinfunction "+IN_5") (pintype "input"))
      (node (ref "R20") (pin "2") (pinfunction "2_2") (pintype "passive"))
      (node (ref "R31") (pin "1") (pinfunction "1_1") (pintype "passive"))
    )
    (net (code "63") (name "Net-(IC6A-+IN)") (class "Default")
      (node (ref "IC6") (pin "3") (pinfunction "+IN_3") (pintype "input"))
      (node (ref "R33") (pin "1") (pinfunction "1_1") (pintype "passive"))
      (node (ref "R71") (pin "1") (pinfunction "1_1") (pintype "passive"))
    )
    (net (code "64") (name "Net-(IC6A--IN)") (class "Default")
      (node (ref "IC6") (pin "2") (pinfunction "-IN_2") (pintype "input"))
      (node (ref "R34") (pin "1") (pinfunction "1_1") (pintype "passive"))
      (node (ref "R35") (pin "2") (pinfunction "2_2") (pintype "passive"))
    )
    (net (code "65") (name "Net-(IC6B-+IN)") (class "Default")
      (node (ref "IC6") (pin "5") (pinfunction "+IN_5") (pintype "input"))
      (node (ref "R75") (pin "2") (pinfunction "2_2") (pintype "passive"))
    )
    (net (code "66") (name "Net-(IC6B--IN)") (class "Default")
      (node (ref "IC6") (pin "6") (pinfunction "-IN_6") (pintype "input"))
      (node (ref "R72") (pin "1") (pinfunction "1_1") (pintype "passive"))
      (node (ref "R73") (pin "2") (pinfunction "2_2") (pintype "passive"))
    )
    (net (code "67") (name "Net-(IC7A-+IN)") (class "Default")
      (node (ref "IC7") (pin "3") (pinfunction "+IN_3") (pintype "input"))
      (node (ref "R11") (pin "2") (pinfunction "2_2") (pintype "passive"))
      (node (ref "R22") (pin "1") (pinfunction "1_1") (pintype "passive"))
    )
    (net (code "68") (name "Net-(IC7A--IN)") (class "Default")
      (node (ref "IC7") (pin "2") (pinfunction "-IN_2") (pintype "input"))
      (node (ref "R23") (pin "1") (pinfunction "1_1") (pintype "passive"))
      (node (ref "R24") (pin "2") (pinfunction "2_2") (pintype "passive"))
    )
    (net (code "69") (name "Net-(IC7B-+IN)") (class "Default")
      (node (ref "IC7") (pin "5") (pinfunction "+IN_5") (pintype "input"))
      (node (ref "R25") (pin "2") (pinfunction "2_2") (pintype "passive"))
      (node (ref "R46") (pin "1") (pinfunction "1_1") (pintype "passive"))
    )
    (net (code "70") (name "Net-(IC8A-+IN)") (class "Default")
      (node (ref "IC8") (pin "3") (pinfunction "+IN_3") (pintype "input"))
      (node (ref "R39") (pin "1") (pinfunction "1_1") (pintype "passive"))
      (node (ref "R77") (pin "1") (pinfunction "1_1") (pintype "passive"))
    )
    (net (code "71") (name "Net-(IC8A--IN)") (class "Default")
      (node (ref "IC8") (pin "2") (pinfunction "-IN_2") (pintype "input"))
      (node (ref "R40") (pin "1") (pinfunction "1_1") (pintype "passive"))
      (node (ref "R41") (pin "2") (pinfunction "2_2") (pintype "passive"))
    )
    (net (code "72") (name "Net-(IC8B-+IN)") (class "Default")
      (node (ref "IC8") (pin "5") (pinfunction "+IN_5") (pintype "input"))
      (node (ref "R42") (pin "2") (pinfunction "2_2") (pintype "passive"))
      (node (ref "R43") (pin "1") (pinfunction "1_1") (pintype "passive"))
    )
    (net (code "73") (name "Net-(IC9-VDDCORE{slash}VCAP)") (class "Default")
      (node (ref "C26") (pin "2") (pinfunction "2_2") (pintype "passive"))
      (node (ref "IC9") (pin "33") (pinfunction "VDDCORE/VCAP_33") (pintype "bidirectional"))
    )
    (net (code "74") (name "Net-(IC11-CANH)") (class "Default")
      (node (ref "CAN") (pin "2") (pinfunction "2_2") (pintype "bidirectional"))
      (node (ref "IC11") (pin "7") (pinfunction "CANH_7") (pintype "input"))
      (node (ref "R64") (pin "2") (pinfunction "2_2") (pintype "passive"))
    )
    (net (code "75") (name "Net-(IC11-CANL)") (class "Default")
      (node (ref "CAN") (pin "3") (pinfunction "3_3") (pintype "bidirectional"))
      (node (ref "IC11") (pin "6") (pinfunction "CANL_6") (pintype "input"))
      (node (ref "JP2") (pin "1") (pinfunction "1_1") (pintype "passive"))
    )
    (net (code "76") (name "Net-(IC11-RS)") (class "Default")
      (node (ref "IC11") (pin "8") (pinfunction "RS_8") (pintype "input"))
      (node (ref "R63") (pin "2") (pinfunction "2_2") (pintype "passive"))
    )
    (net (code "77") (name "Net-(IC12-GATE)") (class "Default")
      (node (ref "IC12") (pin "5") (pinfunction "GATE_5") (pintype "passive"))
      (node (ref "Q4") (pin "1") (pinfunction "G_1") (pintype "passive"))
    )
    (net (code "78") (name "Net-(IC13A-+IN)") (class "Default")
      (node (ref "IC13") (pin "3") (pinfunction "+IN_3") (pintype "input"))
      (node (ref "R54") (pin "1") (pinfunction "1_1") (pintype "passive"))
      (node (ref "R81") (pin "1") (pinfunction "1_1") (pintype "passive"))
    )
    (net (code "79") (name "Net-(IC13A--IN)") (class "Default")
      (node (ref "IC13") (pin "2") (pinfunction "-IN_2") (pintype "input"))
      (node (ref "R55") (pin "1") (pinfunction "1_1") (pintype "passive"))
      (node (ref "R78") (pin "2") (pinfunction "2_2") (pintype "passive"))
    )
    (net (code "80") (name "Net-(IC13B-+IN)") (class "Default")
      (node (ref "IC13") (pin "5") (pinfunction "+IN_5") (pintype "input"))
      (node (ref "R79") (pin "2") (pinfunction "2_2") (pintype "passive"))
      (node (ref "R80") (pin "1") (pinfunction "1_1") (pintype "passive"))
    )
    (net (code "81") (name "Net-(IC14-GATE)") (class "Default")
      (node (ref "IC14") (pin "5") (pinfunction "GATE_5") (pintype "passive"))
      (node (ref "Q5") (pin "1") (pinfunction "G_1") (pintype "passive"))
    )
    (net (code "82") (name "Net-(IC15-GATE)") (class "Default")
      (node (ref "IC15") (pin "5") (pinfunction "GATE_5") (pintype "passive"))
      (node (ref "Q6") (pin "1") (pinfunction "G_1") (pintype "passive"))
    )
    (net (code "83") (name "Net-(IC16-GATE)") (class "Default")
      (node (ref "IC16") (pin "5") (pinfunction "GATE_5") (pintype "passive"))
      (node (ref "Q7") (pin "1") (pinfunction "G_1") (pintype "passive"))
    )
    (net (code "84") (name "Net-(IC17A-X7)") (class "Default")
      (node (ref "IC17") (pin "4") (pinfunction "X7_4") (pintype "bidirectional"))
      (node (ref "SJ6") (pin "2") (pinfunction "2_2") (pintype "passive"))
    )
    (net (code "85") (name "Net-(IC18-VOUT)") (class "Default")
      (node (ref "IC18") (pin "2") (pinfunction "VOUT_2") (pintype "bidirectional"))
      (node (ref "X1") (pin "6") (pinfunction "6_6") (pintype "passive"))
    )
    (net (code "86") (name "Net-(JP2-Pad2)") (class "Default")
      (node (ref "JP2") (pin "2") (pinfunction "2_2") (pintype "passive"))
      (node (ref "R64") (pin "1") (pinfunction "1_1") (pintype "passive"))
    )
    (net (code "87") (name "Net-(LED1-PadA)") (class "Default")
      (node (ref "LED1") (pin "A") (pinfunction "A_A") (pintype "passive"))
      (node (ref "R48") (pin "2") (pinfunction "2_2") (pintype "passive"))
    )
    (net (code "88") (name "Net-(LED2-PadA)") (class "Default")
      (node (ref "LED2") (pin "A") (pinfunction "A_A") (pintype "passive"))
      (node (ref "R49") (pin "2") (pinfunction "2_2") (pintype "passive"))
    )
    (net (code "89") (name "Net-(LED3-PadA)") (class "Default")
      (node (ref "LED3") (pin "A") (pinfunction "A_A") (pintype "passive"))
      (node (ref "R50") (pin "2") (pinfunction "2_2") (pintype "passive"))
    )
    (net (code "90") (name "Net-(LED4-PadA)") (class "Default")
      (node (ref "LED4") (pin "A") (pinfunction "A_A") (pintype "passive"))
      (node (ref "R85") (pin "2") (pinfunction "2_2") (pintype "passive"))
    )
    (net (code "91") (name "Net-(LED5-PadA)") (class "Default")
      (node (ref "LED5") (pin "A") (pinfunction "A_A") (pintype "passive"))
      (node (ref "R86") (pin "2") (pinfunction "2_2") (pintype "passive"))
    )
    (net (code "92") (name "Net-(Q1-DRAIN)") (class "Default")
      (node (ref "D6") (pin "A") (pinfunction "A_A") (pintype "passive"))
      (node (ref "L1") (pin "2") (pinfunction "2_2") (pintype "passive"))
      (node (ref "Q1") (pin "5") (pinfunction "DRAIN_5") (pintype "passive"))
    )
    (net (code "93") (name "Net-(Q1-GATE)") (class "Default")
      (node (ref "Q1") (pin "4") (pinfunction "GATE_4") (pintype "passive"))
      (node (ref "U6") (pin "6") (pinfunction "DR_6") (pintype "passive"))
    )
    (net (code "94") (name "Net-(Q1-SOURCE)") (class "Default")
      (node (ref "Q1") (pin "1") (pinfunction "SOURCE_1") (pintype "passive"))
      (node (ref "R4") (pin "2") (pinfunction "2_2") (pintype "passive"))
    )
    (net (code "95") (name "Net-(Q4-D)") (class "Default")
      (node (ref "C73") (pin "2") (pinfunction "2_2") (pintype "passive"))
      (node (ref "C76") (pin "2") (pinfunction "2_2") (pintype "passive"))
      (node (ref "C78") (pin "2") (pinfunction "2_2") (pintype "passive"))
      (node (ref "C80") (pin "2") (pinfunction "2_2") (pintype "passive"))
      (node (ref "Q4") (pin "3") (pinfunction "D_3") (pintype "passive"))
      (node (ref "Q5") (pin "3") (pinfunction "D_3") (pintype "passive"))
      (node (ref "Q6") (pin "3") (pinfunction "D_3") (pintype "passive"))
      (node (ref "Q7") (pin "3") (pinfunction "D_3") (pintype "passive"))
      (node (ref "R54") (pin "2") (pinfunction "2_2") (pintype "passive"))
      (node (ref "R82") (pin "1") (pinfunction "1_1") (pintype "passive"))
    )
    (net (code "96") (name "Net-(R36-Pad2)") (class "Default")
      (node (ref "R36") (pin "2") (pinfunction "2_2") (pintype "passive"))
      (node (ref "R37") (pin "1") (pinfunction "1_1") (pintype "passive"))
      (node (ref "R74") (pin "1") (pinfunction "1_1") (pintype "passive"))
    )
    (net (code "97") (name "Net-(R74-Pad2)") (class "Default")
      (node (ref "R74") (pin "2") (pinfunction "2_2") (pintype "passive"))
      (node (ref "R75") (pin "1") (pinfunction "1_1") (pintype "passive"))
    )
    (net (code "98") (name "Net-(S1-PadN)") (class "Default")
      (node (ref "S1") (pin "N") (pinfunction "N_N") (pintype "power_in"))
      (node (ref "S2") (pin "P") (pinfunction "P_P") (pintype "power_in"))
    )
    (net (code "99") (name "Net-(S2-PadN)") (class "Default")
      (node (ref "S2") (pin "N") (pinfunction "N_N") (pintype "power_in"))
      (node (ref "S3") (pin "P") (pinfunction "P_P") (pintype "power_in"))
    )
    (net (code "100") (name "Net-(S3-PadN)") (class "Default")
      (node (ref "S3") (pin "N") (pinfunction "N_N") (pintype "power_in"))
      (node (ref "S4") (pin "P") (pinfunction "P_P") (pintype "power_in"))
    )
    (net (code "101") (name "Net-(S5-PadN)") (class "Default")
      (node (ref "S5") (pin "N") (pinfunction "N_N") (pintype "power_in"))
      (node (ref "S6") (pin "P") (pinfunction "P_P") (pintype "power_in"))
    )
    (net (code "102") (name "Net-(S6-PadN)") (class "Default")
      (node (ref "S6") (pin "N") (pinfunction "N_N") (pintype "power_in"))
      (node (ref "S7") (pin "P") (pinfunction "P_P") (pintype "power_in"))
    )
    (net (code "103") (name "Net-(S7-PadN)") (class "Default")
      (node (ref "S7") (pin "N") (pinfunction "N_N") (pintype "power_in"))
      (node (ref "S8") (pin "P") (pinfunction "P_P") (pintype "power_in"))
    )
    (net (code "104") (name "Net-(S10-PadN)") (class "Default")
      (node (ref "S10") (pin "N") (pinfunction "N_N") (pintype "power_in"))
      (node (ref "S11") (pin "P") (pinfunction "P_P") (pintype "power_in"))
    )
    (net (code "105") (name "Net-(S10-PadP)") (class "Default")
      (node (ref "S10") (pin "P") (pinfunction "P_P") (pintype "power_in"))
      (node (ref "S9") (pin "N") (pinfunction "N_N") (pintype "power_in"))
    )
    (net (code "106") (name "Net-(S11-PadN)") (class "Default")
      (node (ref "S11") (pin "N") (pinfunction "N_N") (pintype "power_in"))
      (node (ref "S12") (pin "P") (pinfunction "P_P") (pintype "power_in"))
    )
    (net (code "107") (name "Net-(S13-PadN)") (class "Default")
      (node (ref "S13") (pin "N") (pinfunction "N_N") (pintype "power_in"))
      (node (ref "S14") (pin "P") (pinfunction "P_P") (pintype "power_in"))
    )
    (net (code "108") (name "Net-(S14-PadN)") (class "Default")
      (node (ref "S14") (pin "N") (pinfunction "N_N") (pintype "power_in"))
      (node (ref "S15") (pin "P") (pinfunction "P_P") (pintype "power_in"))
    )
    (net (code "109") (name "Net-(S15-PadN)") (class "Default")
      (node (ref "S15") (pin "N") (pinfunction "N_N") (pintype "power_in"))
      (node (ref "S16") (pin "P") (pinfunction "P_P") (pintype "power_in"))
    )
    (net (code "110") (name "Net-(S17-PadN)") (class "Default")
      (node (ref "S17") (pin "N") (pinfunction "N_N") (pintype "power_in"))
      (node (ref "S18") (pin "P") (pinfunction "P_P") (pintype "power_in"))
    )
    (net (code "111") (name "Net-(S18-PadN)") (class "Default")
      (node (ref "S18") (pin "N") (pinfunction "N_N") (pintype "power_in"))
      (node (ref "S19") (pin "P") (pinfunction "P_P") (pintype "power_in"))
    )
    (net (code "112") (name "Net-(S19-PadN)") (class "Default")
      (node (ref "S19") (pin "N") (pinfunction "N_N") (pintype "power_in"))
      (node (ref "S20") (pin "P") (pinfunction "P_P") (pintype "power_in"))
    )
    (net (code "113") (name "Net-(S21-PadN)") (class "Default")
      (node (ref "S21") (pin "N") (pinfunction "N_N") (pintype "power_in"))
      (node (ref "S22") (pin "P") (pinfunction "P_P") (pintype "power_in"))
    )
    (net (code "114") (name "Net-(S22-PadN)") (class "Default")
      (node (ref "S22") (pin "N") (pinfunction "N_N") (pintype "power_in"))
      (node (ref "S23") (pin "P") (pinfunction "P_P") (pintype "power_in"))
    )
    (net (code "115") (name "Net-(S23-PadN)") (class "Default")
      (node (ref "S23") (pin "N") (pinfunction "N_N") (pintype "power_in"))
      (node (ref "S24") (pin "P") (pinfunction "P_P") (pintype "power_in"))
    )
    (net (code "116") (name "Net-(T1A-S)") (class "Default")
      (node (ref "R13") (pin "1") (pinfunction "1_1") (pintype "passive"))
      (node (ref "T1") (pin "1") (pinfunction "S_1") (pintype "passive"))
      (node (ref "T2") (pin "3") (pinfunction "S_3") (pintype "passive"))
    )
    (net (code "117") (name "Net-(T1B-S)") (class "Default")
      (node (ref "R12") (pin "1") (pinfunction "1_1") (pintype "passive"))
      (node (ref "T1") (pin "3") (pinfunction "S_3") (pintype "passive"))
      (node (ref "T2") (pin "1") (pinfunction "S_1") (pintype "passive"))
    )
    (net (code "118") (name "Net-(T3A-S)") (class "Default")
      (node (ref "R16") (pin "1") (pinfunction "1_1") (pintype "passive"))
      (node (ref "T3") (pin "1") (pinfunction "S_1") (pintype "passive"))
      (node (ref "T4") (pin "3") (pinfunction "S_3") (pintype "passive"))
    )
    (net (code "119") (name "Net-(T3B-S)") (class "Default")
      (node (ref "R30") (pin "1") (pinfunction "1_1") (pintype "passive"))
      (node (ref "T3") (pin "3") (pinfunction "S_3") (pintype "passive"))
      (node (ref "T4") (pin "1") (pinfunction "S_1") (pintype "passive"))
    )
    (net (code "120") (name "Net-(T5A-S)") (class "Default")
      (node (ref "R19") (pin "1") (pinfunction "1_1") (pintype "passive"))
      (node (ref "T5") (pin "1") (pinfunction "S_1") (pintype "passive"))
      (node (ref "T6") (pin "3") (pinfunction "S_3") (pintype "passive"))
    )
    (net (code "121") (name "Net-(T5B-S)") (class "Default")
      (node (ref "R76") (pin "1") (pinfunction "1_1") (pintype "passive"))
      (node (ref "T5") (pin "3") (pinfunction "S_3") (pintype "passive"))
      (node (ref "T6") (pin "1") (pinfunction "S_1") (pintype "passive"))
    )
    (net (code "122") (name "Net-(U1-EN)") (class "Default")
      (node (ref "SJ3") (pin "1") (pinfunction "1_1") (pintype "passive"))
      (node (ref "U1") (pin "5") (pinfunction "EN_5") (pintype "input"))
    )
    (net (code "123") (name "Net-(U1-SW)") (class "Default")
      (node (ref "C6") (pin "2") (pinfunction "2_2") (pintype "passive"))
      (node (ref "L3") (pin "1") (pinfunction "1_1") (pintype "passive"))
      (node (ref "U1") (pin "2") (pinfunction "SW_2") (pintype "power_in"))
    )
    (net (code "124") (name "Net-(U1-VBST)") (class "Default")
      (node (ref "C6") (pin "1") (pinfunction "1_1") (pintype "passive"))
      (node (ref "U1") (pin "6") (pinfunction "VBST_6") (pintype "power_in"))
    )
    (net (code "125") (name "Net-(U1-VFB)") (class "Default")
      (node (ref "R7") (pin "1") (pinfunction "1_1") (pintype "passive"))
      (node (ref "R8") (pin "2") (pinfunction "2_2") (pintype "passive"))
      (node (ref "U1") (pin "4") (pinfunction "VFB_4") (pintype "input"))
    )
    (net (code "126") (name "Net-(U2-EN)") (class "Default")
      (node (ref "SJ4") (pin "1") (pinfunction "1_1") (pintype "passive"))
      (node (ref "U2") (pin "5") (pinfunction "EN_5") (pintype "input"))
    )
    (net (code "127") (name "Net-(U2-SW)") (class "Default")
      (node (ref "C8") (pin "2") (pinfunction "2_2") (pintype "passive"))
      (node (ref "L2") (pin "1") (pinfunction "1_1") (pintype "passive"))
      (node (ref "U2") (pin "2") (pinfunction "SW_2") (pintype "power_in"))
    )
    (net (code "128") (name "Net-(U2-VBST)") (class "Default")
      (node (ref "C8") (pin "1") (pinfunction "1_1") (pintype "passive"))
      (node (ref "U2") (pin "6") (pinfunction "VBST_6") (pintype "power_in"))
    )
    (net (code "129") (name "Net-(U2-VFB)") (class "Default")
      (node (ref "R10") (pin "2") (pinfunction "2_2") (pintype "passive"))
      (node (ref "R9") (pin "1") (pinfunction "1_1") (pintype "passive"))
      (node (ref "U2") (pin "4") (pinfunction "VFB_4") (pintype "input"))
    )
    (net (code "130") (name "Net-(U3-APG{slash}THERM)") (class "Default")
      (node (ref "R83") (pin "1") (pinfunction "1_1") (pintype "passive"))
      (node (ref "R84") (pin "2") (pinfunction "2_2") (pintype "passive"))
      (node (ref "SJ7") (pin "2") (pinfunction "2_2") (pintype "passive"))
      (node (ref "U3") (pin "7") (pinfunction "APG/THERM_7") (pintype "input"))
    )
    (net (code "131") (name "Net-(U3-CR)") (class "Default")
      (node (ref "C23") (pin "2") (pinfunction "2_2") (pintype "passive"))
      (node (ref "R84") (pin "1") (pinfunction "1_1") (pintype "passive"))
      (node (ref "U3") (pin "12") (pinfunction "CR_12") (pintype "input"))
    )
    (net (code "132") (name "Net-(U3-IN)") (class "Default")
      (node (ref "R45") (pin "2") (pinfunction "2_2") (pintype "passive"))
      (node (ref "U3") (pin "2") (pinfunction "IN_2_2") (pintype "input"))
      (node (ref "U3") (pin "3") (pinfunction "IN_3") (pintype "input"))
      (node (ref "U3") (pin "5") (pinfunction "ISNS_5") (pintype "input"))
    )
    (net (code "133") (name "Net-(U3-STAT1)") (class "Default")
      (node (ref "LED5") (pin "C") (pinfunction "C_C") (pintype "passive"))
      (node (ref "U3") (pin "14") (pinfunction "STAT1_14") (pintype "output"))
    )
    (net (code "134") (name "Net-(U3-STAT2)") (class "Default")
      (node (ref "LED4") (pin "C") (pinfunction "C_C") (pintype "passive"))
      (node (ref "U3") (pin "15") (pinfunction "STAT2_15") (pintype "output"))
    )
    (net (code "135") (name "Net-(U3-TMRSEL)") (class "Default")
      (node (ref "SJ2") (pin "2") (pinfunction "2_2") (pintype "passive"))
      (node (ref "U3") (pin "13") (pinfunction "TMRSEL_13") (pintype "input"))
    )
    (net (code "136") (name "Net-(U3-VSEL)") (class "Default")
      (node (ref "SJ1") (pin "2") (pinfunction "2_2") (pintype "passive"))
      (node (ref "U3") (pin "9") (pinfunction "VSEL_9") (pintype "input"))
    )
    (net (code "137") (name "Net-(U4-EN)") (class "Default")
      (node (ref "SJ5") (pin "1") (pinfunction "1_1") (pintype "passive"))
      (node (ref "U4") (pin "5") (pinfunction "EN_5") (pintype "input"))
    )
    (net (code "138") (name "Net-(U4-SW)") (class "Default")
      (node (ref "C28") (pin "2") (pinfunction "2_2") (pintype "passive"))
      (node (ref "L4") (pin "1") (pinfunction "1_1") (pintype "passive"))
      (node (ref "U4") (pin "2") (pinfunction "SW_2") (pintype "power_in"))
    )
    (net (code "139") (name "Net-(U4-VBST)") (class "Default")
      (node (ref "C28") (pin "1") (pinfunction "1_1") (pintype "passive"))
      (node (ref "U4") (pin "6") (pinfunction "VBST_6") (pintype "power_in"))
    )
    (net (code "140") (name "Net-(U4-VFB)") (class "Default")
      (node (ref "R57") (pin "1") (pinfunction "1_1") (pintype "passive"))
      (node (ref "R58") (pin "2") (pinfunction "2_2") (pintype "passive"))
      (node (ref "U4") (pin "4") (pinfunction "VFB_4") (pintype "input"))
    )
    (net (code "141") (name "Net-(U5-5GOOD)") (class "Default")
      (node (ref "R14") (pin "2") (pinfunction "2_2") (pintype "passive"))
      (node (ref "U5") (pin "17") (pinfunction "5GOOD_17") (pintype "output"))
    )
    (net (code "142") (name "Net-(U5-12GOOD)") (class "Default")
      (node (ref "R17") (pin "2") (pinfunction "2_2") (pintype "passive"))
      (node (ref "U5") (pin "16") (pinfunction "12GOOD_16") (pintype "output"))
    )
    (net (code "143") (name "Net-(U5-BOOST1)") (class "Default")
      (node (ref "C51") (pin "1") (pinfunction "1_1") (pintype "passive"))
      (node (ref "D4") (pin "C") (pinfunction "C_C") (pintype "passive"))
      (node (ref "U5") (pin "5") (pinfunction "BOOST1_5") (pintype "input"))
    )
    (net (code "144") (name "Net-(U5-BOOST2)") (class "Default")
      (node (ref "C46") (pin "1") (pinfunction "1_1") (pintype "passive"))
      (node (ref "D1") (pin "C") (pinfunction "C_C") (pintype "passive"))
      (node (ref "U5") (pin "24") (pinfunction "BOOST2_24") (pintype "input"))
    )
    (net (code "145") (name "Net-(U5-FB1)") (class "Default")
      (node (ref "R69") (pin "2") (pinfunction "2_2") (pintype "passive"))
      (node (ref "R70") (pin "1") (pinfunction "1_1") (pintype "passive"))
      (node (ref "U5") (pin "8") (pinfunction "FB1_8") (pintype "input"))
    )
    (net (code "146") (name "Net-(U5-FB2)") (class "Default")
      (node (ref "R65") (pin "2") (pinfunction "2_2") (pintype "passive"))
      (node (ref "R66") (pin "1") (pinfunction "1_1") (pintype "passive"))
      (node (ref "U5") (pin "11") (pinfunction "FB2_11") (pintype "input"))
    )
    (net (code "147") (name "Net-(U5-FB3)") (class "Default")
      (node (ref "R67") (pin "2") (pinfunction "2_2") (pintype "passive"))
      (node (ref "R68") (pin "1") (pinfunction "1_1") (pintype "passive"))
      (node (ref "U5") (pin "19") (pinfunction "NFB_19") (pintype "input"))
      (node (ref "U5") (pin "20") (pinfunction "FB3_20") (pintype "input"))
    )
    (net (code "148") (name "Net-(U5-PGOOD1)") (class "Default")
      (node (ref "R15") (pin "2") (pinfunction "2_2") (pintype "passive"))
      (node (ref "U5") (pin "6") (pinfunction "PGOOD1_6") (pintype "output"))
    )
    (net (code "149") (name "Net-(U5-PGOOD2)") (class "Default")
      (node (ref "R59") (pin "2") (pinfunction "2_2") (pintype "passive"))
      (node (ref "U5") (pin "9") (pinfunction "PGOOD2_9") (pintype "output"))
    )
    (net (code "150") (name "Net-(U5-PGOOD3)") (class "Default")
      (node (ref "R18") (pin "2") (pinfunction "2_2") (pintype "passive"))
      (node (ref "U5") (pin "21") (pinfunction "PGOOD3_21") (pintype "output"))
    )
    (net (code "151") (name "Net-(U5-RUN{slash}SS1)") (class "Default")
      (node (ref "C41") (pin "1") (pinfunction "1_1") (pintype "passive"))
      (node (ref "U5") (pin "12") (pinfunction "RUN/SS1_12") (pintype "input"))
    )
    (net (code "152") (name "Net-(U5-RUN{slash}SS2)") (class "Default")
      (node (ref "C43") (pin "1") (pinfunction "1_1") (pintype "passive"))
      (node (ref "U5") (pin "13") (pinfunction "RUN/SS2_13") (pintype "input"))
    )
    (net (code "153") (name "Net-(U5-RUN{slash}SS3)") (class "Default")
      (node (ref "C42") (pin "1") (pinfunction "1_1") (pintype "passive"))
      (node (ref "U5") (pin "14") (pinfunction "RUN/SS3_14") (pintype "input"))
    )
    (net (code "154") (name "Net-(U5-SW1)") (class "Default")
      (node (ref "C51") (pin "2") (pinfunction "2_2") (pintype "passive"))
      (node (ref "D5") (pin "C") (pinfunction "C_C") (pintype "passive"))
      (node (ref "L7") (pin "2") (pinfunction "2_2") (pintype "passive"))
      (node (ref "U5") (pin "3") (pinfunction "SW1_2_3") (pintype "output"))
      (node (ref "U5") (pin "4") (pinfunction "SW1_4") (pintype "output"))
    )
    (net (code "155") (name "Net-(U5-SW2)") (class "Default")
      (node (ref "C46") (pin "2") (pinfunction "2_2") (pintype "passive"))
      (node (ref "D2") (pin "C") (pinfunction "C_C") (pintype "passive"))
      (node (ref "L5") (pin "2") (pinfunction "2_2") (pintype "passive"))
      (node (ref "U5") (pin "23") (pinfunction "SW2_23") (pintype "output"))
    )
    (net (code "156") (name "Net-(U5-SW3)") (class "Default")
      (node (ref "D3") (pin "A") (pinfunction "A_A") (pintype "passive"))
      (node (ref "L6") (pin "1") (pinfunction "1_1") (pintype "passive"))
      (node (ref "U5") (pin "27") (pinfunction "SW3_27") (pintype "output"))
    )
    (net (code "157") (name "Net-(U5-VC1)") (class "Default")
      (node (ref "C40") (pin "2") (pinfunction "2_2") (pintype "passive"))
      (node (ref "U5") (pin "7") (pinfunction "VC1_7") (pintype "output"))
    )
    (net (code "158") (name "Net-(U5-VC2)") (class "Default")
      (node (ref "C44") (pin "2") (pinfunction "2_2") (pintype "passive"))
      (node (ref "U5") (pin "10") (pinfunction "VC2_10") (pintype "output"))
    )
    (net (code "159") (name "Net-(U5-VC3)") (class "Default")
      (node (ref "C45") (pin "2") (pinfunction "2_2") (pintype "passive"))
      (node (ref "U5") (pin "18") (pinfunction "VC3_18") (pintype "output"))
    )
    (net (code "160") (name "Net-(U6-COMP)") (class "Default")
      (node (ref "C2") (pin "1") (pinfunction "1_1") (pintype "passive"))
      (node (ref "C3") (pin "1") (pinfunction "1_1") (pintype "passive"))
      (node (ref "U6") (pin "2") (pinfunction "COMP_2") (pintype "passive"))
    )
    (net (code "161") (name "Net-(U6-FA{slash}SYNC{slash}SD)") (class "Default")
      (node (ref "R2") (pin "2") (pinfunction "2_2") (pintype "passive"))
      (node (ref "U6") (pin "7") (pinfunction "FA/SYNC/SD_7") (pintype "passive"))
    )
    (net (code "162") (name "Net-(U6-FB)") (class "Default")
      (node (ref "R5") (pin "2") (pinfunction "2_2") (pintype "passive"))
      (node (ref "R6") (pin "2") (pinfunction "2_2") (pintype "passive"))
      (node (ref "U6") (pin "3") (pinfunction "FB_3") (pintype "passive"))
    )
    (net (code "163") (name "Net-(U6-ISEN)") (class "Default")
      (node (ref "R3") (pin "2") (pinfunction "2_2") (pintype "passive"))
      (node (ref "U6") (pin "1") (pinfunction "ISEN_1") (pintype "passive"))
    )
    (net (code "164") (name "OSC1") (class "Default")
      (node (ref "C70") (pin "2") (pinfunction "2_2") (pintype "passive"))
      (node (ref "IC9") (pin "46") (pinfunction "OSC1/CLKIN/RA7_46") (pintype "bidirectional"))
      (node (ref "Q3") (pin "1") (pinfunction "1_1") (pintype "passive"))
    )
    (net (code "165") (name "OSC2") (class "Default")
      (node (ref "C71") (pin "2") (pinfunction "2_2") (pintype "passive"))
      (node (ref "IC9") (pin "47") (pinfunction "OSC2/CLKOUT/RA6_47") (pintype "bidirectional"))
      (node (ref "Q3") (pin "2") (pinfunction "2_2") (pintype "passive"))
    )
    (net (code "166") (name "PGC") (class "Default")
      (node (ref "IC9") (pin "22") (pinfunction "RB6/PGC/KBI2_22") (pintype "bidirectional"))
      (node (ref "ICSP") (pin "5") (pinfunction "PGC_5") (pintype "passive"))
    )
    (net (code "167") (name "PGD") (class "Default")
      (node (ref "IC9") (pin "23") (pinfunction "RB7/PGD/T3G/KBI3_23") (pintype "bidirectional"))
      (node (ref "ICSP") (pin "4") (pinfunction "PGD_4") (pintype "passive"))
    )
    (net (code "168") (name "RX") (class "Default")
      (node (ref "IC9") (pin "6") (pinfunction "RG0/RX1/DT1_6") (pintype "bidirectional"))
      (node (ref "SERIAL") (pin "3") (pinfunction "3_3") (pintype "bidirectional"))
    )
    (net (code "169") (name "SENSOR_+X") (class "Default")
      (node (ref "+X") (pin "4") (pinfunction "4_4") (pintype "passive"))
      (node (ref "IC17") (pin "13") (pinfunction "X0_13") (pintype "bidirectional"))
    )
    (net (code "170") (name "SENSOR_+Y") (class "Default")
      (node (ref "+Y") (pin "4") (pinfunction "4_4") (pintype "passive"))
      (node (ref "IC17") (pin "15") (pinfunction "X2_15") (pintype "bidirectional"))
    )
    (net (code "171") (name "SENSOR_-X") (class "Default")
      (node (ref "-X") (pin "4") (pinfunction "4_4") (pintype "passive"))
      (node (ref "IC17") (pin "14") (pinfunction "X1_14") (pintype "bidirectional"))
    )
    (net (code "172") (name "SENSOR_-Y") (class "Default")
      (node (ref "-Y") (pin "4") (pinfunction "4_4") (pintype "passive"))
      (node (ref "IC17") (pin "12") (pinfunction "X3_12") (pintype "bidirectional"))
    )
    (net (code "173") (name "TX") (class "Default")
      (node (ref "IC9") (pin "12") (pinfunction "RG3/TX1/CK1_12") (pintype "bidirectional"))
      (node (ref "SERIAL") (pin "2") (pinfunction "2_2") (pintype "bidirectional"))
    )
    (net (code "174") (name "VBAT") (class "Default")
      (node (ref "BACKUP") (pin "13") (pinfunction "13_13") (pintype "passive"))
      (node (ref "BACKUP") (pin "14") (pinfunction "14_14") (pintype "passive"))
      (node (ref "BACKUP") (pin "15") (pinfunction "15_15") (pintype "passive"))
      (node (ref "BACKUP") (pin "16") (pinfunction "16_16") (pintype "passive"))
      (node (ref "BACKUP1") (pin "13") (pinfunction "13_13") (pintype "passive"))
      (node (ref "BACKUP1") (pin "14") (pinfunction "14_14") (pintype "passive"))
      (node (ref "BACKUP1") (pin "15") (pinfunction "15_15") (pintype "passive"))
      (node (ref "BACKUP1") (pin "16") (pinfunction "16_16") (pintype "passive"))
      (node (ref "BAT") (pin "1") (pinfunction "1_1") (pintype "passive"))
      (node (ref "C1") (pin "1") (pinfunction "1_1") (pintype "passive"))
      (node (ref "C11") (pin "+") (pinfunction "+_+") (pintype "passive"))
      (node (ref "C24") (pin "2") (pinfunction "2_2") (pintype "passive"))
      (node (ref "C29") (pin "+") (pinfunction "+_+") (pintype "passive"))
      (node (ref "C5") (pin "+") (pinfunction "+_+") (pintype "passive"))
      (node (ref "C54") (pin "+") (pinfunction "+_+") (pintype "passive"))
      (node (ref "C55") (pin "1") (pinfunction "1_1") (pintype "passive"))
      (node (ref "C60") (pin "2") (pinfunction "2_2") (pintype "passive"))
      (node (ref "C62") (pin "2") (pinfunction "2_2") (pintype "passive"))
      (node (ref "C63") (pin "2") (pinfunction "2_2") (pintype "passive"))
      (node (ref "C66") (pin "1") (pinfunction "1_1") (pintype "passive"))
      (node (ref "C9") (pin "+") (pinfunction "+_+") (pintype "passive"))
      (node (ref "D4") (pin "A") (pinfunction "A_A") (pintype "passive"))
      (node (ref "L1") (pin "1") (pinfunction "1_1") (pintype "passive"))
      (node (ref "L6") (pin "2") (pinfunction "2_2") (pintype "passive"))
      (node (ref "Q2") (pin "2") (pinfunction "S_2") (pintype "passive"))
      (node (ref "R14") (pin "1") (pinfunction "1_1") (pintype "passive"))
      (node (ref "R15") (pin "1") (pinfunction "1_1") (pintype "passive"))
      (node (ref "R17") (pin "1") (pinfunction "1_1") (pintype "passive"))
      (node (ref "R18") (pin "1") (pinfunction "1_1") (pintype "passive"))
      (node (ref "R59") (pin "1") (pinfunction "1_1") (pintype "passive"))
      (node (ref "SJ3") (pin "2") (pinfunction "2_2") (pintype "passive"))
      (node (ref "SJ4") (pin "2") (pinfunction "2_2") (pintype "passive"))
      (node (ref "SJ5") (pin "2") (pinfunction "2_2") (pintype "passive"))
      (node (ref "TP1") (pin "1") (pinfunction "P$1_1") (pintype "bidirectional"))
      (node (ref "TP10") (pin "1") (pinfunction "P$1_1") (pintype "bidirectional"))
      (node (ref "TP6") (pin "1") (pinfunction "P$1_1") (pintype "bidirectional"))
      (node (ref "TP8") (pin "1") (pinfunction "P$1_1") (pintype "bidirectional"))
      (node (ref "U1") (pin "3") (pinfunction "VIN_3") (pintype "power_in"))
      (node (ref "U2") (pin "3") (pinfunction "VIN_3") (pintype "power_in"))
      (node (ref "U3") (pin "17") (pinfunction "VSENSE_17") (pintype "input"))
      (node (ref "U3") (pin "18") (pinfunction "OUT_2_18") (pintype "output"))
      (node (ref "U3") (pin "19") (pinfunction "OUT_19") (pintype "output"))
      (node (ref "U4") (pin "3") (pinfunction "VIN_3") (pintype "power_in"))
      (node (ref "U5") (pin "1") (pinfunction "VIN_3_1") (pintype "power_in"))
      (node (ref "U5") (pin "15") (pinfunction "BIAS1_15") (pintype "power_in"))
      (node (ref "U5") (pin "2") (pinfunction "VIN_2_2") (pintype "power_in"))
      (node (ref "U5") (pin "22") (pinfunction "VIN_4_22") (pintype "power_in"))
      (node (ref "U5") (pin "25") (pinfunction "VIN_25") (pintype "power_in"))
      (node (ref "U5") (pin "28") (pinfunction "BIAS2_28") (pintype "power_in"))
      (node (ref "U6") (pin "8") (pinfunction "VIN_8") (pintype "passive"))
    )
    (net (code "175") (name "VCC") (class "Default")
      (node (ref "+X") (pin "3") (pinfunction "3_3") (pintype "passive"))
      (node (ref "+Y") (pin "3") (pinfunction "3_3") (pintype "passive"))
      (node (ref "-X") (pin "3") (pinfunction "3_3") (pintype "passive"))
      (node (ref "-Y") (pin "3") (pinfunction "3_3") (pintype "passive"))
      (node (ref "BACKUP") (pin "25") (pinfunction "25_25") (pintype "passive"))
      (node (ref "BACKUP") (pin "26") (pinfunction "26_26") (pintype "passive"))
      (node (ref "BACKUP1") (pin "25") (pinfunction "25_25") (pintype "passive"))
      (node (ref "BACKUP1") (pin "26") (pinfunction "26_26") (pintype "passive"))
      (node (ref "C13") (pin "2") (pinfunction "2_2") (pintype "passive"))
      (node (ref "C15") (pin "2") (pinfunction "2_2") (pintype "passive"))
      (node (ref "C17") (pin "2") (pinfunction "2_2") (pintype "passive"))
      (node (ref "C19") (pin "2") (pinfunction "2_2") (pintype "passive"))
      (node (ref "C21") (pin "2") (pinfunction "2_2") (pintype "passive"))
      (node (ref "C27") (pin "2") (pinfunction "2_2") (pintype "passive"))
      (node (ref "C30") (pin "+") (pinfunction "+_+") (pintype "passive"))
      (node (ref "C31") (pin "1") (pinfunction "1_1") (pintype "passive"))
      (node (ref "C32") (pin "1") (pinfunction "1_1") (pintype "passive"))
      (node (ref "C33") (pin "2") (pinfunction "2_2") (pintype "passive"))
      (node (ref "C34") (pin "2") (pinfunction "2_2") (pintype "passive"))
      (node (ref "C35") (pin "2") (pinfunction "2_2") (pintype "passive"))
      (node (ref "C36") (pin "2") (pinfunction "2_2") (pintype "passive"))
      (node (ref "C37") (pin "2") (pinfunction "2_2") (pintype "passive"))
      (node (ref "C38") (pin "2") (pinfunction "2_2") (pintype "passive"))
      (node (ref "C39") (pin "1") (pinfunction "1_1") (pintype "passive"))
      (node (ref "C65") (pin "1") (pinfunction "1_1") (pintype "passive"))
      (node (ref "C67") (pin "1") (pinfunction "1_1") (pintype "passive"))
      (node (ref "C68") (pin "1") (pinfunction "1_1") (pintype "passive"))
      (node (ref "C69") (pin "1") (pinfunction "1_1") (pintype "passive"))
      (node (ref "C72") (pin "2") (pinfunction "2_2") (pintype "passive"))
      (node (ref "C74") (pin "2") (pinfunction "2_2") (pintype "passive"))
      (node (ref "C75") (pin "2") (pinfunction "2_2") (pintype "passive"))
      (node (ref "C77") (pin "2") (pinfunction "2_2") (pintype "passive"))
      (node (ref "C79") (pin "2") (pinfunction "2_2") (pintype "passive"))
      (node (ref "C81") (pin "2") (pinfunction "2_2") (pintype "passive"))
      (node (ref "D7") (pin "C") (pinfunction "C_C") (pintype "passive"))
      (node (ref "IC1") (pin "1") (pinfunction "VIN_1") (pintype "power_in"))
      (node (ref "IC10") (pin "1") (pinfunction "VCC_1") (pintype "bidirectional"))
      (node (ref "IC11") (pin "3") (pinfunction "VCC_3") (pintype "power_in"))
      (node (ref "IC12") (pin "1") (pinfunction "VIN_1") (pintype "power_in"))
      (node (ref "IC13") (pin "8") (pinfunction "V+_8") (pintype "power_in"))
      (node (ref "IC14") (pin "1") (pinfunction "VIN_1") (pintype "power_in"))
      (node (ref "IC15") (pin "1") (pinfunction "VIN_1") (pintype "power_in"))
      (node (ref "IC16") (pin "1") (pinfunction "VIN_1") (pintype "power_in"))
      (node (ref "IC17") (pin "16") (pinfunction "VCC_16") (pintype "power_in"))
      (node (ref "IC18") (pin "1") (pinfunction "VCC_1") (pintype "bidirectional"))
      (node (ref "IC2") (pin "1") (pinfunction "VIN_1") (pintype "power_in"))
      (node (ref "IC3") (pin "1") (pinfunction "VIN_1") (pintype "power_in"))
      (node (ref "IC4") (pin "1") (pinfunction "VIN_1") (pintype "power_in"))
      (node (ref "IC5") (pin "8") (pinfunction "V+_8") (pintype "power_in"))
      (node (ref "IC6") (pin "8") (pinfunction "V+_8") (pintype "power_in"))
      (node (ref "IC7") (pin "8") (pinfunction "V+_8") (pintype "power_in"))
      (node (ref "IC8") (pin "8") (pinfunction "V+_8") (pintype "power_in"))
      (node (ref "IC9") (pin "10") (pinfunction "VDD_10") (pintype "power_in"))
      (node (ref "IC9") (pin "25") (pinfunction "VDD_25") (pintype "power_in"))
      (node (ref "IC9") (pin "40") (pinfunction "AVDD_40") (pintype "power_in"))
      (node (ref "IC9") (pin "41") (pinfunction "VDD_41") (pintype "power_in"))
      (node (ref "IC9") (pin "57") (pinfunction "VDD_57") (pintype "power_in"))
      (node (ref "IC9") (pin "9") (pinfunction "AVDD_9") (pintype "power_in"))
      (node (ref "ICSP") (pin "2") (pinfunction "+V_2") (pintype "passive"))
      (node (ref "L4") (pin "2") (pinfunction "2_2") (pintype "passive"))
      (node (ref "R48") (pin "1") (pinfunction "1_1") (pintype "passive"))
      (node (ref "R49") (pin "1") (pinfunction "1_1") (pintype "passive"))
      (node (ref "R50") (pin "1") (pinfunction "1_1") (pintype "passive"))
      (node (ref "R51") (pin "2") (pinfunction "2_2") (pintype "passive"))
      (node (ref "R52") (pin "2") (pinfunction "2_2") (pintype "passive"))
      (node (ref "R53") (pin "1") (pinfunction "1_1") (pintype "passive"))
      (node (ref "R56") (pin "2") (pinfunction "2_2") (pintype "passive"))
      (node (ref "R57") (pin "2") (pinfunction "2_2") (pintype "passive"))
      (node (ref "R85") (pin "1") (pinfunction "1_1") (pintype "passive"))
      (node (ref "R86") (pin "1") (pinfunction "1_1") (pintype "passive"))
      (node (ref "SERIAL") (pin "1") (pinfunction "1_1") (pintype "bidirectional"))
      (node (ref "SJ1") (pin "3") (pinfunction "3_3") (pintype "passive"))
      (node (ref "SJ2") (pin "3") (pinfunction "3_3") (pintype "passive"))
      (node (ref "SJ6") (pin "3") (pinfunction "3_3") (pintype "passive"))
      (node (ref "TP9") (pin "1") (pinfunction "P$1_1") (pintype "bidirectional"))
      (node (ref "U3") (pin "4") (pinfunction "VCC_4") (pintype "power_in"))
      (node (ref "U3") (pin "8") (pinfunction "EN_8") (pintype "input"))
      (node (ref "X1") (pin "5") (pinfunction "5_5") (pintype "passive"))
    )
    (net (code "176") (name "VCEL") (class "Default")
      (node (ref "C22") (pin "+") (pinfunction "+_+") (pintype "passive"))
      (node (ref "C64") (pin "2") (pinfunction "2_2") (pintype "passive"))
      (node (ref "FOTOCELULA") (pin "1") (pinfunction "1_1") (pintype "passive"))
      (node (ref "R45") (pin "1") (pinfunction "1_1") (pintype "passive"))
      (node (ref "R55") (pin "2") (pinfunction "2_2") (pintype "passive"))
      (node (ref "R79") (pin "1") (pinfunction "1_1") (pintype "passive"))
      (node (ref "R82") (pin "2") (pinfunction "2_2") (pintype "passive"))
    )
    (net (code "177") (name "VNREG") (class "Default")
      (node (ref "R40") (pin "2") (pinfunction "2_2") (pintype "passive"))
      (node (ref "R42") (pin "1") (pinfunction "1_1") (pintype "passive"))
      (node (ref "R44") (pin "2") (pinfunction "2_2") (pintype "passive"))
      (node (ref "V_BUS") (pin "31") (pinfunction "31_31") (pintype "passive"))
      (node (ref "V_BUS") (pin "33") (pinfunction "33_33") (pintype "passive"))
      (node (ref "V_BUS") (pin "35") (pinfunction "35_35") (pintype "passive"))
      (node (ref "V_BUS") (pin "37") (pinfunction "37_37") (pintype "passive"))
      (node (ref "V_BUS") (pin "39") (pinfunction "39_39") (pintype "passive"))
    )
    (net (code "178") (name "VOUT_+3V3") (class "Default")
      (node (ref "C18") (pin "2") (pinfunction "2_2") (pintype "passive"))
      (node (ref "IC3") (pin "6") (pinfunction "SENSE_6") (pintype "passive"))
      (node (ref "R33") (pin "2") (pinfunction "2_2") (pintype "passive"))
      (node (ref "R38") (pin "1") (pinfunction "1_1") (pintype "passive"))
      (node (ref "T6") (pin "6") (pinfunction "D_6") (pintype "passive"))
      (node (ref "T6") (pin "7") (pinfunction "D_7") (pintype "passive"))
    )
    (net (code "179") (name "VOUT_+5V") (class "Default")
      (node (ref "C16") (pin "2") (pinfunction "2_2") (pintype "passive"))
      (node (ref "IC2") (pin "6") (pinfunction "SENSE_6") (pintype "passive"))
      (node (ref "R21") (pin "2") (pinfunction "2_2") (pintype "passive"))
      (node (ref "R32") (pin "1") (pinfunction "1_1") (pintype "passive"))
      (node (ref "T4") (pin "6") (pinfunction "D_6") (pintype "passive"))
      (node (ref "T4") (pin "7") (pinfunction "D_7") (pintype "passive"))
      (node (ref "TP4") (pin "1") (pinfunction "P$1_1") (pintype "bidirectional"))
    )
    (net (code "180") (name "VOUT_+12V") (class "Default")
      (node (ref "C14") (pin "2") (pinfunction "2_2") (pintype "passive"))
      (node (ref "IC1") (pin "6") (pinfunction "SENSE_6") (pintype "passive"))
      (node (ref "R22") (pin "2") (pinfunction "2_2") (pintype "passive"))
      (node (ref "R27") (pin "1") (pinfunction "1_1") (pintype "passive"))
      (node (ref "T2") (pin "6") (pinfunction "D_6") (pintype "passive"))
      (node (ref "T2") (pin "7") (pinfunction "D_7") (pintype "passive"))
    )
    (net (code "181") (name "VOUT_+NREGV") (class "Default")
      (node (ref "C20") (pin "2") (pinfunction "2_2") (pintype "passive"))
      (node (ref "Q2") (pin "3") (pinfunction "D_3") (pintype "passive"))
      (node (ref "R39") (pin "2") (pinfunction "2_2") (pintype "passive"))
      (node (ref "R44") (pin "1") (pinfunction "1_1") (pintype "passive"))
    )
    (net (code "182") (name "VOUT_3V3") (class "Default")
      (node (ref "C12") (pin "+") (pinfunction "+_+") (pintype "passive"))
      (node (ref "C61") (pin "2") (pinfunction "2_2") (pintype "passive"))
      (node (ref "L2") (pin "2") (pinfunction "2_2") (pintype "passive"))
      (node (ref "R9") (pin "2") (pinfunction "2_2") (pintype "passive"))
      (node (ref "T5") (pin "7") (pinfunction "D_7") (pintype "passive"))
      (node (ref "TP7") (pin "1") (pinfunction "P$1_1") (pintype "bidirectional"))
    )
    (net (code "183") (name "VOUT_5V") (class "Default")
      (node (ref "C10") (pin "+") (pinfunction "+_+") (pintype "passive"))
      (node (ref "C59") (pin "2") (pinfunction "2_2") (pintype "passive"))
      (node (ref "L3") (pin "2") (pinfunction "2_2") (pintype "passive"))
      (node (ref "R7") (pin "2") (pinfunction "2_2") (pintype "passive"))
      (node (ref "T3") (pin "7") (pinfunction "D_7") (pintype "passive"))
      (node (ref "TP2") (pin "1") (pinfunction "P$1_1") (pintype "bidirectional"))
    )
    (net (code "184") (name "VOUT_12V") (class "Default")
      (node (ref "C56") (pin "+") (pinfunction "+_+") (pintype "passive"))
      (node (ref "C57") (pin "+") (pinfunction "+_+") (pintype "passive"))
      (node (ref "C58") (pin "1") (pinfunction "1_1") (pintype "passive"))
      (node (ref "C7") (pin "+") (pinfunction "+_+") (pintype "passive"))
      (node (ref "D6") (pin "C") (pinfunction "C_C") (pintype "passive"))
      (node (ref "R6") (pin "1") (pinfunction "1_1") (pintype "passive"))
      (node (ref "T1") (pin "7") (pinfunction "D_7") (pintype "passive"))
      (node (ref "TP11") (pin "1") (pinfunction "P$1_1") (pintype "bidirectional"))
    )
    (net (code "185") (name "VOUT_BACKUP_3V3") (class "Default")
      (node (ref "BACKUP") (pin "10") (pinfunction "10_10") (pintype "passive"))
      (node (ref "BACKUP") (pin "11") (pinfunction "11_11") (pintype "passive"))
      (node (ref "BACKUP") (pin "12") (pinfunction "12_12") (pintype "passive"))
      (node (ref "BACKUP") (pin "9") (pinfunction "9_9") (pintype "passive"))
      (node (ref "BACKUP1") (pin "10") (pinfunction "10_10") (pintype "passive"))
      (node (ref "BACKUP1") (pin "11") (pinfunction "11_11") (pintype "passive"))
      (node (ref "BACKUP1") (pin "12") (pinfunction "12_12") (pintype "passive"))
      (node (ref "BACKUP1") (pin "9") (pinfunction "9_9") (pintype "passive"))
      (node (ref "C47") (pin "+") (pinfunction "+_+") (pintype "passive"))
      (node (ref "C50") (pin "1") (pinfunction "1_1") (pintype "passive"))
      (node (ref "D1") (pin "A") (pinfunction "A_A") (pintype "passive"))
      (node (ref "L5") (pin "1") (pinfunction "1_1") (pintype "passive"))
      (node (ref "R65") (pin "1") (pinfunction "1_1") (pintype "passive"))
      (node (ref "T5") (pin "6") (pinfunction "D_6") (pintype "passive"))
    )
    (net (code "186") (name "VOUT_BACKUP_5V") (class "Default")
      (node (ref "BACKUP") (pin "5") (pinfunction "5_5") (pintype "passive"))
      (node (ref "BACKUP") (pin "6") (pinfunction "6_6") (pintype "passive"))
      (node (ref "BACKUP") (pin "7") (pinfunction "7_7") (pintype "passive"))
      (node (ref "BACKUP") (pin "8") (pinfunction "8_8") (pintype "passive"))
      (node (ref "BACKUP1") (pin "5") (pinfunction "5_5") (pintype "passive"))
      (node (ref "BACKUP1") (pin "6") (pinfunction "6_6") (pintype "passive"))
      (node (ref "BACKUP1") (pin "7") (pinfunction "7_7") (pintype "passive"))
      (node (ref "BACKUP1") (pin "8") (pinfunction "8_8") (pintype "passive"))
      (node (ref "C52") (pin "+") (pinfunction "+_+") (pintype "passive"))
      (node (ref "C53") (pin "1") (pinfunction "1_1") (pintype "passive"))
      (node (ref "L7") (pin "1") (pinfunction "1_1") (pintype "passive"))
      (node (ref "R69") (pin "1") (pinfunction "1_1") (pintype "passive"))
      (node (ref "T3") (pin "6") (pinfunction "D_6") (pintype "passive"))
      (node (ref "TP3") (pin "1") (pinfunction "P$1_1") (pintype "bidirectional"))
    )
    (net (code "187") (name "VOUT_BACKUP_12V") (class "Default")
      (node (ref "BACKUP") (pin "1") (pinfunction "1_1") (pintype "passive"))
      (node (ref "BACKUP") (pin "2") (pinfunction "2_2") (pintype "passive"))
      (node (ref "BACKUP") (pin "3") (pinfunction "3_3") (pintype "passive"))
      (node (ref "BACKUP") (pin "4") (pinfunction "4_4") (pintype "passive"))
      (node (ref "BACKUP1") (pin "1") (pinfunction "1_1") (pintype "passive"))
      (node (ref "BACKUP1") (pin "2") (pinfunction "2_2") (pintype "passive"))
      (node (ref "BACKUP1") (pin "3") (pinfunction "3_3") (pintype "passive"))
      (node (ref "BACKUP1") (pin "4") (pinfunction "4_4") (pintype "passive"))
      (node (ref "C48") (pin "+") (pinfunction "+_+") (pintype "passive"))
      (node (ref "C49") (pin "1") (pinfunction "1_1") (pintype "passive"))
      (node (ref "D3") (pin "C") (pinfunction "C_C") (pintype "passive"))
      (node (ref "R67") (pin "1") (pinfunction "1_1") (pintype "passive"))
      (node (ref "T1") (pin "6") (pinfunction "D_6") (pintype "passive"))
    )
    (net (code "188") (name "VSOLAR") (class "Default")
      (node (ref "D10") (pin "C") (pinfunction "C_C") (pintype "passive"))
      (node (ref "D11") (pin "C") (pinfunction "C_C") (pintype "passive"))
      (node (ref "D12") (pin "C") (pinfunction "C_C") (pintype "passive"))
      (node (ref "D13") (pin "C") (pinfunction "C_C") (pintype "passive"))
      (node (ref "D8") (pin "C") (pinfunction "C_C") (pintype "passive"))
      (node (ref "D9") (pin "C") (pinfunction "C_C") (pintype "passive"))
      (node (ref "X1") (pin "1") (pinfunction "1_1") (pintype "passive"))
      (node (ref "X1") (pin "2") (pinfunction "2_2") (pintype "passive"))
    )
    (net (code "189") (name "unconnected-(BACKUP1-Pad31)") (class "Default")
      (node (ref "BACKUP1") (pin "31") (pinfunction "31_31") (pintype "passive"))
    )
    (net (code "190") (name "unconnected-(CAN-Pad1)") (class "Default")
      (node (ref "CAN") (pin "1") (pinfunction "1_1") (pintype "bidirectional"))
    )
    (net (code "191") (name "unconnected-(IC4-STAT-Pad4)") (class "Default")
      (node (ref "IC4") (pin "4") (pinfunction "STAT_4") (pintype "passive"))
    )
    (net (code "192") (name "unconnected-(IC9-RB5{slash}T0CKI{slash}T3CKI{slash}CCP5{slash}KBI1-Pad21)") (class "Default")
      (node (ref "IC9") (pin "21") (pinfunction "RB5/T0CKI/T3CKI/CCP5/KBI1_21") (pintype "bidirectional"))
    )
    (net (code "193") (name "unconnected-(IC9-RC0{slash}SOSCO{slash}SCLKI-Pad48)") (class "Default")
      (node (ref "IC9") (pin "48") (pinfunction "RC0/SOSCO/SCLKI_48") (pintype "bidirectional"))
    )
    (net (code "194") (name "unconnected-(IC9-RC4{slash}SDA{slash}SDI-Pad62)") (class "Default")
      (node (ref "IC9") (pin "62") (pinfunction "RC4/SDA/SDI_62") (pintype "bidirectional"))
    )
    (net (code "195") (name "unconnected-(IC9-RC5{slash}SDO-Pad63)") (class "Default")
      (node (ref "IC9") (pin "63") (pinfunction "RC5/SDO_63") (pintype "bidirectional"))
    )
    (net (code "196") (name "unconnected-(IC9-RC6{slash}CCP3-Pad64)") (class "Default")
      (node (ref "IC9") (pin "64") (pinfunction "RC6/CCP3_64") (pintype "bidirectional"))
    )
    (net (code "197") (name "unconnected-(IC9-RD3{slash}C2INB{slash}CTMUI{slash}PSP3-Pad59)") (class "Default")
      (node (ref "IC9") (pin "59") (pinfunction "RD3/C2INB/CTMUI/PSP3_59") (pintype "bidirectional"))
    )
    (net (code "198") (name "unconnected-(IC9-RD5{slash}P1B{slash}PSP5-Pad3)") (class "Default")
      (node (ref "IC9") (pin "3") (pinfunction "RD5/P1B/PSP5_3") (pintype "bidirectional"))
    )
    (net (code "199") (name "unconnected-(IC9-RD6{slash}P1C{slash}PSP6-Pad4)") (class "Default")
      (node (ref "IC9") (pin "4") (pinfunction "RD6/P1C/PSP6_4") (pintype "bidirectional"))
    )
    (net (code "200") (name "unconnected-(IC9-RD7{slash}P1D{slash}PSP7-Pad5)") (class "Default")
      (node (ref "IC9") (pin "5") (pinfunction "RD7/P1D/PSP7_5") (pintype "bidirectional"))
    )
    (net (code "201") (name "unconnected-(IC9-RE4{slash}CANRX-Pad27)") (class "Default")
      (node (ref "IC9") (pin "27") (pinfunction "RE4/CANRX_27") (pintype "bidirectional"))
    )
    (net (code "202") (name "unconnected-(IC9-RE5{slash}CANTX-Pad24)") (class "Default")
      (node (ref "IC9") (pin "24") (pinfunction "RE5/CANTX_24") (pintype "bidirectional"))
    )
    (net (code "203") (name "unconnected-(IC9-RE6{slash}RX2{slash}DT2-Pad60)") (class "Default")
      (node (ref "IC9") (pin "60") (pinfunction "RE6/RX2/DT2_60") (pintype "bidirectional"))
    )
    (net (code "204") (name "unconnected-(IC9-RE7{slash}TX2{slash}CK2-Pad61)") (class "Default")
      (node (ref "IC9") (pin "61") (pinfunction "RE7/TX2/CK2_61") (pintype "bidirectional"))
    )
    (net (code "205") (name "unconnected-(IC9-RF2{slash}MDCIN1-Pad35)") (class "Default")
      (node (ref "IC9") (pin "35") (pinfunction "RF2/MDCIN1_35") (pintype "bidirectional"))
    )
    (net (code "206") (name "unconnected-(IC9-RF3-Pad36)") (class "Default")
      (node (ref "IC9") (pin "36") (pinfunction "RF3_36") (pintype "bidirectional"))
    )
    (net (code "207") (name "unconnected-(IC9-RF4{slash}MDCIN2-Pad44)") (class "Default")
      (node (ref "IC9") (pin "44") (pinfunction "RF4/MDCIN2_44") (pintype "bidirectional"))
    )
    (net (code "208") (name "unconnected-(IC9-RF5-Pad45)") (class "Default")
      (node (ref "IC9") (pin "45") (pinfunction "RF5_45") (pintype "bidirectional"))
    )
    (net (code "209") (name "unconnected-(IC9-RF6{slash}MDOUT-Pad52)") (class "Default")
      (node (ref "IC9") (pin "52") (pinfunction "RF6/MDOUT_52") (pintype "bidirectional"))
    )
    (net (code "210") (name "unconnected-(IC9-RF7-Pad53)") (class "Default")
      (node (ref "IC9") (pin "53") (pinfunction "RF7_53") (pintype "bidirectional"))
    )
    (net (code "211") (name "unconnected-(IC9-RG1{slash}CANTX2-Pad7)") (class "Default")
      (node (ref "IC9") (pin "7") (pinfunction "RG1/CANTX2_7") (pintype "bidirectional"))
    )
    (net (code "212") (name "unconnected-(IC9-RG2{slash}T3CKI-Pad11)") (class "Default")
      (node (ref "IC9") (pin "11") (pinfunction "RG2/T3CKI_11") (pintype "bidirectional"))
    )
    (net (code "213") (name "unconnected-(IC11-VREF-Pad5)") (class "Default")
      (node (ref "IC11") (pin "5") (pinfunction "VREF_5") (pintype "input"))
    )
    (net (code "214") (name "unconnected-(IC12-STAT-Pad4)") (class "Default")
      (node (ref "IC12") (pin "4") (pinfunction "STAT_4") (pintype "passive"))
    )
    (net (code "215") (name "unconnected-(IC14-STAT-Pad4)") (class "Default")
      (node (ref "IC14") (pin "4") (pinfunction "STAT_4") (pintype "passive"))
    )
    (net (code "216") (name "unconnected-(IC15-STAT-Pad4)") (class "Default")
      (node (ref "IC15") (pin "4") (pinfunction "STAT_4") (pintype "passive"))
    )
    (net (code "217") (name "unconnected-(IC16-STAT-Pad4)") (class "Default")
      (node (ref "IC16") (pin "4") (pinfunction "STAT_4") (pintype "passive"))
    )
    (net (code "218") (name "unconnected-(T1A-D2-Pad8)") (class "Default")
      (node (ref "T1") (pin "8") (pinfunction "D2_8") (pintype "passive"))
    )
    (net (code "219") (name "unconnected-(T1B-D2-Pad5)") (class "Default")
      (node (ref "T1") (pin "5") (pinfunction "D2_5") (pintype "passive"))
    )
    (net (code "220") (name "unconnected-(T2A-D2-Pad8)") (class "Default")
      (node (ref "T2") (pin "8") (pinfunction "D2_8") (pintype "passive"))
    )
    (net (code "221") (name "unconnected-(T2B-D2-Pad5)") (class "Default")
      (node (ref "T2") (pin "5") (pinfunction "D2_5") (pintype "passive"))
    )
    (net (code "222") (name "unconnected-(T3A-D2-Pad8)") (class "Default")
      (node (ref "T3") (pin "8") (pinfunction "D2_8") (pintype "passive"))
    )
    (net (code "223") (name "unconnected-(T3B-D2-Pad5)") (class "Default")
      (node (ref "T3") (pin "5") (pinfunction "D2_5") (pintype "passive"))
    )
    (net (code "224") (name "unconnected-(T4A-D2-Pad8)") (class "Default")
      (node (ref "T4") (pin "8") (pinfunction "D2_8") (pintype "passive"))
    )
    (net (code "225") (name "unconnected-(T4B-D2-Pad5)") (class "Default")
      (node (ref "T4") (pin "5") (pinfunction "D2_5") (pintype "passive"))
    )
    (net (code "226") (name "unconnected-(T5A-D2-Pad8)") (class "Default")
      (node (ref "T5") (pin "8") (pinfunction "D2_8") (pintype "passive"))
    )
    (net (code "227") (name "unconnected-(T5B-D2-Pad5)") (class "Default")
      (node (ref "T5") (pin "5") (pinfunction "D2_5") (pintype "passive"))
    )
    (net (code "228") (name "unconnected-(T6A-D2-Pad8)") (class "Default")
      (node (ref "T6") (pin "8") (pinfunction "D2_8") (pintype "passive"))
    )
    (net (code "229") (name "unconnected-(T6B-D2-Pad5)") (class "Default")
      (node (ref "T6") (pin "5") (pinfunction "D2_5") (pintype "passive"))
    )
    (net (code "230") (name "unconnected-(U3-NC-Pad20)") (class "Default")
      (node (ref "U3") (pin "20") (pinfunction "NC_20") (pintype "no_connect"))
    )
    (net (code "231") (name "unconnected-(U3-NC_2-Pad1)") (class "Default")
      (node (ref "U3") (pin "1") (pinfunction "NC_2_1") (pintype "no_connect"))
    )
    (net (code "232") (name "unconnected-(U3-NC_3-Pad6)") (class "Default")
      (node (ref "U3") (pin "6") (pinfunction "NC_3_6") (pintype "no_connect"))
    )
    (net (code "233") (name "unconnected-(U3-NC_4-Pad11)") (class "Default")
      (node (ref "U3") (pin "11") (pinfunction "NC_4_11") (pintype "no_connect"))
    )
    (net (code "234") (name "~{MCLR}") (class "Default")
      (node (ref "IC9") (pin "28") (pinfunction "~{MCLR/}RE3_28") (pintype "bidirectional"))
      (node (ref "ICSP") (pin "1") (pinfunction "/MCLR_1") (pintype "passive"))
      (node (ref "R47") (pin "2") (pinfunction "2_2") (pintype "passive"))
    )
  )
)
